# 509_CoilDriver.net
KiCad netlist of a schematic drawn in EAGLE
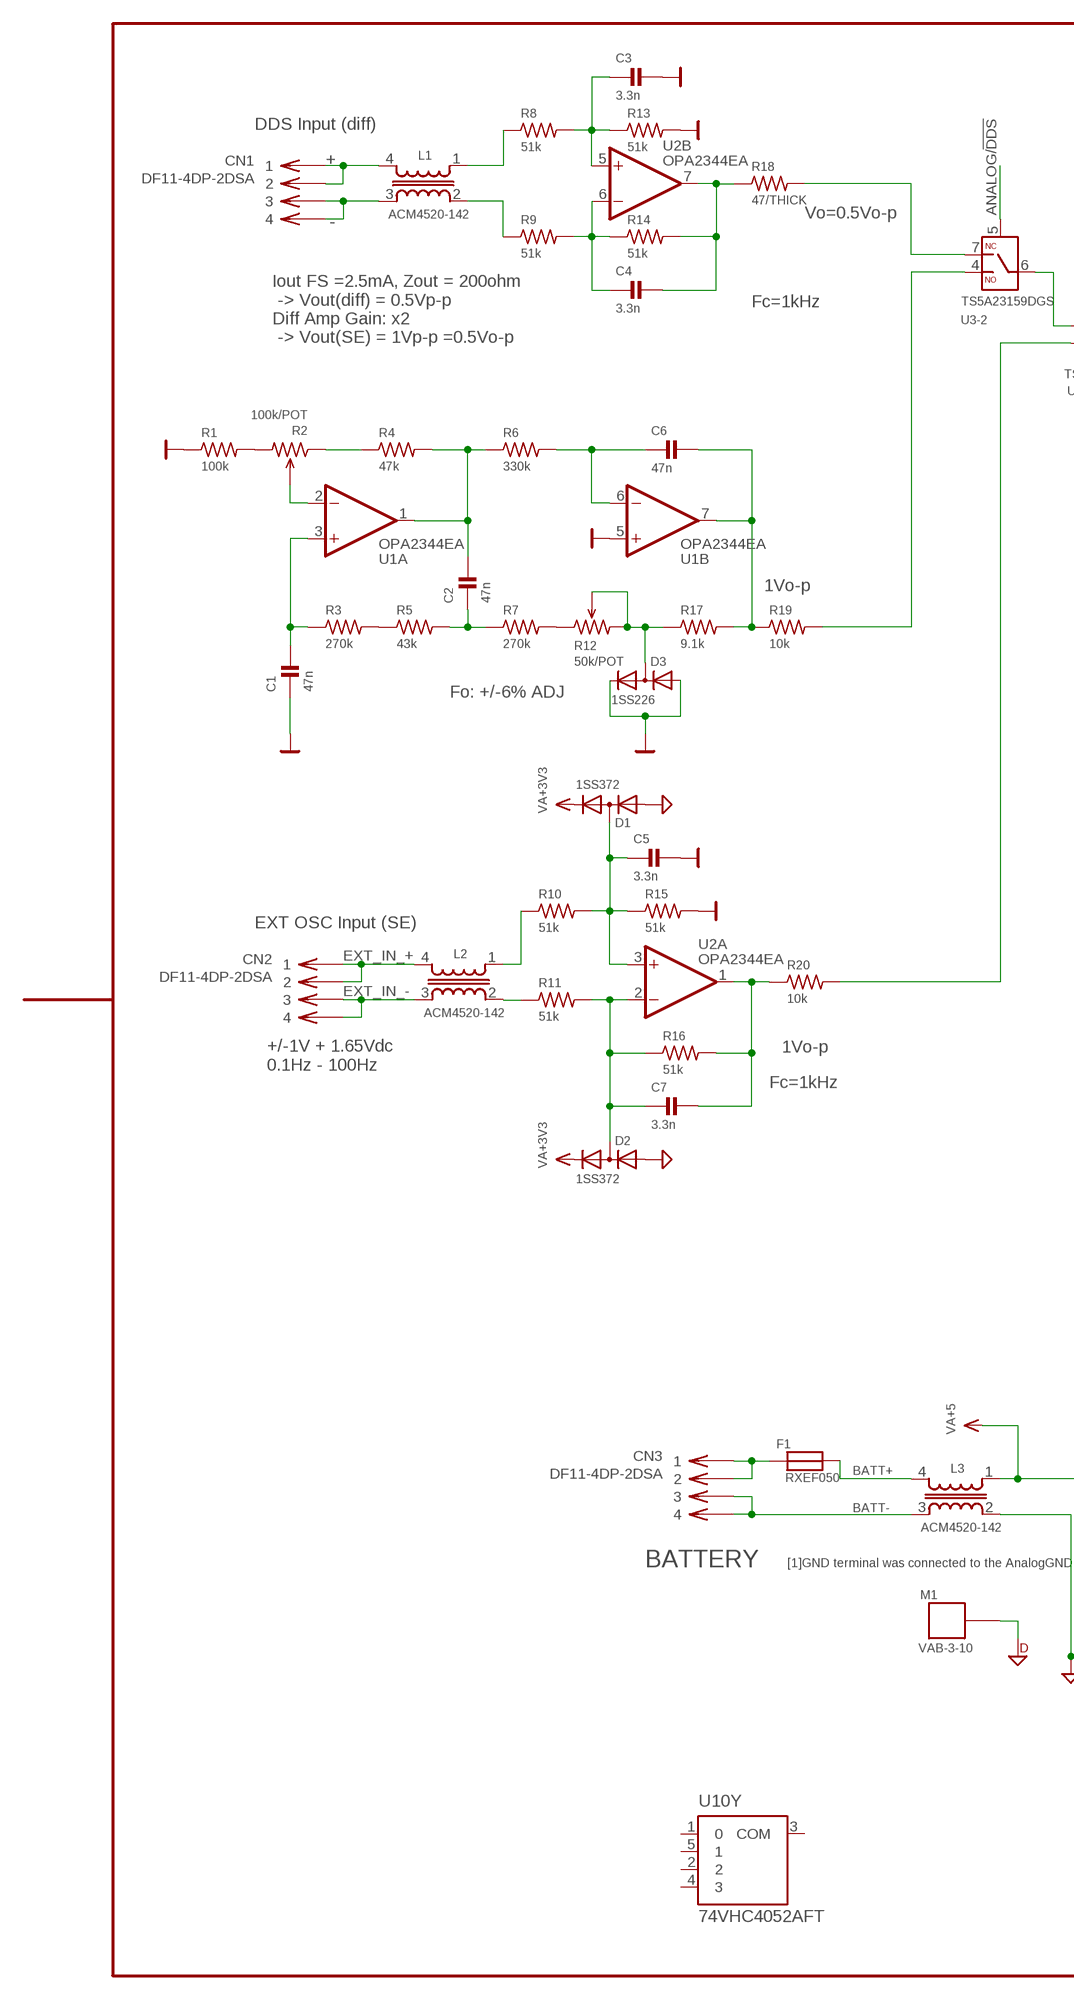
[diagram p0: schematic, sheet 1, part 1 of 2]
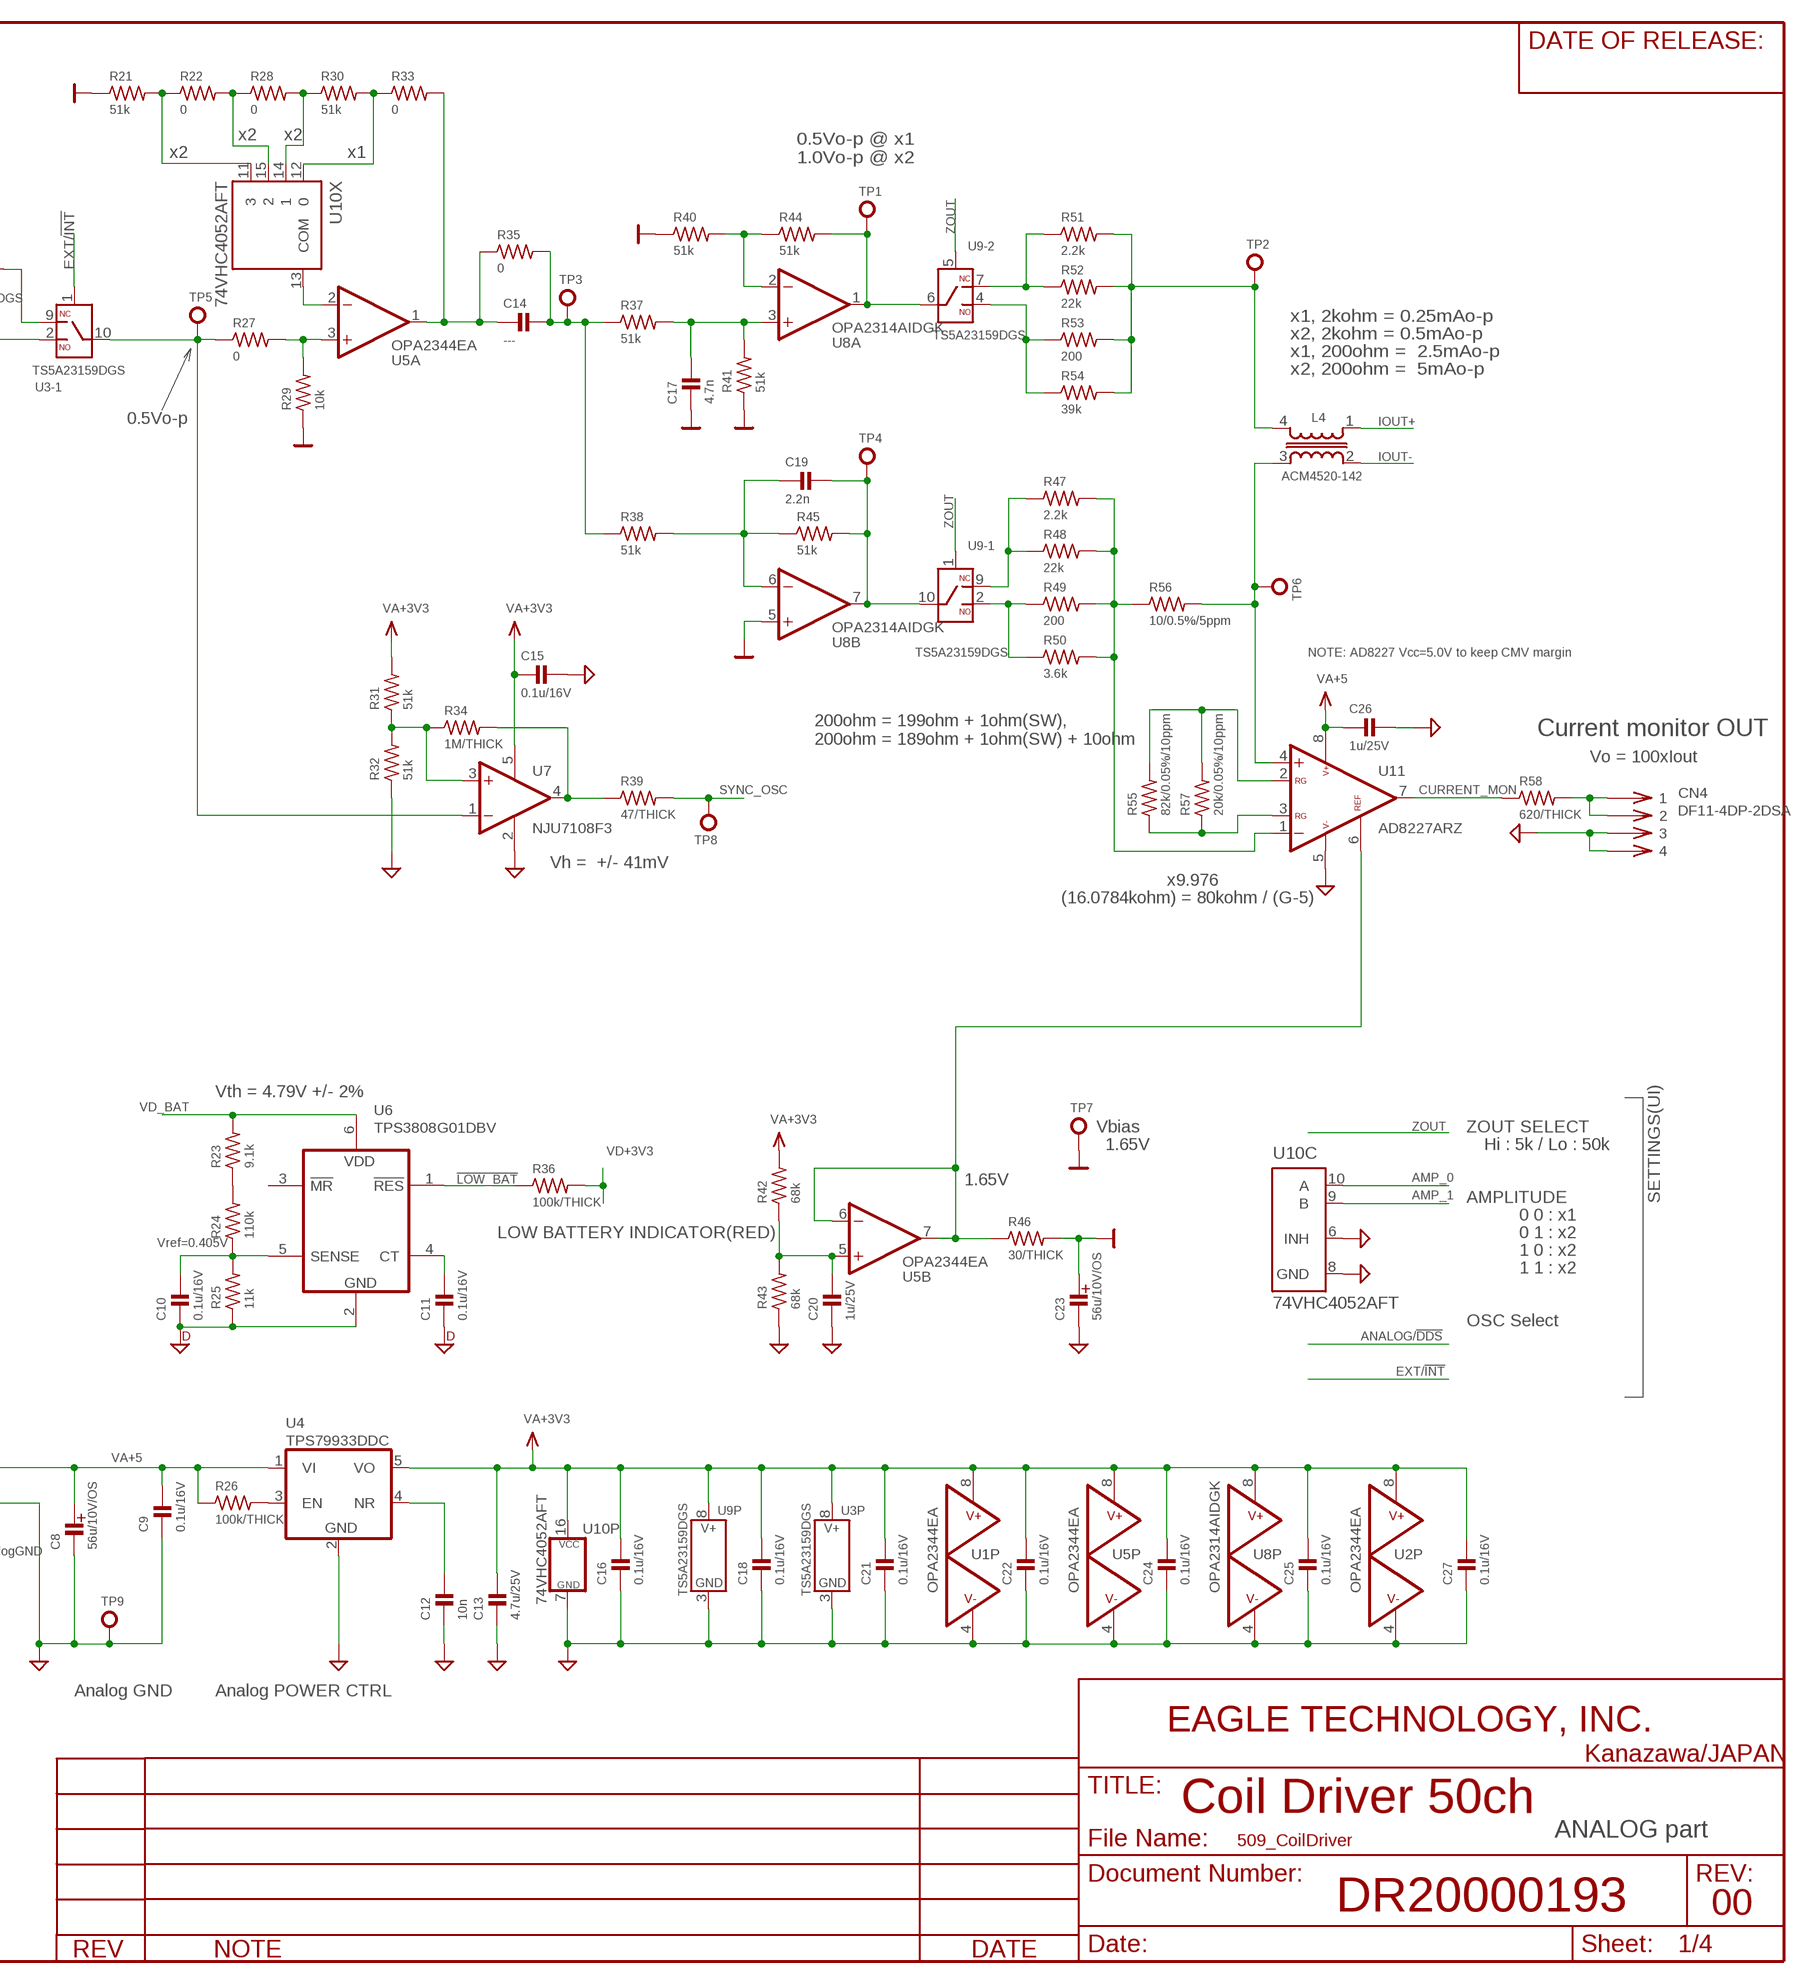
[diagram p1: schematic, sheet 1, part 2 of 2]
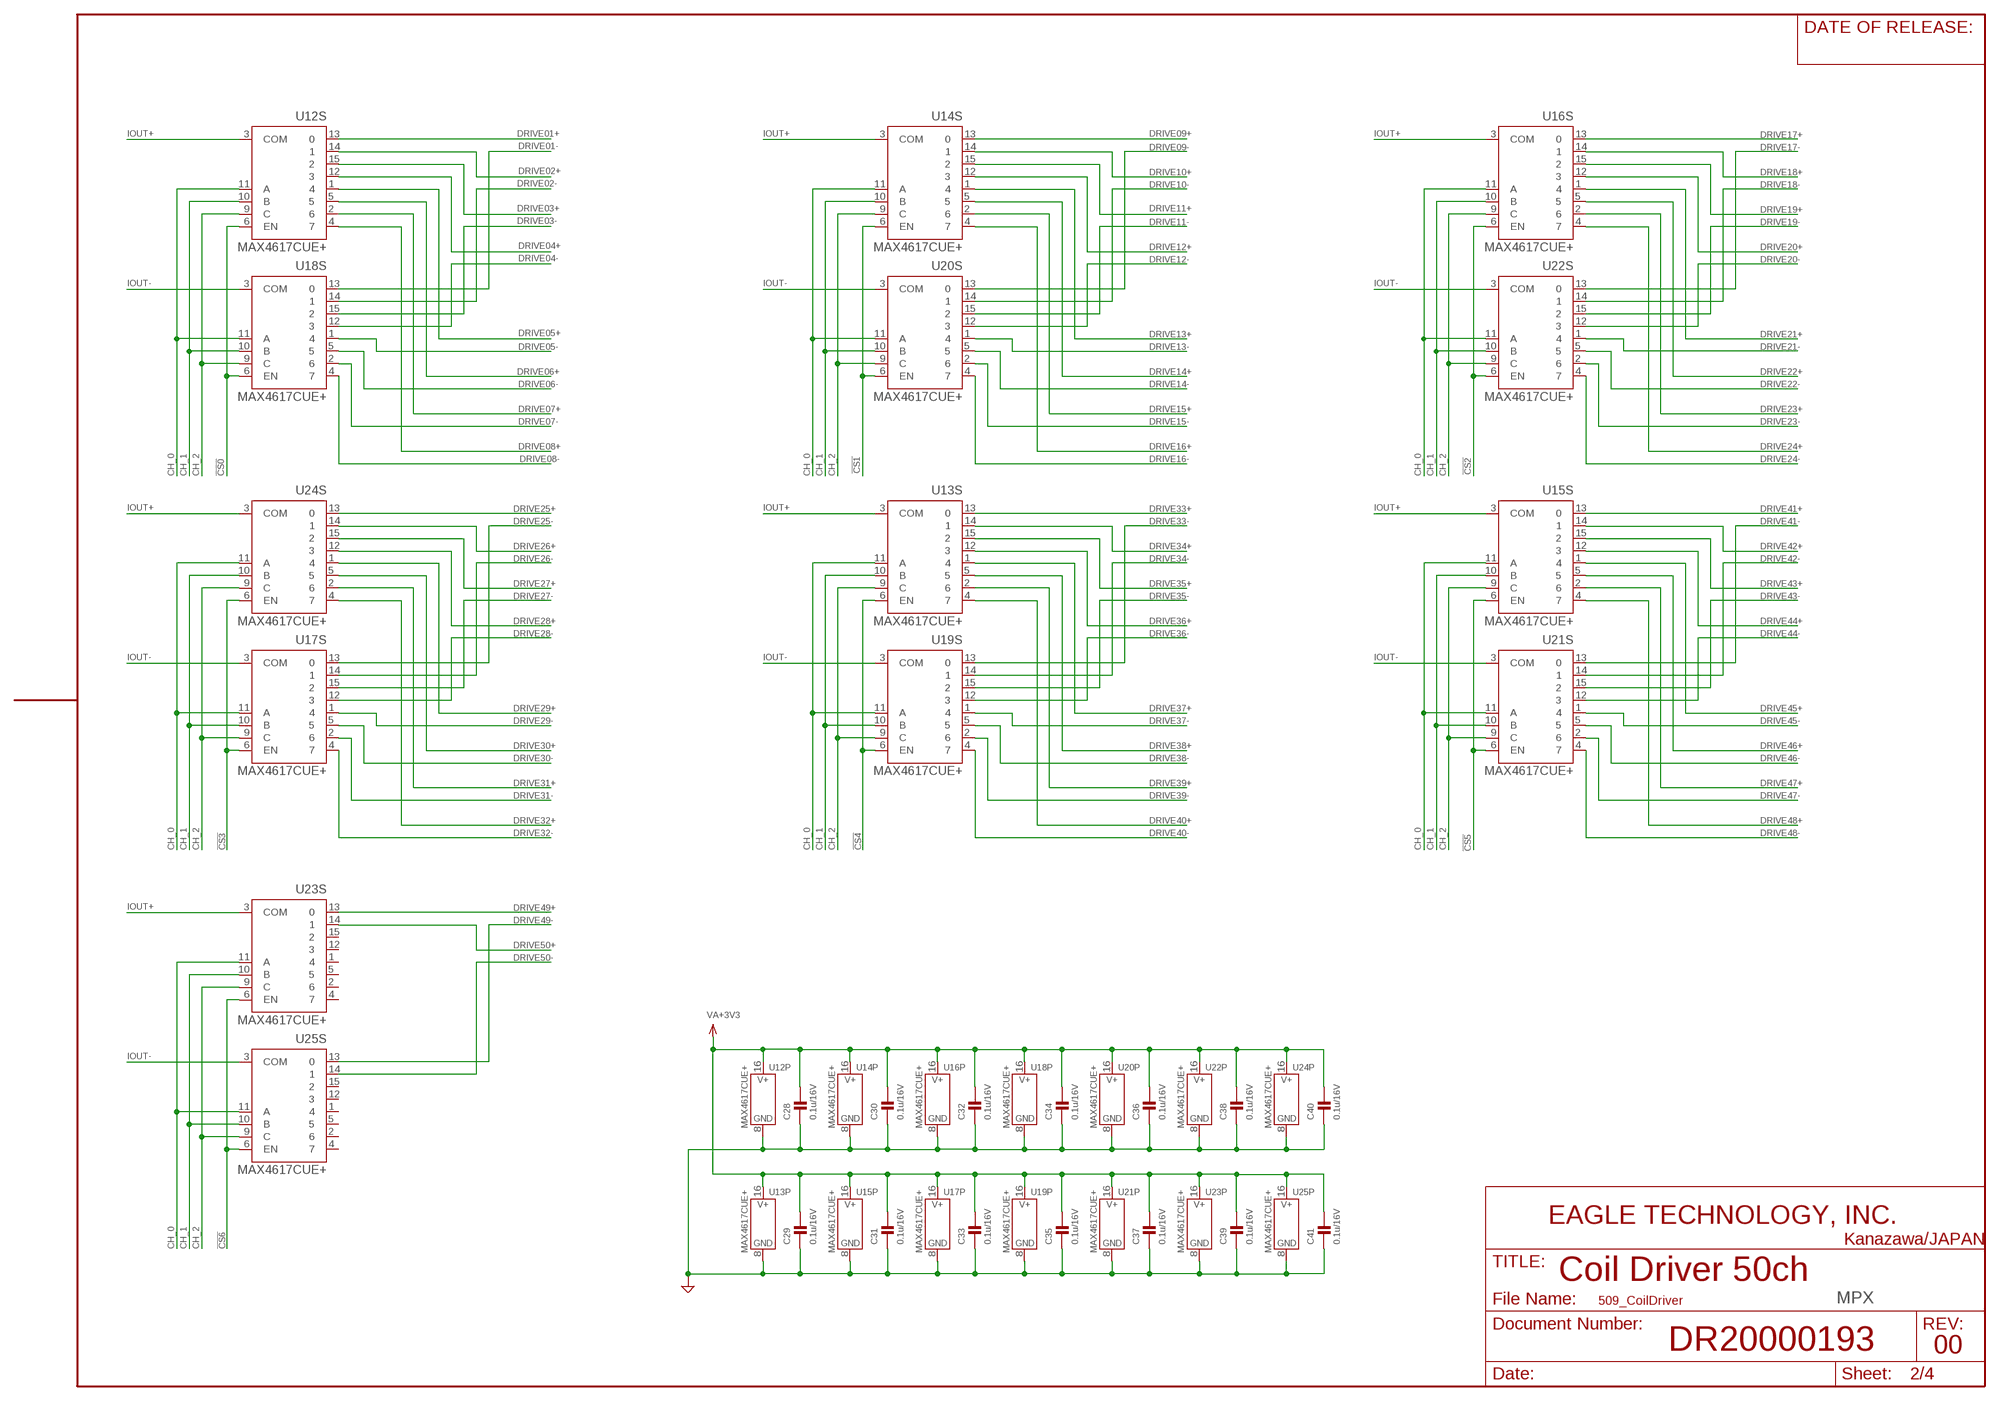
[diagram p2: schematic, sheet 2]
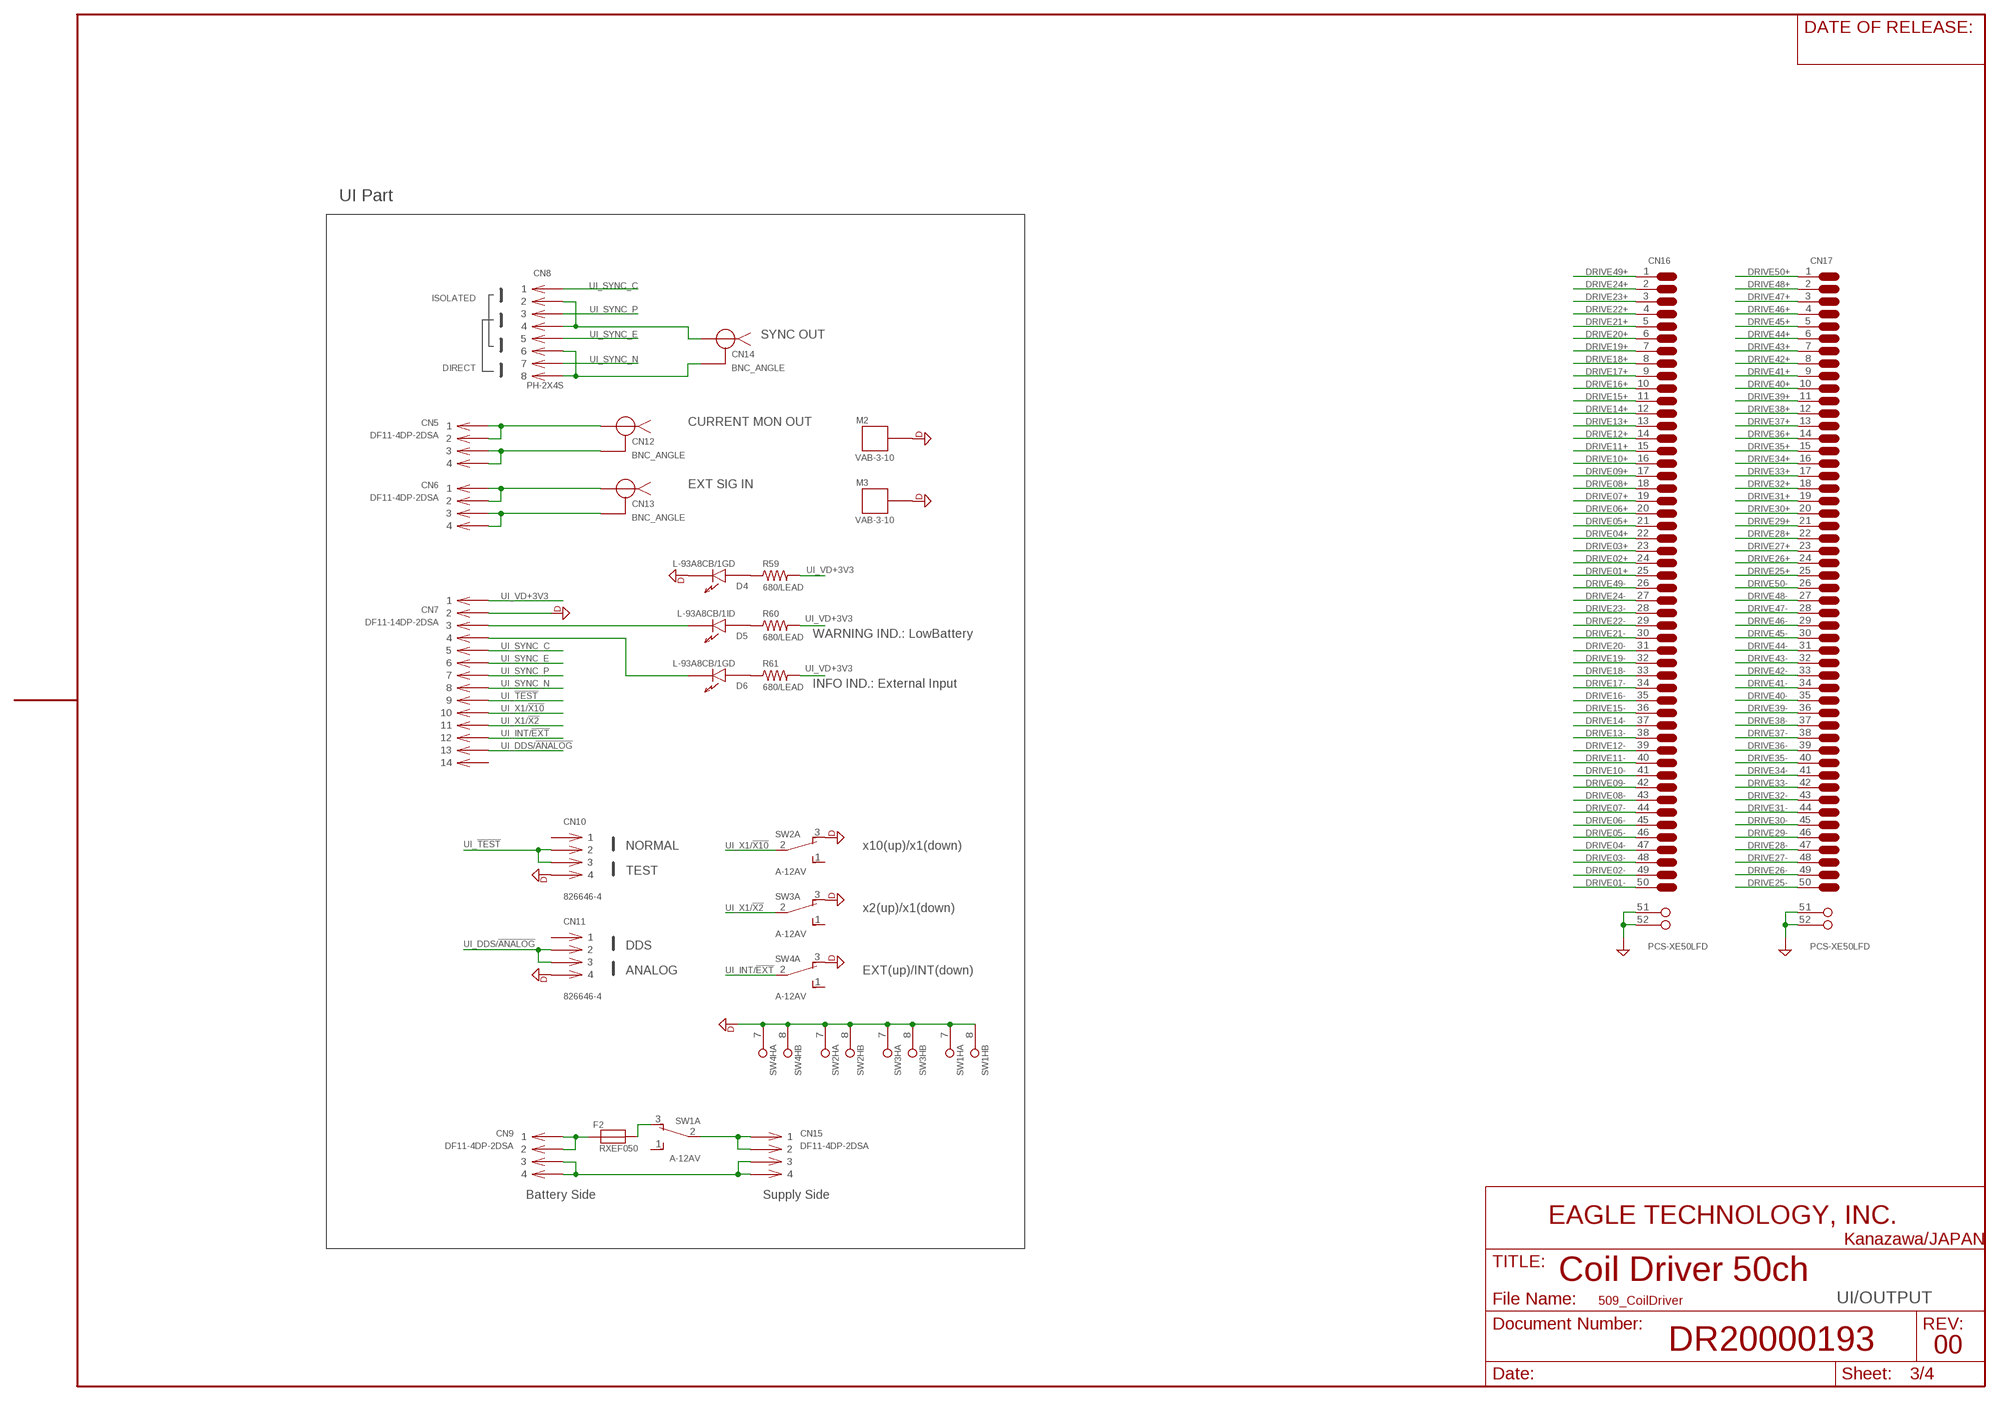
[diagram p3: schematic, sheet 3]
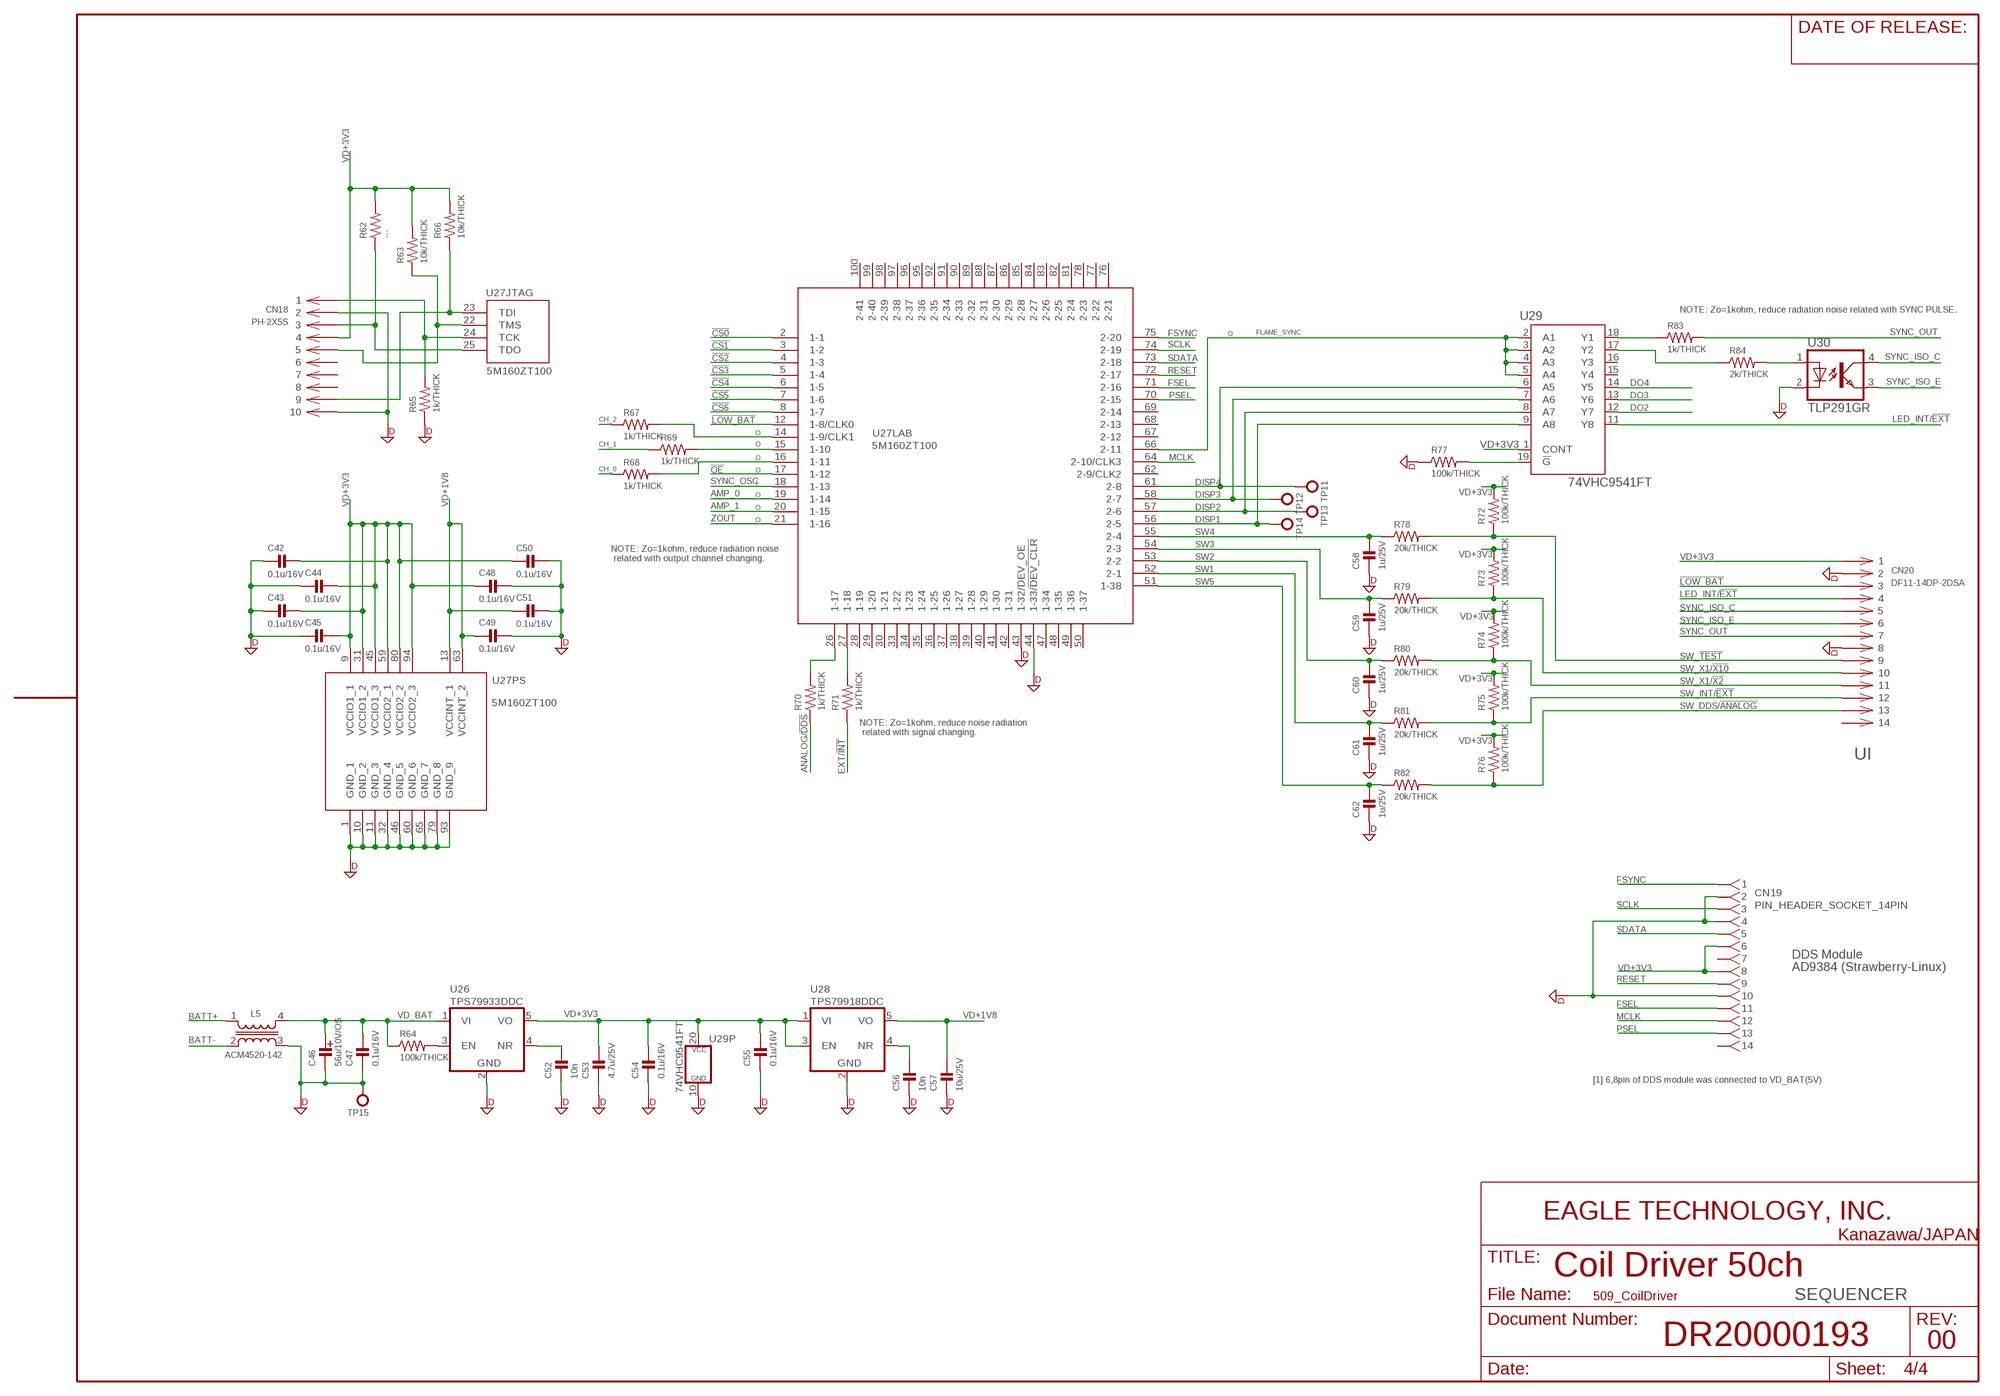
[diagram p4: schematic, sheet 4]

(export (version "E")
  (design (tool "Eeschema 10.0.6"))
  (components
    (comp (ref "C28")
      (value "0.1u/16V")
      (footprint "eagle-import:CM1005")
      (libsource (lib "eagle-import") (part "CSMD1.0X0.5MM"))
    )
    (comp (ref "C29")
      (value "0.1u/16V")
      (footprint "eagle-import:CM1005")
      (libsource (lib "eagle-import") (part "CSMD1.0X0.5MM"))
    )
    (comp (ref "C30")
      (value "0.1u/16V")
      (footprint "eagle-import:CM1005")
      (libsource (lib "eagle-import") (part "CSMD1.0X0.5MM"))
    )
    (comp (ref "C31")
      (value "0.1u/16V")
      (footprint "eagle-import:CM1005")
      (libsource (lib "eagle-import") (part "CSMD1.0X0.5MM"))
    )
    (comp (ref "C32")
      (value "0.1u/16V")
      (footprint "eagle-import:CM1005")
      (libsource (lib "eagle-import") (part "CSMD1.0X0.5MM"))
    )
    (comp (ref "C33")
      (value "0.1u/16V")
      (footprint "eagle-import:CM1005")
      (libsource (lib "eagle-import") (part "CSMD1.0X0.5MM"))
    )
    (comp (ref "C34")
      (value "0.1u/16V")
      (footprint "eagle-import:CM1005")
      (libsource (lib "eagle-import") (part "CSMD1.0X0.5MM"))
    )
    (comp (ref "C35")
      (value "0.1u/16V")
      (footprint "eagle-import:CM1005")
      (libsource (lib "eagle-import") (part "CSMD1.0X0.5MM"))
    )
    (comp (ref "C36")
      (value "0.1u/16V")
      (footprint "eagle-import:CM1005")
      (libsource (lib "eagle-import") (part "CSMD1.0X0.5MM"))
    )
    (comp (ref "C37")
      (value "0.1u/16V")
      (footprint "eagle-import:CM1005")
      (libsource (lib "eagle-import") (part "CSMD1.0X0.5MM"))
    )
    (comp (ref "C38")
      (value "0.1u/16V")
      (footprint "eagle-import:CM1005")
      (libsource (lib "eagle-import") (part "CSMD1.0X0.5MM"))
    )
    (comp (ref "C39")
      (value "0.1u/16V")
      (footprint "eagle-import:CM1005")
      (libsource (lib "eagle-import") (part "CSMD1.0X0.5MM"))
    )
    (comp (ref "C40")
      (value "0.1u/16V")
      (footprint "eagle-import:CM1005")
      (libsource (lib "eagle-import") (part "CSMD1.0X0.5MM"))
    )
    (comp (ref "C41")
      (value "0.1u/16V")
      (footprint "eagle-import:CM1005")
      (libsource (lib "eagle-import") (part "CSMD1.0X0.5MM"))
    )
    (comp (ref "U12")
      (value "MAX4617CUE+")
      (footprint "eagle-import:TSSOP16_AEL")
      (libsource (lib "eagle-import") (part "MAX4617CUE+"))
    )
    (comp (ref "U13")
      (value "MAX4617CUE+")
      (footprint "eagle-import:TSSOP16_AEL")
      (libsource (lib "eagle-import") (part "MAX4617CUE+"))
    )
    (comp (ref "U14")
      (value "MAX4617CUE+")
      (footprint "eagle-import:TSSOP16_AEL")
      (libsource (lib "eagle-import") (part "MAX4617CUE+"))
    )
    (comp (ref "U15")
      (value "MAX4617CUE+")
      (footprint "eagle-import:TSSOP16_AEL")
      (libsource (lib "eagle-import") (part "MAX4617CUE+"))
    )
    (comp (ref "U16")
      (value "MAX4617CUE+")
      (footprint "eagle-import:TSSOP16_AEL")
      (libsource (lib "eagle-import") (part "MAX4617CUE+"))
    )
    (comp (ref "U17")
      (value "MAX4617CUE+")
      (footprint "eagle-import:TSSOP16_AEL")
      (libsource (lib "eagle-import") (part "MAX4617CUE+"))
    )
    (comp (ref "U18")
      (value "MAX4617CUE+")
      (footprint "eagle-import:TSSOP16_AEL")
      (libsource (lib "eagle-import") (part "MAX4617CUE+"))
    )
    (comp (ref "U19")
      (value "MAX4617CUE+")
      (footprint "eagle-import:TSSOP16_AEL")
      (libsource (lib "eagle-import") (part "MAX4617CUE+"))
    )
    (comp (ref "U20")
      (value "MAX4617CUE+")
      (footprint "eagle-import:TSSOP16_AEL")
      (libsource (lib "eagle-import") (part "MAX4617CUE+"))
    )
    (comp (ref "U21")
      (value "MAX4617CUE+")
      (footprint "eagle-import:TSSOP16_AEL")
      (libsource (lib "eagle-import") (part "MAX4617CUE+"))
    )
    (comp (ref "U22")
      (value "MAX4617CUE+")
      (footprint "eagle-import:TSSOP16_AEL")
      (libsource (lib "eagle-import") (part "MAX4617CUE+"))
    )
    (comp (ref "U23")
      (value "MAX4617CUE+")
      (footprint "eagle-import:TSSOP16_AEL")
      (libsource (lib "eagle-import") (part "MAX4617CUE+"))
    )
    (comp (ref "U24")
      (value "MAX4617CUE+")
      (footprint "eagle-import:TSSOP16_AEL")
      (libsource (lib "eagle-import") (part "MAX4617CUE+"))
    )
    (comp (ref "U25")
      (value "MAX4617CUE+")
      (footprint "eagle-import:TSSOP16_AEL")
      (libsource (lib "eagle-import") (part "MAX4617CUE+"))
    )
    (comp (ref "C42")
      (value "0.1u/16V")
      (footprint "eagle-import:CM1005")
      (libsource (lib "eagle-import") (part "CSMD1.0X0.5MM"))
    )
    (comp (ref "C43")
      (value "0.1u/16V")
      (footprint "eagle-import:CM1005")
      (libsource (lib "eagle-import") (part "CSMD1.0X0.5MM"))
    )
    (comp (ref "C44")
      (value "0.1u/16V")
      (footprint "eagle-import:CM1005")
      (libsource (lib "eagle-import") (part "CSMD1.0X0.5MM"))
    )
    (comp (ref "C45")
      (value "0.1u/16V")
      (footprint "eagle-import:CM1005")
      (libsource (lib "eagle-import") (part "CSMD1.0X0.5MM"))
    )
    (comp (ref "C46")
      (value "56u/10V/OS")
      (footprint "eagle-import:PHI_6.3")
      (libsource (lib "eagle-import") (part "C_POL6.3-2.5MM"))
    )
    (comp (ref "C47")
      (value "0.1u/16V")
      (footprint "eagle-import:CM1005")
      (libsource (lib "eagle-import") (part "CSMD1.0X0.5MM"))
    )
    (comp (ref "C48")
      (value "0.1u/16V")
      (footprint "eagle-import:CM1005")
      (libsource (lib "eagle-import") (part "CSMD1.0X0.5MM"))
    )
    (comp (ref "C49")
      (value "0.1u/16V")
      (footprint "eagle-import:CM1005")
      (libsource (lib "eagle-import") (part "CSMD1.0X0.5MM"))
    )
    (comp (ref "C50")
      (value "0.1u/16V")
      (footprint "eagle-import:CM1005")
      (libsource (lib "eagle-import") (part "CSMD1.0X0.5MM"))
    )
    (comp (ref "C51")
      (value "0.1u/16V")
      (footprint "eagle-import:CM1005")
      (libsource (lib "eagle-import") (part "CSMD1.0X0.5MM"))
    )
    (comp (ref "C52")
      (value "10n")
      (footprint "eagle-import:CM2012")
      (libsource (lib "eagle-import") (part "CSMD2.0X1.2MM"))
    )
    (comp (ref "C53")
      (value "4.7u/25V")
      (footprint "eagle-import:CM2012")
      (libsource (lib "eagle-import") (part "CSMD2.0X1.2MM"))
    )
    (comp (ref "C54")
      (value "0.1u/16V")
      (footprint "eagle-import:CM1005")
      (libsource (lib "eagle-import") (part "CSMD1.0X0.5MM"))
    )
    (comp (ref "C55")
      (value "0.1u/16V")
      (footprint "eagle-import:CM1005")
      (libsource (lib "eagle-import") (part "CSMD1.0X0.5MM"))
    )
    (comp (ref "C56")
      (value "10n")
      (footprint "eagle-import:CM2012")
      (libsource (lib "eagle-import") (part "CSMD2.0X1.2MM"))
    )
    (comp (ref "C57")
      (value "10u/25V")
      (footprint "eagle-import:CM3216")
      (libsource (lib "eagle-import") (part "CSMD3.2X1.6MM"))
    )
    (comp (ref "C58")
      (value "1u/25V")
      (footprint "eagle-import:CM1608")
      (libsource (lib "eagle-import") (part "CSMD1.6X0.8MM"))
    )
    (comp (ref "C59")
      (value "1u/25V")
      (footprint "eagle-import:CM1608")
      (libsource (lib "eagle-import") (part "CSMD1.6X0.8MM"))
    )
    (comp (ref "C60")
      (value "1u/25V")
      (footprint "eagle-import:CM1608")
      (libsource (lib "eagle-import") (part "CSMD1.6X0.8MM"))
    )
    (comp (ref "C61")
      (value "1u/25V")
      (footprint "eagle-import:CM1608")
      (libsource (lib "eagle-import") (part "CSMD1.6X0.8MM"))
    )
    (comp (ref "C62")
      (value "1u/25V")
      (footprint "eagle-import:CM1608")
      (libsource (lib "eagle-import") (part "CSMD1.6X0.8MM"))
    )
    (comp (ref "CN18")
      (value "PH-2X5S")
      (footprint "eagle-import:PIN_HEADER_10PIN")
      (libsource (lib "eagle-import") (part "PIN_HEADER_10PIN"))
    )
    (comp (ref "CN19")
      (value "PIN_HEADER_SOCKET_14PIN")
      (footprint "eagle-import:PIN_HEADER_SOCKET_14PIN")
      (libsource (lib "eagle-import") (part "PIN_HEADER_SOCKET_14PIN"))
    )
    (comp (ref "CN20")
      (value "DF11-14DP-2DSA")
      (footprint "eagle-import:DF11-14DP-2DSA")
      (libsource (lib "eagle-import") (part "DF11-14DP-2DSA"))
    )
    (comp (ref "L5")
      (value "ACM4520-142")
      (footprint "eagle-import:ACM4520")
      (libsource (lib "eagle-import") (part "ACM4520-142"))
    )
    (comp (ref "R62")
      (value "---")
      (footprint "eagle-import:RM1608")
      (libsource (lib "eagle-import") (part "RSMD1.6X0.8MM"))
    )
    (comp (ref "R63")
      (value "10k/THICK")
      (footprint "eagle-import:RM1608")
      (libsource (lib "eagle-import") (part "RSMD1.6X0.8MM"))
    )
    (comp (ref "R64")
      (value "100k/THICK")
      (footprint "eagle-import:RM1608")
      (libsource (lib "eagle-import") (part "RSMD1.6X0.8MM"))
    )
    (comp (ref "R65")
      (value "1k/THICK")
      (footprint "eagle-import:RM1608")
      (libsource (lib "eagle-import") (part "RSMD1.6X0.8MM"))
    )
    (comp (ref "R66")
      (value "10k/THICK")
      (footprint "eagle-import:RM1608")
      (libsource (lib "eagle-import") (part "RSMD1.6X0.8MM"))
    )
    (comp (ref "R67")
      (value "1k/THICK")
      (footprint "eagle-import:RM1608")
      (libsource (lib "eagle-import") (part "RSMD1.6X0.8MM"))
    )
    (comp (ref "R68")
      (value "1k/THICK")
      (footprint "eagle-import:RM1608")
      (libsource (lib "eagle-import") (part "RSMD1.6X0.8MM"))
    )
    (comp (ref "R69")
      (value "1k/THICK")
      (footprint "eagle-import:RM1608")
      (libsource (lib "eagle-import") (part "RSMD1.6X0.8MM"))
    )
    (comp (ref "R70")
      (value "1k/THICK")
      (footprint "eagle-import:RM1608")
      (libsource (lib "eagle-import") (part "RSMD1.6X0.8MM"))
    )
    (comp (ref "R71")
      (value "1k/THICK")
      (footprint "eagle-import:RM1608")
      (libsource (lib "eagle-import") (part "RSMD1.6X0.8MM"))
    )
    (comp (ref "R72")
      (value "100k/THICK")
      (footprint "eagle-import:RM1608")
      (libsource (lib "eagle-import") (part "RSMD1.6X0.8MM"))
    )
    (comp (ref "R73")
      (value "100k/THICK")
      (footprint "eagle-import:RM1608")
      (libsource (lib "eagle-import") (part "RSMD1.6X0.8MM"))
    )
    (comp (ref "R74")
      (value "100k/THICK")
      (footprint "eagle-import:RM1608")
      (libsource (lib "eagle-import") (part "RSMD1.6X0.8MM"))
    )
    (comp (ref "R75")
      (value "100k/THICK")
      (footprint "eagle-import:RM1608")
      (libsource (lib "eagle-import") (part "RSMD1.6X0.8MM"))
    )
    (comp (ref "R76")
      (value "100k/THICK")
      (footprint "eagle-import:RM1608")
      (libsource (lib "eagle-import") (part "RSMD1.6X0.8MM"))
    )
    (comp (ref "R77")
      (value "100k/THICK")
      (footprint "eagle-import:RM1608")
      (libsource (lib "eagle-import") (part "RSMD1.6X0.8MM"))
    )
    (comp (ref "R78")
      (value "20k/THICK")
      (footprint "eagle-import:RM1608")
      (libsource (lib "eagle-import") (part "RSMD1.6X0.8MM"))
    )
    (comp (ref "R79")
      (value "20k/THICK")
      (footprint "eagle-import:RM1608")
      (libsource (lib "eagle-import") (part "RSMD1.6X0.8MM"))
    )
    (comp (ref "R80")
      (value "20k/THICK")
      (footprint "eagle-import:RM1608")
      (libsource (lib "eagle-import") (part "RSMD1.6X0.8MM"))
    )
    (comp (ref "R81")
      (value "20k/THICK")
      (footprint "eagle-import:RM1608")
      (libsource (lib "eagle-import") (part "RSMD1.6X0.8MM"))
    )
    (comp (ref "R82")
      (value "20k/THICK")
      (footprint "eagle-import:RM1608")
      (libsource (lib "eagle-import") (part "RSMD1.6X0.8MM"))
    )
    (comp (ref "R83")
      (value "1k/THICK")
      (footprint "eagle-import:RM1608")
      (libsource (lib "eagle-import") (part "RSMD1.6X0.8MM"))
    )
    (comp (ref "R84")
      (value "2k/THICK")
      (footprint "eagle-import:RM1608")
      (libsource (lib "eagle-import") (part "RSMD1.6X0.8MM"))
    )
    (comp (ref "TP11")
      (value "TP-1MMPAD")
      (footprint "eagle-import:TP_PAD_1MM")
      (libsource (lib "eagle-import") (part "TP-1MMPAD"))
    )
    (comp (ref "TP12")
      (value "TP-1MMPAD")
      (footprint "eagle-import:TP_PAD_1MM")
      (libsource (lib "eagle-import") (part "TP-1MMPAD"))
    )
    (comp (ref "TP13")
      (value "TP-1MMPAD")
      (footprint "eagle-import:TP_PAD_1MM")
      (libsource (lib "eagle-import") (part "TP-1MMPAD"))
    )
    (comp (ref "TP14")
      (value "TP-1MMPAD")
      (footprint "eagle-import:TP_PAD_1MM")
      (libsource (lib "eagle-import") (part "TP-1MMPAD"))
    )
    (comp (ref "TP15")
      (value "TP-LC3G")
      (footprint "eagle-import:TP_TH_0R9MM")
      (libsource (lib "eagle-import") (part "TP-LC3G"))
    )
    (comp (ref "U26")
      (value "TPS79933DDC")
      (footprint "eagle-import:SOT-23-5")
      (libsource (lib "eagle-import") (part "TPS799DDC33"))
    )
    (comp (ref "U27")
      (value "5M160ZT100")
      (footprint "eagle-import:QFP100_0.5")
      (libsource (lib "eagle-import") (part "5M160ZT100"))
    )
    (comp (ref "U28")
      (value "TPS79918DDC")
      (footprint "eagle-import:SOT-23-5")
      (libsource (lib "eagle-import") (part "TPS799DDC18"))
    )
    (comp (ref "U29")
      (value "74VHC9541FT")
      (footprint "eagle-import:TSSOP20-P-0044-065A")
      (libsource (lib "eagle-import") (part "749541FTVHC"))
    )
    (comp (ref "U30")
      (value "TLP291GR")
      (footprint "eagle-import:SO4(11-3C1)(TOSHIBA)")
      (libsource (lib "eagle-import") (part "TLP291GR"))
    )
    (comp (ref "CN5")
      (value "DF11-4DP-2DSA")
      (footprint "eagle-import:DF11-4DP-2DSA")
      (libsource (lib "eagle-import") (part "DF11-4DP-2DSA"))
    )
    (comp (ref "CN6")
      (value "DF11-4DP-2DSA")
      (footprint "eagle-import:DF11-4DP-2DSA")
      (libsource (lib "eagle-import") (part "DF11-4DP-2DSA"))
    )
    (comp (ref "CN7")
      (value "DF11-14DP-2DSA")
      (footprint "eagle-import:DF11-14DP-2DSA")
      (libsource (lib "eagle-import") (part "DF11-14DP-2DSA"))
    )
    (comp (ref "CN8")
      (value "PH-2X4S")
      (footprint "eagle-import:PIN_HEADER_8PIN")
      (libsource (lib "eagle-import") (part "PH-2X4S"))
    )
    (comp (ref "CN9")
      (value "DF11-4DP-2DSA")
      (footprint "eagle-import:DF11-4DP-2DSA")
      (libsource (lib "eagle-import") (part "DF11-4DP-2DSA"))
    )
    (comp (ref "CN10")
      (value "826646-4")
      (footprint "eagle-import:PIN_HEADER_4PIN")
      (libsource (lib "eagle-import") (part "PH-1X4"))
    )
    (comp (ref "CN11")
      (value "826646-4")
      (footprint "eagle-import:PIN_HEADER_4PIN")
      (libsource (lib "eagle-import") (part "PH-1X4"))
    )
    (comp (ref "CN12")
      (value "BNC_ANGLE")
      (footprint "eagle-import:BNC_F_ANGLE")
      (libsource (lib "eagle-import") (part "BNC_ANGLE"))
    )
    (comp (ref "CN13")
      (value "BNC_ANGLE")
      (footprint "eagle-import:BNC_F_ANGLE")
      (libsource (lib "eagle-import") (part "BNC_ANGLE"))
    )
    (comp (ref "CN14")
      (value "BNC_ANGLE")
      (footprint "eagle-import:BNC_F_ANGLE")
      (libsource (lib "eagle-import") (part "BNC_ANGLE"))
    )
    (comp (ref "CN15")
      (value "DF11-4DP-2DSA")
      (footprint "eagle-import:DF11-4DP-2DSA")
      (libsource (lib "eagle-import") (part "DF11-4DP-2DSA"))
    )
    (comp (ref "CN16")
      (value "PCS-XE50LFD")
      (footprint "eagle-import:50LFD2")
      (libsource (lib "eagle-import") (part "PCS-XE50LFD"))
    )
    (comp (ref "CN17")
      (value "PCS-XE50LFD")
      (footprint "eagle-import:50LFD2")
      (libsource (lib "eagle-import") (part "PCS-XE50LFD"))
    )
    (comp (ref "D4")
      (value "L-93A8CB/1GD")
      (footprint "eagle-import:L-93A8CB")
      (libsource (lib "eagle-import") (part "L-93A8CB/1GD"))
    )
    (comp (ref "D5")
      (value "L-93A8CB/1ID")
      (footprint "eagle-import:L-93A8CB")
      (libsource (lib "eagle-import") (part "L-93A8CB/1ID"))
    )
    (comp (ref "D6")
      (value "L-93A8CB/1GD")
      (footprint "eagle-import:L-93A8CB")
      (libsource (lib "eagle-import") (part "L-93A8CB/1GD"))
    )
    (comp (ref "F2")
      (value "RXEF050")
      (footprint "eagle-import:8X3_5.08")
      (libsource (lib "eagle-import") (part "RXEF050"))
    )
    (comp (ref "M2")
      (value "VAB-3-10")
      (footprint "eagle-import:VAB_3_10_CONTACT")
      (libsource (lib "eagle-import") (part "VAB-3-10"))
    )
    (comp (ref "M3")
      (value "VAB-3-10")
      (footprint "eagle-import:VAB_3_10_CONTACT")
      (libsource (lib "eagle-import") (part "VAB-3-10"))
    )
    (comp (ref "R59")
      (value "680/LEAD")
      (footprint "eagle-import:0207_2V")
      (libsource (lib "eagle-import") (part "R0207/2V"))
    )
    (comp (ref "R60")
      (value "680/LEAD")
      (footprint "eagle-import:0207_2V")
      (libsource (lib "eagle-import") (part "R0207/2V"))
    )
    (comp (ref "R61")
      (value "680/LEAD")
      (footprint "eagle-import:0207_2V")
      (libsource (lib "eagle-import") (part "R0207/2V"))
    )
    (comp (ref "SW1")
      (value "A-12AV")
      (footprint "eagle-import:A-12_")
      (libsource (lib "eagle-import") (part "A-1V2A"))
    )
    (comp (ref "SW2")
      (value "A-12AV")
      (footprint "eagle-import:A-12_")
      (libsource (lib "eagle-import") (part "A-1V2A"))
    )
    (comp (ref "SW3")
      (value "A-12AV")
      (footprint "eagle-import:A-12_")
      (libsource (lib "eagle-import") (part "A-1V2A"))
    )
    (comp (ref "SW4")
      (value "A-12AV")
      (footprint "eagle-import:A-12_")
      (libsource (lib "eagle-import") (part "A-1V2A"))
    )
    (comp (ref "C1")
      (value "47n")
      (footprint "eagle-import:CM3216")
      (libsource (lib "eagle-import") (part "CSMD3.2X1.6MM"))
    )
    (comp (ref "C2")
      (value "47n")
      (footprint "eagle-import:CM3216")
      (libsource (lib "eagle-import") (part "CSMD3.2X1.6MM"))
    )
    (comp (ref "C3")
      (value "3.3n")
      (footprint "eagle-import:CM2012")
      (libsource (lib "eagle-import") (part "CSMD2.0X1.2MM"))
    )
    (comp (ref "C4")
      (value "3.3n")
      (footprint "eagle-import:CM2012")
      (libsource (lib "eagle-import") (part "CSMD2.0X1.2MM"))
    )
    (comp (ref "C5")
      (value "3.3n")
      (footprint "eagle-import:CM2012")
      (libsource (lib "eagle-import") (part "CSMD2.0X1.2MM"))
    )
    (comp (ref "C6")
      (value "47n")
      (footprint "eagle-import:CM3216")
      (libsource (lib "eagle-import") (part "CSMD3.2X1.6MM"))
    )
    (comp (ref "C7")
      (value "3.3n")
      (footprint "eagle-import:CM2012")
      (libsource (lib "eagle-import") (part "CSMD2.0X1.2MM"))
    )
    (comp (ref "C8")
      (value "56u/10V/OS")
      (footprint "eagle-import:PHI_6.3")
      (libsource (lib "eagle-import") (part "C_POL6.3-2.5MM"))
    )
    (comp (ref "C9")
      (value "0.1u/16V")
      (footprint "eagle-import:CM1005")
      (libsource (lib "eagle-import") (part "CSMD1.0X0.5MM"))
    )
    (comp (ref "C10")
      (value "0.1u/16V")
      (footprint "eagle-import:CM1005")
      (libsource (lib "eagle-import") (part "CSMD1.0X0.5MM"))
    )
    (comp (ref "C11")
      (value "0.1u/16V")
      (footprint "eagle-import:CM1005")
      (libsource (lib "eagle-import") (part "CSMD1.0X0.5MM"))
    )
    (comp (ref "C12")
      (value "10n")
      (footprint "eagle-import:CM2012")
      (libsource (lib "eagle-import") (part "CSMD2.0X1.2MM"))
    )
    (comp (ref "C13")
      (value "4.7u/25V")
      (footprint "eagle-import:CM2012")
      (libsource (lib "eagle-import") (part "CSMD2.0X1.2MM"))
    )
    (comp (ref "C14")
      (value "---")
      (footprint "eagle-import:CM3216")
      (libsource (lib "eagle-import") (part "CSMD3.2X1.6MM"))
    )
    (comp (ref "C15")
      (value "0.1u/16V")
      (footprint "eagle-import:CM1005")
      (libsource (lib "eagle-import") (part "CSMD1.0X0.5MM"))
    )
    (comp (ref "C16")
      (value "0.1u/16V")
      (footprint "eagle-import:CM1005")
      (libsource (lib "eagle-import") (part "CSMD1.0X0.5MM"))
    )
    (comp (ref "C17")
      (value "4.7n")
      (footprint "eagle-import:CM2012")
      (libsource (lib "eagle-import") (part "CSMD2.0X1.2MM"))
    )
    (comp (ref "C18")
      (value "0.1u/16V")
      (footprint "eagle-import:CM1005")
      (libsource (lib "eagle-import") (part "CSMD1.0X0.5MM"))
    )
    (comp (ref "C19")
      (value "2.2n")
      (footprint "eagle-import:CM2012")
      (libsource (lib "eagle-import") (part "CSMD2.0X1.2MM"))
    )
    (comp (ref "C20")
      (value "1u/25V")
      (footprint "eagle-import:CM1608")
      (libsource (lib "eagle-import") (part "CSMD1.6X0.8MM"))
    )
    (comp (ref "C21")
      (value "0.1u/16V")
      (footprint "eagle-import:CM1005")
      (libsource (lib "eagle-import") (part "CSMD1.0X0.5MM"))
    )
    (comp (ref "C22")
      (value "0.1u/16V")
      (footprint "eagle-import:CM1005")
      (libsource (lib "eagle-import") (part "CSMD1.0X0.5MM"))
    )
    (comp (ref "C23")
      (value "56u/10V/OS")
      (footprint "eagle-import:PHI_6.3")
      (libsource (lib "eagle-import") (part "C_POL6.3-2.5MM"))
    )
    (comp (ref "C24")
      (value "0.1u/16V")
      (footprint "eagle-import:CM1005")
      (libsource (lib "eagle-import") (part "CSMD1.0X0.5MM"))
    )
    (comp (ref "C25")
      (value "0.1u/16V")
      (footprint "eagle-import:CM1005")
      (libsource (lib "eagle-import") (part "CSMD1.0X0.5MM"))
    )
    (comp (ref "C26")
      (value "1u/25V")
      (footprint "eagle-import:CM1608")
      (libsource (lib "eagle-import") (part "CSMD1.6X0.8MM"))
    )
    (comp (ref "C27")
      (value "0.1u/16V")
      (footprint "eagle-import:CM1005")
      (libsource (lib "eagle-import") (part "CSMD1.0X0.5MM"))
    )
    (comp (ref "CN1")
      (value "DF11-4DP-2DSA")
      (footprint "eagle-import:DF11-4DP-2DSA")
      (libsource (lib "eagle-import") (part "DF11-4DP-2DSA"))
    )
    (comp (ref "CN2")
      (value "DF11-4DP-2DSA")
      (footprint "eagle-import:DF11-4DP-2DSA")
      (libsource (lib "eagle-import") (part "DF11-4DP-2DSA"))
    )
    (comp (ref "CN3")
      (value "DF11-4DP-2DSA")
      (footprint "eagle-import:DF11-4DP-2DSA")
      (libsource (lib "eagle-import") (part "DF11-4DP-2DSA"))
    )
    (comp (ref "CN4")
      (value "DF11-4DP-2DSA")
      (footprint "eagle-import:DF11-4DP-2DSA")
      (libsource (lib "eagle-import") (part "DF11-4DP-2DSA"))
    )
    (comp (ref "D1")
      (value "1SS372")
      (footprint "eagle-import:SC70-3-R")
      (libsource (lib "eagle-import") (part "1SS372"))
    )
    (comp (ref "D2")
      (value "1SS372")
      (footprint "eagle-import:SC70-3-R")
      (libsource (lib "eagle-import") (part "1SS372"))
    )
    (comp (ref "D3")
      (value "1SS226")
      (footprint "eagle-import:SOT23")
      (libsource (lib "eagle-import") (part "1SS226"))
    )
    (comp (ref "F1")
      (value "RXEF050")
      (footprint "eagle-import:8X3_5.08")
      (libsource (lib "eagle-import") (part "RXEF050"))
    )
    (comp (ref "L1")
      (value "ACM4520-142")
      (footprint "eagle-import:ACM4520")
      (libsource (lib "eagle-import") (part "ACM4520-142"))
    )
    (comp (ref "L2")
      (value "ACM4520-142")
      (footprint "eagle-import:ACM4520")
      (libsource (lib "eagle-import") (part "ACM4520-142"))
    )
    (comp (ref "L3")
      (value "ACM4520-142")
      (footprint "eagle-import:ACM4520")
      (libsource (lib "eagle-import") (part "ACM4520-142"))
    )
    (comp (ref "L4")
      (value "ACM4520-142")
      (footprint "eagle-import:ACM4520")
      (libsource (lib "eagle-import") (part "ACM4520-142"))
    )
    (comp (ref "M1")
      (value "VAB-3-10")
      (footprint "eagle-import:VAB_3_10_CONTACT")
      (libsource (lib "eagle-import") (part "VAB-3-10"))
    )
    (comp (ref "R1")
      (value "100k")
      (footprint "eagle-import:RM1608")
      (libsource (lib "eagle-import") (part "RSMD1.6X0.8MM"))
    )
    (comp (ref "R2")
      (value "100k/POT")
      (footprint "eagle-import:CT-6")
      (libsource (lib "eagle-import") (part "R_POT"))
    )
    (comp (ref "R3")
      (value "270k")
      (footprint "eagle-import:RM1608")
      (libsource (lib "eagle-import") (part "RSMD1.6X0.8MM"))
    )
    (comp (ref "R4")
      (value "47k")
      (footprint "eagle-import:RM1608")
      (libsource (lib "eagle-import") (part "RSMD1.6X0.8MM"))
    )
    (comp (ref "R5")
      (value "43k")
      (footprint "eagle-import:RM1608")
      (libsource (lib "eagle-import") (part "RSMD1.6X0.8MM"))
    )
    (comp (ref "R6")
      (value "330k")
      (footprint "eagle-import:RM1608")
      (libsource (lib "eagle-import") (part "RSMD1.6X0.8MM"))
    )
    (comp (ref "R7")
      (value "270k")
      (footprint "eagle-import:RM1608")
      (libsource (lib "eagle-import") (part "RSMD1.6X0.8MM"))
    )
    (comp (ref "R8")
      (value "51k")
      (footprint "eagle-import:RM1608")
      (libsource (lib "eagle-import") (part "RSMD1.6X0.8MM"))
    )
    (comp (ref "R9")
      (value "51k")
      (footprint "eagle-import:RM1608")
      (libsource (lib "eagle-import") (part "RSMD1.6X0.8MM"))
    )
    (comp (ref "R10")
      (value "51k")
      (footprint "eagle-import:RM1608")
      (libsource (lib "eagle-import") (part "RSMD1.6X0.8MM"))
    )
    (comp (ref "R11")
      (value "51k")
      (footprint "eagle-import:RM1608")
      (libsource (lib "eagle-import") (part "RSMD1.6X0.8MM"))
    )
    (comp (ref "R12")
      (value "50k/POT")
      (footprint "eagle-import:CT-6")
      (libsource (lib "eagle-import") (part "R_POT"))
    )
    (comp (ref "R13")
      (value "51k")
      (footprint "eagle-import:RM1608")
      (libsource (lib "eagle-import") (part "RSMD1.6X0.8MM"))
    )
    (comp (ref "R14")
      (value "51k")
      (footprint "eagle-import:RM1608")
      (libsource (lib "eagle-import") (part "RSMD1.6X0.8MM"))
    )
    (comp (ref "R15")
      (value "51k")
      (footprint "eagle-import:RM1608")
      (libsource (lib "eagle-import") (part "RSMD1.6X0.8MM"))
    )
    (comp (ref "R16")
      (value "51k")
      (footprint "eagle-import:RM1608")
      (libsource (lib "eagle-import") (part "RSMD1.6X0.8MM"))
    )
    (comp (ref "R17")
      (value "9.1k")
      (footprint "eagle-import:RM1608")
      (libsource (lib "eagle-import") (part "RSMD1.6X0.8MM"))
    )
    (comp (ref "R18")
      (value "47/THICK")
      (footprint "eagle-import:RM1608")
      (libsource (lib "eagle-import") (part "RSMD1.6X0.8MM"))
    )
    (comp (ref "R19")
      (value "10k")
      (footprint "eagle-import:RM1608")
      (libsource (lib "eagle-import") (part "RSMD1.6X0.8MM"))
    )
    (comp (ref "R20")
      (value "10k")
      (footprint "eagle-import:RM1608")
      (libsource (lib "eagle-import") (part "RSMD1.6X0.8MM"))
    )
    (comp (ref "R21")
      (value "51k")
      (footprint "eagle-import:RM1608")
      (libsource (lib "eagle-import") (part "RSMD1.6X0.8MM"))
    )
    (comp (ref "R22")
      (value "0")
      (footprint "eagle-import:RM1608")
      (libsource (lib "eagle-import") (part "RSMD1.6X0.8MM"))
    )
    (comp (ref "R23")
      (value "9.1k")
      (footprint "eagle-import:RM1608")
      (libsource (lib "eagle-import") (part "RSMD1.6X0.8MM"))
    )
    (comp (ref "R24")
      (value "110k")
      (footprint "eagle-import:RM1608")
      (libsource (lib "eagle-import") (part "RSMD1.6X0.8MM"))
    )
    (comp (ref "R25")
      (value "11k")
      (footprint "eagle-import:RM1608")
      (libsource (lib "eagle-import") (part "RSMD1.6X0.8MM"))
    )
    (comp (ref "R26")
      (value "100k/THICK")
      (footprint "eagle-import:RM1608")
      (libsource (lib "eagle-import") (part "RSMD1.6X0.8MM"))
    )
    (comp (ref "R27")
      (value "0")
      (footprint "eagle-import:RM1608")
      (libsource (lib "eagle-import") (part "RSMD1.6X0.8MM"))
    )
    (comp (ref "R28")
      (value "0")
      (footprint "eagle-import:RM1608")
      (libsource (lib "eagle-import") (part "RSMD1.6X0.8MM"))
    )
    (comp (ref "R29")
      (value "10k")
      (footprint "eagle-import:RM1608")
      (libsource (lib "eagle-import") (part "RSMD1.6X0.8MM"))
    )
    (comp (ref "R30")
      (value "51k")
      (footprint "eagle-import:RM1608")
      (libsource (lib "eagle-import") (part "RSMD1.6X0.8MM"))
    )
    (comp (ref "R31")
      (value "51k")
      (footprint "eagle-import:RM1608")
      (libsource (lib "eagle-import") (part "RSMD1.6X0.8MM"))
    )
    (comp (ref "R32")
      (value "51k")
      (footprint "eagle-import:RM1608")
      (libsource (lib "eagle-import") (part "RSMD1.6X0.8MM"))
    )
    (comp (ref "R33")
      (value "0")
      (footprint "eagle-import:RM1608")
      (libsource (lib "eagle-import") (part "RSMD1.6X0.8MM"))
    )
    (comp (ref "R34")
      (value "1M/THICK")
      (footprint "eagle-import:RM1608")
      (libsource (lib "eagle-import") (part "RSMD1.6X0.8MM"))
    )
    (comp (ref "R35")
      (value "0")
      (footprint "eagle-import:RM1608")
      (libsource (lib "eagle-import") (part "RSMD1.6X0.8MM"))
    )
    (comp (ref "R36")
      (value "100k/THICK")
      (footprint "eagle-import:RM1608")
      (libsource (lib "eagle-import") (part "RSMD1.6X0.8MM"))
    )
    (comp (ref "R37")
      (value "51k")
      (footprint "eagle-import:RM1608")
      (libsource (lib "eagle-import") (part "RSMD1.6X0.8MM"))
    )
    (comp (ref "R38")
      (value "51k")
      (footprint "eagle-import:RM1608")
      (libsource (lib "eagle-import") (part "RSMD1.6X0.8MM"))
    )
    (comp (ref "R39")
      (value "47/THICK")
      (footprint "eagle-import:RM1608")
      (libsource (lib "eagle-import") (part "RSMD1.6X0.8MM"))
    )
    (comp (ref "R40")
      (value "51k")
      (footprint "eagle-import:RM1608")
      (libsource (lib "eagle-import") (part "RSMD1.6X0.8MM"))
    )
    (comp (ref "R41")
      (value "51k")
      (footprint "eagle-import:RM1608")
      (libsource (lib "eagle-import") (part "RSMD1.6X0.8MM"))
    )
    (comp (ref "R42")
      (value "68k")
      (footprint "eagle-import:RM1608")
      (libsource (lib "eagle-import") (part "RSMD1.6X0.8MM"))
    )
    (comp (ref "R43")
      (value "68k")
      (footprint "eagle-import:RM1608")
      (libsource (lib "eagle-import") (part "RSMD1.6X0.8MM"))
    )
    (comp (ref "R44")
      (value "51k")
      (footprint "eagle-import:RM1608")
      (libsource (lib "eagle-import") (part "RSMD1.6X0.8MM"))
    )
    (comp (ref "R45")
      (value "51k")
      (footprint "eagle-import:RM1608")
      (libsource (lib "eagle-import") (part "RSMD1.6X0.8MM"))
    )
    (comp (ref "R46")
      (value "30/THICK")
      (footprint "eagle-import:RM1608")
      (libsource (lib "eagle-import") (part "RSMD1.6X0.8MM"))
    )
    (comp (ref "R47")
      (value "2.2k")
      (footprint "eagle-import:RM1608")
      (libsource (lib "eagle-import") (part "RSMD1.6X0.8MM"))
    )
    (comp (ref "R48")
      (value "22k")
      (footprint "eagle-import:RM1608")
      (libsource (lib "eagle-import") (part "RSMD1.6X0.8MM"))
    )
    (comp (ref "R49")
      (value "200")
      (footprint "eagle-import:RM1608")
      (libsource (lib "eagle-import") (part "RSMD1.6X0.8MM"))
    )
    (comp (ref "R50")
      (value "3.6k")
      (footprint "eagle-import:RM1608")
      (libsource (lib "eagle-import") (part "RSMD1.6X0.8MM"))
    )
    (comp (ref "R51")
      (value "2.2k")
      (footprint "eagle-import:RM1608")
      (libsource (lib "eagle-import") (part "RSMD1.6X0.8MM"))
    )
    (comp (ref "R52")
      (value "22k")
      (footprint "eagle-import:RM1608")
      (libsource (lib "eagle-import") (part "RSMD1.6X0.8MM"))
    )
    (comp (ref "R53")
      (value "200")
      (footprint "eagle-import:RM1608")
      (libsource (lib "eagle-import") (part "RSMD1.6X0.8MM"))
    )
    (comp (ref "R54")
      (value "39k")
      (footprint "eagle-import:RM1608")
      (libsource (lib "eagle-import") (part "RSMD1.6X0.8MM"))
    )
    (comp (ref "R55")
      (value "82k/0.05%/10ppm")
      (footprint "eagle-import:RM1608")
      (libsource (lib "eagle-import") (part "RSMD1.6X0.8MM"))
    )
    (comp (ref "R56")
      (value "10/0.5%/5ppm")
      (footprint "eagle-import:RM1608")
      (libsource (lib "eagle-import") (part "RSMD1.6X0.8MM"))
    )
    (comp (ref "R57")
      (value "20k/0.05%/10ppm")
      (footprint "eagle-import:RM1608")
      (libsource (lib "eagle-import") (part "RSMD1.6X0.8MM"))
    )
    (comp (ref "R58")
      (value "620/THICK")
      (footprint "eagle-import:RM1608")
      (libsource (lib "eagle-import") (part "RSMD1.6X0.8MM"))
    )
    (comp (ref "TP1")
      (value "TP-LC3G")
      (footprint "eagle-import:TP_TH_0R9MM")
      (libsource (lib "eagle-import") (part "TP-LC3G"))
    )
    (comp (ref "TP2")
      (value "TP-LC3G")
      (footprint "eagle-import:TP_TH_0R9MM")
      (libsource (lib "eagle-import") (part "TP-LC3G"))
    )
    (comp (ref "TP3")
      (value "TP-LC3G")
      (footprint "eagle-import:TP_TH_0R9MM")
      (libsource (lib "eagle-import") (part "TP-LC3G"))
    )
    (comp (ref "TP4")
      (value "TP-LC3G")
      (footprint "eagle-import:TP_TH_0R9MM")
      (libsource (lib "eagle-import") (part "TP-LC3G"))
    )
    (comp (ref "TP5")
      (value "TP-LC3G")
      (footprint "eagle-import:TP_TH_0R9MM")
      (libsource (lib "eagle-import") (part "TP-LC3G"))
    )
    (comp (ref "TP6")
      (value "TP-LC3G")
      (footprint "eagle-import:TP_TH_0R9MM")
      (libsource (lib "eagle-import") (part "TP-LC3G"))
    )
    (comp (ref "TP7")
      (value "TP-LC3G")
      (footprint "eagle-import:TP_TH_0R9MM")
      (libsource (lib "eagle-import") (part "TP-LC3G"))
    )
    (comp (ref "TP8")
      (value "TP-LC3G")
      (footprint "eagle-import:TP_TH_0R9MM")
      (libsource (lib "eagle-import") (part "TP-LC3G"))
    )
    (comp (ref "TP9")
      (value "TP-LC3G")
      (footprint "eagle-import:TP_TH_0R9MM")
      (libsource (lib "eagle-import") (part "TP-LC3G"))
    )
    (comp (ref "U1")
      (value "OPA2344EA")
      (footprint "eagle-import:MSO8_AEL")
      (libsource (lib "eagle-import") (part "OPA2344EA"))
    )
    (comp (ref "U2")
      (value "OPA2344EA")
      (footprint "eagle-import:MSO8_AEL")
      (libsource (lib "eagle-import") (part "OPA2344EA"))
    )
    (comp (ref "U3")
      (value "TS5A23159DGS")
      (footprint "eagle-import:MSOP10")
      (libsource (lib "eagle-import") (part "TS5A23159DGS"))
    )
    (comp (ref "U4")
      (value "TPS79933DDC")
      (footprint "eagle-import:SOT-23-5")
      (libsource (lib "eagle-import") (part "TPS799DDC33"))
    )
    (comp (ref "U5")
      (value "OPA2344EA")
      (footprint "eagle-import:MSO8_AEL")
      (libsource (lib "eagle-import") (part "OPA2344EA"))
    )
    (comp (ref "U6")
      (value "TPS3808G01DBV")
      (footprint "eagle-import:SOT-23")
      (libsource (lib "eagle-import") (part "TPS3808GDBV01"))
    )
    (comp (ref "U7")
      (value "NJU7108F3")
      (footprint "eagle-import:SC88A")
      (libsource (lib "eagle-import") (part "NJU7108F3"))
    )
    (comp (ref "U8")
      (value "OPA2314AIDGK")
      (footprint "eagle-import:MSO8_AEL")
      (libsource (lib "eagle-import") (part "OPA2344EA"))
    )
    (comp (ref "U9")
      (value "TS5A23159DGS")
      (footprint "eagle-import:MSOP10")
      (libsource (lib "eagle-import") (part "TS5A23159DGS"))
    )
    (comp (ref "U10")
      (value "74VHC4052AFT")
      (footprint "eagle-import:TSSOP16-P-044-065A")
      (libsource (lib "eagle-import") (part "744052AFTVHC"))
    )
    (comp (ref "U11")
      (value "AD8227ARZ")
      (footprint "eagle-import:SO8_AEL")
      (libsource (lib "eagle-import") (part "AD8227RZA"))
    )
  )
  (nets
    (net (code "1") (name "0V") (class "Default")
      (node (ref "C1") (pin "2") (pinfunction "2_2") (pintype "passive"))
      (node (ref "C17") (pin "2") (pinfunction "2_2") (pintype "passive"))
      (node (ref "C23") (pin "POS") (pinfunction "POS_POS") (pintype "passive"))
      (node (ref "C3") (pin "1") (pinfunction "1_1") (pintype "passive"))
      (node (ref "C5") (pin "1") (pinfunction "1_1") (pintype "passive"))
      (node (ref "D3") (pin "1") (pinfunction "A_1") (pintype "passive"))
      (node (ref "D3") (pin "2") (pinfunction "C_2") (pintype "passive"))
      (node (ref "R1") (pin "1") (pinfunction "1_1") (pintype "passive"))
      (node (ref "R13") (pin "2") (pinfunction "2_2") (pintype "passive"))
      (node (ref "R15") (pin "2") (pinfunction "2_2") (pintype "passive"))
      (node (ref "R21") (pin "1") (pinfunction "1_1") (pintype "passive"))
      (node (ref "R29") (pin "1") (pinfunction "1_1") (pintype "passive"))
      (node (ref "R40") (pin "1") (pinfunction "1_1") (pintype "passive"))
      (node (ref "R41") (pin "1") (pinfunction "1_1") (pintype "passive"))
      (node (ref "R46") (pin "2") (pinfunction "2_2") (pintype "passive"))
      (node (ref "TP7") (pin "1") (pinfunction "MP_1") (pintype "passive"))
      (node (ref "U1") (pin "5") (pinfunction "+IN_5") (pintype "input"))
      (node (ref "U8") (pin "5") (pinfunction "+IN_5") (pintype "input"))
    )
    (net (code "2") (name "AGND") (class "Default")
      (node (ref "C12") (pin "2") (pinfunction "2_2") (pintype "passive"))
      (node (ref "C13") (pin "2") (pinfunction "2_2") (pintype "passive"))
      (node (ref "C15") (pin "1") (pinfunction "1_1") (pintype "passive"))
      (node (ref "C16") (pin "2") (pinfunction "2_2") (pintype "passive"))
      (node (ref "C18") (pin "2") (pinfunction "2_2") (pintype "passive"))
      (node (ref "C20") (pin "2") (pinfunction "2_2") (pintype "passive"))
      (node (ref "C21") (pin "2") (pinfunction "2_2") (pintype "passive"))
      (node (ref "C22") (pin "2") (pinfunction "2_2") (pintype "passive"))
      (node (ref "C23") (pin "NEG") (pinfunction "NEG_NEG") (pintype "passive"))
      (node (ref "C24") (pin "2") (pinfunction "2_2") (pintype "passive"))
      (node (ref "C25") (pin "2") (pinfunction "2_2") (pintype "passive"))
      (node (ref "C26") (pin "1") (pinfunction "1_1") (pintype "passive"))
      (node (ref "C27") (pin "2") (pinfunction "2_2") (pintype "passive"))
      (node (ref "C28") (pin "2") (pinfunction "2_2") (pintype "passive"))
      (node (ref "C29") (pin "2") (pinfunction "2_2") (pintype "passive"))
      (node (ref "C30") (pin "2") (pinfunction "2_2") (pintype "passive"))
      (node (ref "C31") (pin "2") (pinfunction "2_2") (pintype "passive"))
      (node (ref "C32") (pin "2") (pinfunction "2_2") (pintype "passive"))
      (node (ref "C33") (pin "2") (pinfunction "2_2") (pintype "passive"))
      (node (ref "C34") (pin "2") (pinfunction "2_2") (pintype "passive"))
      (node (ref "C35") (pin "2") (pinfunction "2_2") (pintype "passive"))
      (node (ref "C36") (pin "2") (pinfunction "2_2") (pintype "passive"))
      (node (ref "C37") (pin "2") (pinfunction "2_2") (pintype "passive"))
      (node (ref "C38") (pin "2") (pinfunction "2_2") (pintype "passive"))
      (node (ref "C39") (pin "2") (pinfunction "2_2") (pintype "passive"))
      (node (ref "C40") (pin "2") (pinfunction "2_2") (pintype "passive"))
      (node (ref "C41") (pin "2") (pinfunction "2_2") (pintype "passive"))
      (node (ref "C8") (pin "NEG") (pinfunction "NEG_NEG") (pintype "passive"))
      (node (ref "C9") (pin "2") (pinfunction "2_2") (pintype "passive"))
      (node (ref "CN16") (pin "51") (pinfunction "G1_51") (pintype "bidirectional"))
      (node (ref "CN16") (pin "52") (pinfunction "G2_52") (pintype "bidirectional"))
      (node (ref "CN17") (pin "51") (pinfunction "G1_51") (pintype "bidirectional"))
      (node (ref "CN17") (pin "52") (pinfunction "G2_52") (pintype "bidirectional"))
      (node (ref "CN4") (pin "3") (pinfunction "3_3") (pintype "bidirectional"))
      (node (ref "CN4") (pin "4") (pinfunction "4_4") (pintype "bidirectional"))
      (node (ref "D1") (pin "1") (pinfunction "A_1") (pintype "passive"))
      (node (ref "D2") (pin "1") (pinfunction "A_1") (pintype "passive"))
      (node (ref "L3") (pin "2") (pinfunction "3_2") (pintype "passive"))
      (node (ref "R32") (pin "1") (pinfunction "1_1") (pintype "passive"))
      (node (ref "R43") (pin "1") (pinfunction "1_1") (pintype "passive"))
      (node (ref "TP9") (pin "1") (pinfunction "MP_1") (pintype "passive"))
      (node (ref "U1") (pin "4") (pinfunction "V-_4") (pintype "power_in"))
      (node (ref "U10") (pin "6") (pinfunction "INH_6") (pintype "input"))
      (node (ref "U10") (pin "7") (pinfunction "GND_7") (pintype "power_in"))
      (node (ref "U10") (pin "8") (pinfunction "GND_8") (pintype "input"))
      (node (ref "U11") (pin "5") (pinfunction "V-_5") (pintype "power_in"))
      (node (ref "U12") (pin "8") (pinfunction "V-_8") (pintype "power_in"))
      (node (ref "U13") (pin "8") (pinfunction "V-_8") (pintype "power_in"))
      (node (ref "U14") (pin "8") (pinfunction "V-_8") (pintype "power_in"))
      (node (ref "U15") (pin "8") (pinfunction "V-_8") (pintype "power_in"))
      (node (ref "U16") (pin "8") (pinfunction "V-_8") (pintype "power_in"))
      (node (ref "U17") (pin "8") (pinfunction "V-_8") (pintype "power_in"))
      (node (ref "U18") (pin "8") (pinfunction "V-_8") (pintype "power_in"))
      (node (ref "U19") (pin "8") (pinfunction "V-_8") (pintype "power_in"))
      (node (ref "U2") (pin "4") (pinfunction "V-_4") (pintype "power_in"))
      (node (ref "U20") (pin "8") (pinfunction "V-_8") (pintype "power_in"))
      (node (ref "U21") (pin "8") (pinfunction "V-_8") (pintype "power_in"))
      (node (ref "U22") (pin "8") (pinfunction "V-_8") (pintype "power_in"))
      (node (ref "U23") (pin "8") (pinfunction "V-_8") (pintype "power_in"))
      (node (ref "U24") (pin "8") (pinfunction "V-_8") (pintype "power_in"))
      (node (ref "U25") (pin "8") (pinfunction "V-_8") (pintype "power_in"))
      (node (ref "U3") (pin "3") (pinfunction "V-_3") (pintype "power_in"))
      (node (ref "U4") (pin "2") (pinfunction "GND_2") (pintype "passive"))
      (node (ref "U5") (pin "4") (pinfunction "V-_4") (pintype "power_in"))
      (node (ref "U7") (pin "2") (pinfunction "V-_2") (pintype "power_in"))
      (node (ref "U8") (pin "4") (pinfunction "V-_4") (pintype "power_in"))
      (node (ref "U9") (pin "3") (pinfunction "V-_3") (pintype "power_in"))
    )
    (net (code "3") (name "AMP_0") (class "Default")
      (node (ref "U10") (pin "10") (pinfunction "A_10") (pintype "input"))
      (node (ref "U27") (pin "19") (pinfunction "1-14_19") (pintype "bidirectional"))
    )
    (net (code "4") (name "AMP_1") (class "Default")
      (node (ref "U10") (pin "9") (pinfunction "B_9") (pintype "input"))
      (node (ref "U27") (pin "20") (pinfunction "1-15_20") (pintype "bidirectional"))
    )
    (net (code "5") (name "ANALOG{slash}~{DDS}") (class "Default")
      (node (ref "R70") (pin "1") (pinfunction "1_1") (pintype "passive"))
      (node (ref "U3") (pin "5") (pinfunction "IN_5") (pintype "input"))
    )
    (net (code "6") (name "BATT+") (class "Default")
      (node (ref "F1") (pin "2") (pinfunction "2_2") (pintype "passive"))
      (node (ref "L3") (pin "4") (pinfunction "2_4") (pintype "passive"))
      (node (ref "L5") (pin "1") (pinfunction "1_1") (pintype "passive"))
    )
    (net (code "7") (name "BATT-") (class "Default")
      (node (ref "CN3") (pin "3") (pinfunction "3_3") (pintype "bidirectional"))
      (node (ref "CN3") (pin "4") (pinfunction "4_4") (pintype "bidirectional"))
      (node (ref "L3") (pin "3") (pinfunction "4_3") (pintype "passive"))
      (node (ref "L5") (pin "2") (pinfunction "3_2") (pintype "passive"))
    )
    (net (code "8") (name "CH_0") (class "Default")
      (node (ref "R68") (pin "1") (pinfunction "1_1") (pintype "passive"))
      (node (ref "U12") (pin "11") (pinfunction "A_11") (pintype "input"))
      (node (ref "U13") (pin "11") (pinfunction "A_11") (pintype "input"))
      (node (ref "U14") (pin "11") (pinfunction "A_11") (pintype "input"))
      (node (ref "U15") (pin "11") (pinfunction "A_11") (pintype "input"))
      (node (ref "U16") (pin "11") (pinfunction "A_11") (pintype "input"))
      (node (ref "U17") (pin "11") (pinfunction "A_11") (pintype "input"))
      (node (ref "U18") (pin "11") (pinfunction "A_11") (pintype "input"))
      (node (ref "U19") (pin "11") (pinfunction "A_11") (pintype "input"))
      (node (ref "U20") (pin "11") (pinfunction "A_11") (pintype "input"))
      (node (ref "U21") (pin "11") (pinfunction "A_11") (pintype "input"))
      (node (ref "U22") (pin "11") (pinfunction "A_11") (pintype "input"))
      (node (ref "U23") (pin "11") (pinfunction "A_11") (pintype "input"))
      (node (ref "U24") (pin "11") (pinfunction "A_11") (pintype "input"))
      (node (ref "U25") (pin "11") (pinfunction "A_11") (pintype "input"))
    )
    (net (code "9") (name "CH_1") (class "Default")
      (node (ref "R69") (pin "1") (pinfunction "1_1") (pintype "passive"))
      (node (ref "U12") (pin "10") (pinfunction "B_10") (pintype "input"))
      (node (ref "U13") (pin "10") (pinfunction "B_10") (pintype "input"))
      (node (ref "U14") (pin "10") (pinfunction "B_10") (pintype "input"))
      (node (ref "U15") (pin "10") (pinfunction "B_10") (pintype "input"))
      (node (ref "U16") (pin "10") (pinfunction "B_10") (pintype "input"))
      (node (ref "U17") (pin "10") (pinfunction "B_10") (pintype "input"))
      (node (ref "U18") (pin "10") (pinfunction "B_10") (pintype "input"))
      (node (ref "U19") (pin "10") (pinfunction "B_10") (pintype "input"))
      (node (ref "U20") (pin "10") (pinfunction "B_10") (pintype "input"))
      (node (ref "U21") (pin "10") (pinfunction "B_10") (pintype "input"))
      (node (ref "U22") (pin "10") (pinfunction "B_10") (pintype "input"))
      (node (ref "U23") (pin "10") (pinfunction "B_10") (pintype "input"))
      (node (ref "U24") (pin "10") (pinfunction "B_10") (pintype "input"))
      (node (ref "U25") (pin "10") (pinfunction "B_10") (pintype "input"))
    )
    (net (code "10") (name "CH_2") (class "Default")
      (node (ref "R67") (pin "1") (pinfunction "1_1") (pintype "passive"))
      (node (ref "U12") (pin "9") (pinfunction "C_9") (pintype "input"))
      (node (ref "U13") (pin "9") (pinfunction "C_9") (pintype "input"))
      (node (ref "U14") (pin "9") (pinfunction "C_9") (pintype "input"))
      (node (ref "U15") (pin "9") (pinfunction "C_9") (pintype "input"))
      (node (ref "U16") (pin "9") (pinfunction "C_9") (pintype "input"))
      (node (ref "U17") (pin "9") (pinfunction "C_9") (pintype "input"))
      (node (ref "U18") (pin "9") (pinfunction "C_9") (pintype "input"))
      (node (ref "U19") (pin "9") (pinfunction "C_9") (pintype "input"))
      (node (ref "U20") (pin "9") (pinfunction "C_9") (pintype "input"))
      (node (ref "U21") (pin "9") (pinfunction "C_9") (pintype "input"))
      (node (ref "U22") (pin "9") (pinfunction "C_9") (pintype "input"))
      (node (ref "U23") (pin "9") (pinfunction "C_9") (pintype "input"))
      (node (ref "U24") (pin "9") (pinfunction "C_9") (pintype "input"))
      (node (ref "U25") (pin "9") (pinfunction "C_9") (pintype "input"))
    )
    (net (code "11") (name "CURRENT_MON") (class "Default")
      (node (ref "R58") (pin "1") (pinfunction "1_1") (pintype "passive"))
      (node (ref "U11") (pin "7") (pinfunction "OUT_7") (pintype "output"))
    )
    (net (code "12") (name "DGND") (class "Default")
      (node (ref "C10") (pin "2") (pinfunction "2_2") (pintype "passive"))
      (node (ref "C11") (pin "2") (pinfunction "2_2") (pintype "passive"))
      (node (ref "C42") (pin "2") (pinfunction "2_2") (pintype "passive"))
      (node (ref "C43") (pin "2") (pinfunction "2_2") (pintype "passive"))
      (node (ref "C44") (pin "2") (pinfunction "2_2") (pintype "passive"))
      (node (ref "C45") (pin "2") (pinfunction "2_2") (pintype "passive"))
      (node (ref "C46") (pin "NEG") (pinfunction "NEG_NEG") (pintype "passive"))
      (node (ref "C47") (pin "2") (pinfunction "2_2") (pintype "passive"))
      (node (ref "C48") (pin "1") (pinfunction "1_1") (pintype "passive"))
      (node (ref "C49") (pin "1") (pinfunction "1_1") (pintype "passive"))
      (node (ref "C50") (pin "1") (pinfunction "1_1") (pintype "passive"))
      (node (ref "C51") (pin "1") (pinfunction "1_1") (pintype "passive"))
      (node (ref "C52") (pin "2") (pinfunction "2_2") (pintype "passive"))
      (node (ref "C53") (pin "2") (pinfunction "2_2") (pintype "passive"))
      (node (ref "C54") (pin "2") (pinfunction "2_2") (pintype "passive"))
      (node (ref "C55") (pin "2") (pinfunction "2_2") (pintype "passive"))
      (node (ref "C56") (pin "2") (pinfunction "2_2") (pintype "passive"))
      (node (ref "C57") (pin "2") (pinfunction "2_2") (pintype "passive"))
      (node (ref "C58") (pin "2") (pinfunction "2_2") (pintype "passive"))
      (node (ref "C59") (pin "2") (pinfunction "2_2") (pintype "passive"))
      (node (ref "C60") (pin "2") (pinfunction "2_2") (pintype "passive"))
      (node (ref "C61") (pin "2") (pinfunction "2_2") (pintype "passive"))
      (node (ref "C62") (pin "2") (pinfunction "2_2") (pintype "passive"))
      (node (ref "CN10") (pin "4") (pinfunction "4_4") (pintype "bidirectional"))
      (node (ref "CN11") (pin "4") (pinfunction "4_4") (pintype "bidirectional"))
      (node (ref "CN18") (pin "10") (pinfunction "10_10") (pintype "bidirectional"))
      (node (ref "CN18") (pin "2") (pinfunction "2_2") (pintype "bidirectional"))
      (node (ref "CN19") (pin "10") (pinfunction "10_10") (pintype "bidirectional"))
      (node (ref "CN19") (pin "2") (pinfunction "2_2") (pintype "bidirectional"))
      (node (ref "CN19") (pin "4") (pinfunction "4_4") (pintype "bidirectional"))
      (node (ref "CN20") (pin "2") (pinfunction "2_2") (pintype "bidirectional"))
      (node (ref "CN20") (pin "8") (pinfunction "8_8") (pintype "bidirectional"))
      (node (ref "CN7") (pin "2") (pinfunction "2_2") (pintype "bidirectional"))
      (node (ref "D4") (pin "C") (pinfunction "K1_C") (pintype "passive"))
      (node (ref "L5") (pin "3") (pinfunction "4_3") (pintype "passive"))
      (node (ref "M1") (pin "CASE1") (pinfunction "P$1_CASE1") (pintype "bidirectional"))
      (node (ref "M2") (pin "CASE1") (pinfunction "P$1_CASE1") (pintype "bidirectional"))
      (node (ref "M3") (pin "CASE1") (pinfunction "P$1_CASE1") (pintype "bidirectional"))
      (node (ref "R25") (pin "1") (pinfunction "1_1") (pintype "passive"))
      (node (ref "R65") (pin "1") (pinfunction "1_1") (pintype "passive"))
      (node (ref "R77") (pin "1") (pinfunction "1_1") (pintype "passive"))
      (node (ref "SW1") (pin "7") (pinfunction "BRACKET_7") (pintype "passive"))
      (node (ref "SW1") (pin "8") (pinfunction "BRACKET_8") (pintype "passive"))
      (node (ref "SW2") (pin "3") (pinfunction "NC_3") (pintype "passive"))
      (node (ref "SW2") (pin "7") (pinfunction "BRACKET_7") (pintype "passive"))
      (node (ref "SW2") (pin "8") (pinfunction "BRACKET_8") (pintype "passive"))
      (node (ref "SW3") (pin "3") (pinfunction "NC_3") (pintype "passive"))
      (node (ref "SW3") (pin "7") (pinfunction "BRACKET_7") (pintype "passive"))
      (node (ref "SW3") (pin "8") (pinfunction "BRACKET_8") (pintype "passive"))
      (node (ref "SW4") (pin "3") (pinfunction "NC_3") (pintype "passive"))
      (node (ref "SW4") (pin "7") (pinfunction "BRACKET_7") (pintype "passive"))
      (node (ref "SW4") (pin "8") (pinfunction "BRACKET_8") (pintype "passive"))
      (node (ref "TP15") (pin "1") (pinfunction "MP_1") (pintype "passive"))
      (node (ref "U26") (pin "2") (pinfunction "GND_2") (pintype "passive"))
      (node (ref "U27") (pin "1") (pinfunction "GND_1_1") (pintype "power_in"))
      (node (ref "U27") (pin "10") (pinfunction "GND_2_10") (pintype "power_in"))
      (node (ref "U27") (pin "11") (pinfunction "GND_3_11") (pintype "power_in"))
      (node (ref "U27") (pin "32") (pinfunction "GND_4_32") (pintype "power_in"))
      (node (ref "U27") (pin "43") (pinfunction "1-32/DEV_OE_43") (pintype "bidirectional"))
      (node (ref "U27") (pin "44") (pinfunction "1-33/~{DEV_CLR}_44") (pintype "bidirectional"))
      (node (ref "U27") (pin "46") (pinfunction "GND_5_46") (pintype "power_in"))
      (node (ref "U27") (pin "60") (pinfunction "GND_6_60") (pintype "power_in"))
      (node (ref "U27") (pin "65") (pinfunction "GND_7_65") (pintype "power_in"))
      (node (ref "U27") (pin "79") (pinfunction "GND_8_79") (pintype "power_in"))
      (node (ref "U27") (pin "93") (pinfunction "GND_9_93") (pintype "power_in"))
      (node (ref "U28") (pin "2") (pinfunction "GND_2") (pintype "passive"))
      (node (ref "U29") (pin "10") (pinfunction "GND_10") (pintype "power_in"))
      (node (ref "U30") (pin "2") (pinfunction "C_2") (pintype "passive"))
      (node (ref "U6") (pin "2") (pinfunction "GND_2") (pintype "power_in"))
    )
    (net (code "13") (name "DISP1") (class "Default")
      (node (ref "TP14") (pin "P$1") (pinfunction "MP_P$1") (pintype "passive"))
      (node (ref "U27") (pin "56") (pinfunction "2-5_56") (pintype "bidirectional"))
      (node (ref "U29") (pin "9") (pinfunction "A8_9") (pintype "input"))
    )
    (net (code "14") (name "DISP2") (class "Default")
      (node (ref "TP13") (pin "P$1") (pinfunction "MP_P$1") (pintype "passive"))
      (node (ref "U27") (pin "57") (pinfunction "2-6_57") (pintype "bidirectional"))
      (node (ref "U29") (pin "8") (pinfunction "A7_8") (pintype "input"))
    )
    (net (code "15") (name "DISP3") (class "Default")
      (node (ref "TP12") (pin "P$1") (pinfunction "MP_P$1") (pintype "passive"))
      (node (ref "U27") (pin "58") (pinfunction "2-7_58") (pintype "bidirectional"))
      (node (ref "U29") (pin "7") (pinfunction "A6_7") (pintype "input"))
    )
    (net (code "16") (name "DISP4") (class "Default")
      (node (ref "TP11") (pin "P$1") (pinfunction "MP_P$1") (pintype "passive"))
      (node (ref "U27") (pin "61") (pinfunction "2-8_61") (pintype "bidirectional"))
      (node (ref "U29") (pin "6") (pinfunction "A5_6") (pintype "input"))
    )
    (net (code "17") (name "DO2") (class "Default")
      (node (ref "U29") (pin "12") (pinfunction "Y7_12") (pintype "output"))
    )
    (net (code "18") (name "DO3") (class "Default")
      (node (ref "U29") (pin "13") (pinfunction "Y6_13") (pintype "output"))
    )
    (net (code "19") (name "DO4") (class "Default")
      (node (ref "U29") (pin "14") (pinfunction "Y5_14") (pintype "output"))
    )
    (net (code "20") (name "DRIVE01+") (class "Default")
      (node (ref "CN16") (pin "25") (pinfunction "25_25") (pintype "bidirectional"))
      (node (ref "U12") (pin "13") (pinfunction "0_13") (pintype "bidirectional"))
    )
    (net (code "21") (name "DRIVE01-") (class "Default")
      (node (ref "CN16") (pin "50") (pinfunction "50_50") (pintype "bidirectional"))
      (node (ref "U18") (pin "13") (pinfunction "0_13") (pintype "bidirectional"))
    )
    (net (code "22") (name "DRIVE02+") (class "Default")
      (node (ref "CN16") (pin "24") (pinfunction "24_24") (pintype "bidirectional"))
      (node (ref "U12") (pin "14") (pinfunction "1_14") (pintype "bidirectional"))
    )
    (net (code "23") (name "DRIVE02-") (class "Default")
      (node (ref "CN16") (pin "49") (pinfunction "49_49") (pintype "bidirectional"))
      (node (ref "U18") (pin "14") (pinfunction "1_14") (pintype "bidirectional"))
    )
    (net (code "24") (name "DRIVE03+") (class "Default")
      (node (ref "CN16") (pin "23") (pinfunction "23_23") (pintype "bidirectional"))
      (node (ref "U12") (pin "15") (pinfunction "2_15") (pintype "bidirectional"))
    )
    (net (code "25") (name "DRIVE03-") (class "Default")
      (node (ref "CN16") (pin "48") (pinfunction "48_48") (pintype "bidirectional"))
      (node (ref "U18") (pin "15") (pinfunction "2_15") (pintype "bidirectional"))
    )
    (net (code "26") (name "DRIVE04+") (class "Default")
      (node (ref "CN16") (pin "22") (pinfunction "22_22") (pintype "bidirectional"))
      (node (ref "U12") (pin "12") (pinfunction "3_12") (pintype "bidirectional"))
    )
    (net (code "27") (name "DRIVE04-") (class "Default")
      (node (ref "CN16") (pin "47") (pinfunction "47_47") (pintype "bidirectional"))
      (node (ref "U18") (pin "12") (pinfunction "3_12") (pintype "bidirectional"))
    )
    (net (code "28") (name "DRIVE05+") (class "Default")
      (node (ref "CN16") (pin "21") (pinfunction "21_21") (pintype "bidirectional"))
      (node (ref "U12") (pin "1") (pinfunction "4_1") (pintype "bidirectional"))
    )
    (net (code "29") (name "DRIVE05-") (class "Default")
      (node (ref "CN16") (pin "46") (pinfunction "46_46") (pintype "bidirectional"))
      (node (ref "U18") (pin "1") (pinfunction "4_1") (pintype "bidirectional"))
    )
    (net (code "30") (name "DRIVE06+") (class "Default")
      (node (ref "CN16") (pin "20") (pinfunction "20_20") (pintype "bidirectional"))
      (node (ref "U12") (pin "5") (pinfunction "5_5") (pintype "bidirectional"))
    )
    (net (code "31") (name "DRIVE06-") (class "Default")
      (node (ref "CN16") (pin "45") (pinfunction "45_45") (pintype "bidirectional"))
      (node (ref "U18") (pin "5") (pinfunction "5_5") (pintype "bidirectional"))
    )
    (net (code "32") (name "DRIVE07+") (class "Default")
      (node (ref "CN16") (pin "19") (pinfunction "19_19") (pintype "bidirectional"))
      (node (ref "U12") (pin "2") (pinfunction "6_2") (pintype "bidirectional"))
    )
    (net (code "33") (name "DRIVE07-") (class "Default")
      (node (ref "CN16") (pin "44") (pinfunction "44_44") (pintype "bidirectional"))
      (node (ref "U18") (pin "2") (pinfunction "6_2") (pintype "bidirectional"))
    )
    (net (code "34") (name "DRIVE08+") (class "Default")
      (node (ref "CN16") (pin "18") (pinfunction "18_18") (pintype "bidirectional"))
      (node (ref "U12") (pin "4") (pinfunction "7_4") (pintype "bidirectional"))
    )
    (net (code "35") (name "DRIVE08-") (class "Default")
      (node (ref "CN16") (pin "43") (pinfunction "43_43") (pintype "bidirectional"))
      (node (ref "U18") (pin "4") (pinfunction "7_4") (pintype "bidirectional"))
    )
    (net (code "36") (name "DRIVE09+") (class "Default")
      (node (ref "CN16") (pin "17") (pinfunction "17_17") (pintype "bidirectional"))
      (node (ref "U14") (pin "13") (pinfunction "0_13") (pintype "bidirectional"))
    )
    (net (code "37") (name "DRIVE09-") (class "Default")
      (node (ref "CN16") (pin "42") (pinfunction "42_42") (pintype "bidirectional"))
      (node (ref "U20") (pin "13") (pinfunction "0_13") (pintype "bidirectional"))
    )
    (net (code "38") (name "DRIVE10+") (class "Default")
      (node (ref "CN16") (pin "16") (pinfunction "16_16") (pintype "bidirectional"))
      (node (ref "U14") (pin "14") (pinfunction "1_14") (pintype "bidirectional"))
    )
    (net (code "39") (name "DRIVE10-") (class "Default")
      (node (ref "CN16") (pin "41") (pinfunction "41_41") (pintype "bidirectional"))
      (node (ref "U20") (pin "14") (pinfunction "1_14") (pintype "bidirectional"))
    )
    (net (code "40") (name "DRIVE11+") (class "Default")
      (node (ref "CN16") (pin "15") (pinfunction "15_15") (pintype "bidirectional"))
      (node (ref "U14") (pin "15") (pinfunction "2_15") (pintype "bidirectional"))
    )
    (net (code "41") (name "DRIVE11-") (class "Default")
      (node (ref "CN16") (pin "40") (pinfunction "40_40") (pintype "bidirectional"))
      (node (ref "U20") (pin "15") (pinfunction "2_15") (pintype "bidirectional"))
    )
    (net (code "42") (name "DRIVE12+") (class "Default")
      (node (ref "CN16") (pin "14") (pinfunction "14_14") (pintype "bidirectional"))
      (node (ref "U14") (pin "12") (pinfunction "3_12") (pintype "bidirectional"))
    )
    (net (code "43") (name "DRIVE12-") (class "Default")
      (node (ref "CN16") (pin "39") (pinfunction "39_39") (pintype "bidirectional"))
      (node (ref "U20") (pin "12") (pinfunction "3_12") (pintype "bidirectional"))
    )
    (net (code "44") (name "DRIVE13+") (class "Default")
      (node (ref "CN16") (pin "13") (pinfunction "13_13") (pintype "bidirectional"))
      (node (ref "U14") (pin "1") (pinfunction "4_1") (pintype "bidirectional"))
    )
    (net (code "45") (name "DRIVE13-") (class "Default")
      (node (ref "CN16") (pin "38") (pinfunction "38_38") (pintype "bidirectional"))
      (node (ref "U20") (pin "1") (pinfunction "4_1") (pintype "bidirectional"))
    )
    (net (code "46") (name "DRIVE14+") (class "Default")
      (node (ref "CN16") (pin "12") (pinfunction "12_12") (pintype "bidirectional"))
      (node (ref "U14") (pin "5") (pinfunction "5_5") (pintype "bidirectional"))
    )
    (net (code "47") (name "DRIVE14-") (class "Default")
      (node (ref "CN16") (pin "37") (pinfunction "37_37") (pintype "bidirectional"))
      (node (ref "U20") (pin "5") (pinfunction "5_5") (pintype "bidirectional"))
    )
    (net (code "48") (name "DRIVE15+") (class "Default")
      (node (ref "CN16") (pin "11") (pinfunction "11_11") (pintype "bidirectional"))
      (node (ref "U14") (pin "2") (pinfunction "6_2") (pintype "bidirectional"))
    )
    (net (code "49") (name "DRIVE15-") (class "Default")
      (node (ref "CN16") (pin "36") (pinfunction "36_36") (pintype "bidirectional"))
      (node (ref "U20") (pin "2") (pinfunction "6_2") (pintype "bidirectional"))
    )
    (net (code "50") (name "DRIVE16+") (class "Default")
      (node (ref "CN16") (pin "10") (pinfunction "10_10") (pintype "bidirectional"))
      (node (ref "U14") (pin "4") (pinfunction "7_4") (pintype "bidirectional"))
    )
    (net (code "51") (name "DRIVE16-") (class "Default")
      (node (ref "CN16") (pin "35") (pinfunction "35_35") (pintype "bidirectional"))
      (node (ref "U20") (pin "4") (pinfunction "7_4") (pintype "bidirectional"))
    )
    (net (code "52") (name "DRIVE17+") (class "Default")
      (node (ref "CN16") (pin "9") (pinfunction "9_9") (pintype "bidirectional"))
      (node (ref "U16") (pin "13") (pinfunction "0_13") (pintype "bidirectional"))
    )
    (net (code "53") (name "DRIVE17-") (class "Default")
      (node (ref "CN16") (pin "34") (pinfunction "34_34") (pintype "bidirectional"))
      (node (ref "U22") (pin "13") (pinfunction "0_13") (pintype "bidirectional"))
    )
    (net (code "54") (name "DRIVE18+") (class "Default")
      (node (ref "CN16") (pin "8") (pinfunction "8_8") (pintype "bidirectional"))
      (node (ref "U16") (pin "14") (pinfunction "1_14") (pintype "bidirectional"))
    )
    (net (code "55") (name "DRIVE18-") (class "Default")
      (node (ref "CN16") (pin "33") (pinfunction "33_33") (pintype "bidirectional"))
      (node (ref "U22") (pin "14") (pinfunction "1_14") (pintype "bidirectional"))
    )
    (net (code "56") (name "DRIVE19+") (class "Default")
      (node (ref "CN16") (pin "7") (pinfunction "7_7") (pintype "bidirectional"))
      (node (ref "U16") (pin "15") (pinfunction "2_15") (pintype "bidirectional"))
    )
    (net (code "57") (name "DRIVE19-") (class "Default")
      (node (ref "CN16") (pin "32") (pinfunction "32_32") (pintype "bidirectional"))
      (node (ref "U22") (pin "15") (pinfunction "2_15") (pintype "bidirectional"))
    )
    (net (code "58") (name "DRIVE20+") (class "Default")
      (node (ref "CN16") (pin "6") (pinfunction "6_6") (pintype "bidirectional"))
      (node (ref "U16") (pin "12") (pinfunction "3_12") (pintype "bidirectional"))
    )
    (net (code "59") (name "DRIVE20-") (class "Default")
      (node (ref "CN16") (pin "31") (pinfunction "31_31") (pintype "bidirectional"))
      (node (ref "U22") (pin "12") (pinfunction "3_12") (pintype "bidirectional"))
    )
    (net (code "60") (name "DRIVE21+") (class "Default")
      (node (ref "CN16") (pin "5") (pinfunction "5_5") (pintype "bidirectional"))
      (node (ref "U16") (pin "1") (pinfunction "4_1") (pintype "bidirectional"))
    )
    (net (code "61") (name "DRIVE21-") (class "Default")
      (node (ref "CN16") (pin "30") (pinfunction "30_30") (pintype "bidirectional"))
      (node (ref "U22") (pin "1") (pinfunction "4_1") (pintype "bidirectional"))
    )
    (net (code "62") (name "DRIVE22+") (class "Default")
      (node (ref "CN16") (pin "4") (pinfunction "4_4") (pintype "bidirectional"))
      (node (ref "U16") (pin "5") (pinfunction "5_5") (pintype "bidirectional"))
    )
    (net (code "63") (name "DRIVE22-") (class "Default")
      (node (ref "CN16") (pin "29") (pinfunction "29_29") (pintype "bidirectional"))
      (node (ref "U22") (pin "5") (pinfunction "5_5") (pintype "bidirectional"))
    )
    (net (code "64") (name "DRIVE23+") (class "Default")
      (node (ref "CN16") (pin "3") (pinfunction "3_3") (pintype "bidirectional"))
      (node (ref "U16") (pin "2") (pinfunction "6_2") (pintype "bidirectional"))
    )
    (net (code "65") (name "DRIVE23-") (class "Default")
      (node (ref "CN16") (pin "28") (pinfunction "28_28") (pintype "bidirectional"))
      (node (ref "U22") (pin "2") (pinfunction "6_2") (pintype "bidirectional"))
    )
    (net (code "66") (name "DRIVE24+") (class "Default")
      (node (ref "CN16") (pin "2") (pinfunction "2_2") (pintype "bidirectional"))
      (node (ref "U16") (pin "4") (pinfunction "7_4") (pintype "bidirectional"))
    )
    (net (code "67") (name "DRIVE24-") (class "Default")
      (node (ref "CN16") (pin "27") (pinfunction "27_27") (pintype "bidirectional"))
      (node (ref "U22") (pin "4") (pinfunction "7_4") (pintype "bidirectional"))
    )
    (net (code "68") (name "DRIVE25+") (class "Default")
      (node (ref "CN17") (pin "25") (pinfunction "25_25") (pintype "bidirectional"))
      (node (ref "U24") (pin "13") (pinfunction "0_13") (pintype "bidirectional"))
    )
    (net (code "69") (name "DRIVE25-") (class "Default")
      (node (ref "CN17") (pin "50") (pinfunction "50_50") (pintype "bidirectional"))
      (node (ref "U17") (pin "13") (pinfunction "0_13") (pintype "bidirectional"))
    )
    (net (code "70") (name "DRIVE26+") (class "Default")
      (node (ref "CN17") (pin "24") (pinfunction "24_24") (pintype "bidirectional"))
      (node (ref "U24") (pin "14") (pinfunction "1_14") (pintype "bidirectional"))
    )
    (net (code "71") (name "DRIVE26-") (class "Default")
      (node (ref "CN17") (pin "49") (pinfunction "49_49") (pintype "bidirectional"))
      (node (ref "U17") (pin "14") (pinfunction "1_14") (pintype "bidirectional"))
    )
    (net (code "72") (name "DRIVE27+") (class "Default")
      (node (ref "CN17") (pin "23") (pinfunction "23_23") (pintype "bidirectional"))
      (node (ref "U24") (pin "15") (pinfunction "2_15") (pintype "bidirectional"))
    )
    (net (code "73") (name "DRIVE27-") (class "Default")
      (node (ref "CN17") (pin "48") (pinfunction "48_48") (pintype "bidirectional"))
      (node (ref "U17") (pin "15") (pinfunction "2_15") (pintype "bidirectional"))
    )
    (net (code "74") (name "DRIVE28+") (class "Default")
      (node (ref "CN17") (pin "22") (pinfunction "22_22") (pintype "bidirectional"))
      (node (ref "U24") (pin "12") (pinfunction "3_12") (pintype "bidirectional"))
    )
    (net (code "75") (name "DRIVE28-") (class "Default")
      (node (ref "CN17") (pin "47") (pinfunction "47_47") (pintype "bidirectional"))
      (node (ref "U17") (pin "12") (pinfunction "3_12") (pintype "bidirectional"))
    )
    (net (code "76") (name "DRIVE29+") (class "Default")
      (node (ref "CN17") (pin "21") (pinfunction "21_21") (pintype "bidirectional"))
      (node (ref "U24") (pin "1") (pinfunction "4_1") (pintype "bidirectional"))
    )
    (net (code "77") (name "DRIVE29-") (class "Default")
      (node (ref "CN17") (pin "46") (pinfunction "46_46") (pintype "bidirectional"))
      (node (ref "U17") (pin "1") (pinfunction "4_1") (pintype "bidirectional"))
    )
    (net (code "78") (name "DRIVE30+") (class "Default")
      (node (ref "CN17") (pin "20") (pinfunction "20_20") (pintype "bidirectional"))
      (node (ref "U24") (pin "5") (pinfunction "5_5") (pintype "bidirectional"))
    )
    (net (code "79") (name "DRIVE30-") (class "Default")
      (node (ref "CN17") (pin "45") (pinfunction "45_45") (pintype "bidirectional"))
      (node (ref "U17") (pin "5") (pinfunction "5_5") (pintype "bidirectional"))
    )
    (net (code "80") (name "DRIVE31+") (class "Default")
      (node (ref "CN17") (pin "19") (pinfunction "19_19") (pintype "bidirectional"))
      (node (ref "U24") (pin "2") (pinfunction "6_2") (pintype "bidirectional"))
    )
    (net (code "81") (name "DRIVE31-") (class "Default")
      (node (ref "CN17") (pin "44") (pinfunction "44_44") (pintype "bidirectional"))
      (node (ref "U17") (pin "2") (pinfunction "6_2") (pintype "bidirectional"))
    )
    (net (code "82") (name "DRIVE32+") (class "Default")
      (node (ref "CN17") (pin "18") (pinfunction "18_18") (pintype "bidirectional"))
      (node (ref "U24") (pin "4") (pinfunction "7_4") (pintype "bidirectional"))
    )
    (net (code "83") (name "DRIVE32-") (class "Default")
      (node (ref "CN17") (pin "43") (pinfunction "43_43") (pintype "bidirectional"))
      (node (ref "U17") (pin "4") (pinfunction "7_4") (pintype "bidirectional"))
    )
    (net (code "84") (name "DRIVE33+") (class "Default")
      (node (ref "CN17") (pin "17") (pinfunction "17_17") (pintype "bidirectional"))
      (node (ref "U13") (pin "13") (pinfunction "0_13") (pintype "bidirectional"))
    )
    (net (code "85") (name "DRIVE33-") (class "Default")
      (node (ref "CN17") (pin "42") (pinfunction "42_42") (pintype "bidirectional"))
      (node (ref "U19") (pin "13") (pinfunction "0_13") (pintype "bidirectional"))
    )
    (net (code "86") (name "DRIVE34+") (class "Default")
      (node (ref "CN17") (pin "16") (pinfunction "16_16") (pintype "bidirectional"))
      (node (ref "U13") (pin "14") (pinfunction "1_14") (pintype "bidirectional"))
    )
    (net (code "87") (name "DRIVE34-") (class "Default")
      (node (ref "CN17") (pin "41") (pinfunction "41_41") (pintype "bidirectional"))
      (node (ref "U19") (pin "14") (pinfunction "1_14") (pintype "bidirectional"))
    )
    (net (code "88") (name "DRIVE35+") (class "Default")
      (node (ref "CN17") (pin "15") (pinfunction "15_15") (pintype "bidirectional"))
      (node (ref "U13") (pin "15") (pinfunction "2_15") (pintype "bidirectional"))
    )
    (net (code "89") (name "DRIVE35-") (class "Default")
      (node (ref "CN17") (pin "40") (pinfunction "40_40") (pintype "bidirectional"))
      (node (ref "U19") (pin "15") (pinfunction "2_15") (pintype "bidirectional"))
    )
    (net (code "90") (name "DRIVE36+") (class "Default")
      (node (ref "CN17") (pin "14") (pinfunction "14_14") (pintype "bidirectional"))
      (node (ref "U13") (pin "12") (pinfunction "3_12") (pintype "bidirectional"))
    )
    (net (code "91") (name "DRIVE36-") (class "Default")
      (node (ref "CN17") (pin "39") (pinfunction "39_39") (pintype "bidirectional"))
      (node (ref "U19") (pin "12") (pinfunction "3_12") (pintype "bidirectional"))
    )
    (net (code "92") (name "DRIVE37+") (class "Default")
      (node (ref "CN17") (pin "13") (pinfunction "13_13") (pintype "bidirectional"))
      (node (ref "U13") (pin "1") (pinfunction "4_1") (pintype "bidirectional"))
    )
    (net (code "93") (name "DRIVE37-") (class "Default")
      (node (ref "CN17") (pin "38") (pinfunction "38_38") (pintype "bidirectional"))
      (node (ref "U19") (pin "1") (pinfunction "4_1") (pintype "bidirectional"))
    )
    (net (code "94") (name "DRIVE38+") (class "Default")
      (node (ref "CN17") (pin "12") (pinfunction "12_12") (pintype "bidirectional"))
      (node (ref "U13") (pin "5") (pinfunction "5_5") (pintype "bidirectional"))
    )
    (net (code "95") (name "DRIVE38-") (class "Default")
      (node (ref "CN17") (pin "37") (pinfunction "37_37") (pintype "bidirectional"))
      (node (ref "U19") (pin "5") (pinfunction "5_5") (pintype "bidirectional"))
    )
    (net (code "96") (name "DRIVE39+") (class "Default")
      (node (ref "CN17") (pin "11") (pinfunction "11_11") (pintype "bidirectional"))
      (node (ref "U13") (pin "2") (pinfunction "6_2") (pintype "bidirectional"))
    )
    (net (code "97") (name "DRIVE39-") (class "Default")
      (node (ref "CN17") (pin "36") (pinfunction "36_36") (pintype "bidirectional"))
      (node (ref "U19") (pin "2") (pinfunction "6_2") (pintype "bidirectional"))
    )
    (net (code "98") (name "DRIVE40+") (class "Default")
      (node (ref "CN17") (pin "10") (pinfunction "10_10") (pintype "bidirectional"))
      (node (ref "U13") (pin "4") (pinfunction "7_4") (pintype "bidirectional"))
    )
    (net (code "99") (name "DRIVE40-") (class "Default")
      (node (ref "CN17") (pin "35") (pinfunction "35_35") (pintype "bidirectional"))
      (node (ref "U19") (pin "4") (pinfunction "7_4") (pintype "bidirectional"))
    )
    (net (code "100") (name "DRIVE41+") (class "Default")
      (node (ref "CN17") (pin "9") (pinfunction "9_9") (pintype "bidirectional"))
      (node (ref "U15") (pin "13") (pinfunction "0_13") (pintype "bidirectional"))
    )
    (net (code "101") (name "DRIVE41-") (class "Default")
      (node (ref "CN17") (pin "34") (pinfunction "34_34") (pintype "bidirectional"))
      (node (ref "U21") (pin "13") (pinfunction "0_13") (pintype "bidirectional"))
    )
    (net (code "102") (name "DRIVE42+") (class "Default")
      (node (ref "CN17") (pin "8") (pinfunction "8_8") (pintype "bidirectional"))
      (node (ref "U15") (pin "14") (pinfunction "1_14") (pintype "bidirectional"))
    )
    (net (code "103") (name "DRIVE42-") (class "Default")
      (node (ref "CN17") (pin "33") (pinfunction "33_33") (pintype "bidirectional"))
      (node (ref "U21") (pin "14") (pinfunction "1_14") (pintype "bidirectional"))
    )
    (net (code "104") (name "DRIVE43+") (class "Default")
      (node (ref "CN17") (pin "7") (pinfunction "7_7") (pintype "bidirectional"))
      (node (ref "U15") (pin "15") (pinfunction "2_15") (pintype "bidirectional"))
    )
    (net (code "105") (name "DRIVE43-") (class "Default")
      (node (ref "CN17") (pin "32") (pinfunction "32_32") (pintype "bidirectional"))
      (node (ref "U21") (pin "15") (pinfunction "2_15") (pintype "bidirectional"))
    )
    (net (code "106") (name "DRIVE44+") (class "Default")
      (node (ref "CN17") (pin "6") (pinfunction "6_6") (pintype "bidirectional"))
      (node (ref "U15") (pin "12") (pinfunction "3_12") (pintype "bidirectional"))
    )
    (net (code "107") (name "DRIVE44-") (class "Default")
      (node (ref "CN17") (pin "31") (pinfunction "31_31") (pintype "bidirectional"))
      (node (ref "U21") (pin "12") (pinfunction "3_12") (pintype "bidirectional"))
    )
    (net (code "108") (name "DRIVE45+") (class "Default")
      (node (ref "CN17") (pin "5") (pinfunction "5_5") (pintype "bidirectional"))
      (node (ref "U15") (pin "1") (pinfunction "4_1") (pintype "bidirectional"))
    )
    (net (code "109") (name "DRIVE45-") (class "Default")
      (node (ref "CN17") (pin "30") (pinfunction "30_30") (pintype "bidirectional"))
      (node (ref "U21") (pin "1") (pinfunction "4_1") (pintype "bidirectional"))
    )
    (net (code "110") (name "DRIVE46+") (class "Default")
      (node (ref "CN17") (pin "4") (pinfunction "4_4") (pintype "bidirectional"))
      (node (ref "U15") (pin "5") (pinfunction "5_5") (pintype "bidirectional"))
    )
    (net (code "111") (name "DRIVE46-") (class "Default")
      (node (ref "CN17") (pin "29") (pinfunction "29_29") (pintype "bidirectional"))
      (node (ref "U21") (pin "5") (pinfunction "5_5") (pintype "bidirectional"))
    )
    (net (code "112") (name "DRIVE47+") (class "Default")
      (node (ref "CN17") (pin "3") (pinfunction "3_3") (pintype "bidirectional"))
      (node (ref "U15") (pin "2") (pinfunction "6_2") (pintype "bidirectional"))
    )
    (net (code "113") (name "DRIVE47-") (class "Default")
      (node (ref "CN17") (pin "28") (pinfunction "28_28") (pintype "bidirectional"))
      (node (ref "U21") (pin "2") (pinfunction "6_2") (pintype "bidirectional"))
    )
    (net (code "114") (name "DRIVE48+") (class "Default")
      (node (ref "CN17") (pin "2") (pinfunction "2_2") (pintype "bidirectional"))
      (node (ref "U15") (pin "4") (pinfunction "7_4") (pintype "bidirectional"))
    )
    (net (code "115") (name "DRIVE48-") (class "Default")
      (node (ref "CN17") (pin "27") (pinfunction "27_27") (pintype "bidirectional"))
      (node (ref "U21") (pin "4") (pinfunction "7_4") (pintype "bidirectional"))
    )
    (net (code "116") (name "DRIVE49+") (class "Default")
      (node (ref "CN16") (pin "1") (pinfunction "1_1") (pintype "bidirectional"))
      (node (ref "U23") (pin "13") (pinfunction "0_13") (pintype "bidirectional"))
    )
    (net (code "117") (name "DRIVE49-") (class "Default")
      (node (ref "CN16") (pin "26") (pinfunction "26_26") (pintype "bidirectional"))
      (node (ref "U25") (pin "13") (pinfunction "0_13") (pintype "bidirectional"))
    )
    (net (code "118") (name "DRIVE50+") (class "Default")
      (node (ref "CN17") (pin "1") (pinfunction "1_1") (pintype "bidirectional"))
      (node (ref "U23") (pin "14") (pinfunction "1_14") (pintype "bidirectional"))
    )
    (net (code "119") (name "DRIVE50-") (class "Default")
      (node (ref "CN17") (pin "26") (pinfunction "26_26") (pintype "bidirectional"))
      (node (ref "U25") (pin "14") (pinfunction "1_14") (pintype "bidirectional"))
    )
    (net (code "120") (name "EXT_IN_+") (class "Default")
      (node (ref "CN2") (pin "1") (pinfunction "1_1") (pintype "bidirectional"))
      (node (ref "CN2") (pin "2") (pinfunction "2_2") (pintype "bidirectional"))
      (node (ref "L2") (pin "4") (pinfunction "2_4") (pintype "passive"))
    )
    (net (code "121") (name "EXT_IN_-") (class "Default")
      (node (ref "CN2") (pin "3") (pinfunction "3_3") (pintype "bidirectional"))
      (node (ref "CN2") (pin "4") (pinfunction "4_4") (pintype "bidirectional"))
      (node (ref "L2") (pin "3") (pinfunction "4_3") (pintype "passive"))
    )
    (net (code "122") (name "EXT{slash}~{INT}") (class "Default")
      (node (ref "R71") (pin "1") (pinfunction "1_1") (pintype "passive"))
      (node (ref "U3") (pin "1") (pinfunction "IN_1") (pintype "input"))
    )
    (net (code "123") (name "FLAME_SYNC") (class "Default")
      (node (ref "U27") (pin "66") (pinfunction "2-11_66") (pintype "bidirectional"))
      (node (ref "U29") (pin "2") (pinfunction "A1_2") (pintype "input"))
      (node (ref "U29") (pin "3") (pinfunction "A2_3") (pintype "input"))
      (node (ref "U29") (pin "4") (pinfunction "A3_4") (pintype "input"))
      (node (ref "U29") (pin "5") (pinfunction "A4_5") (pintype "input"))
    )
    (net (code "124") (name "FSEL") (class "Default")
      (node (ref "CN19") (pin "11") (pinfunction "11_11") (pintype "bidirectional"))
      (node (ref "U27") (pin "71") (pinfunction "2-16_71") (pintype "bidirectional"))
    )
    (net (code "125") (name "FSYNC") (class "Default")
      (node (ref "CN19") (pin "1") (pinfunction "1_1") (pintype "bidirectional"))
      (node (ref "U27") (pin "75") (pinfunction "2-20_75") (pintype "bidirectional"))
    )
    (net (code "126") (name "IOUT+") (class "Default")
      (node (ref "L4") (pin "1") (pinfunction "1_1") (pintype "passive"))
      (node (ref "U12") (pin "3") (pinfunction "COM_3") (pintype "bidirectional"))
      (node (ref "U13") (pin "3") (pinfunction "COM_3") (pintype "bidirectional"))
      (node (ref "U14") (pin "3") (pinfunction "COM_3") (pintype "bidirectional"))
      (node (ref "U15") (pin "3") (pinfunction "COM_3") (pintype "bidirectional"))
      (node (ref "U16") (pin "3") (pinfunction "COM_3") (pintype "bidirectional"))
      (node (ref "U23") (pin "3") (pinfunction "COM_3") (pintype "bidirectional"))
      (node (ref "U24") (pin "3") (pinfunction "COM_3") (pintype "bidirectional"))
    )
    (net (code "127") (name "IOUT-") (class "Default")
      (node (ref "L4") (pin "2") (pinfunction "3_2") (pintype "passive"))
      (node (ref "U17") (pin "3") (pinfunction "COM_3") (pintype "bidirectional"))
      (node (ref "U18") (pin "3") (pinfunction "COM_3") (pintype "bidirectional"))
      (node (ref "U19") (pin "3") (pinfunction "COM_3") (pintype "bidirectional"))
      (node (ref "U20") (pin "3") (pinfunction "COM_3") (pintype "bidirectional"))
      (node (ref "U21") (pin "3") (pinfunction "COM_3") (pintype "bidirectional"))
      (node (ref "U22") (pin "3") (pinfunction "COM_3") (pintype "bidirectional"))
      (node (ref "U25") (pin "3") (pinfunction "COM_3") (pintype "bidirectional"))
    )
    (net (code "128") (name "LED_INT{slash}~{EXT}") (class "Default")
      (node (ref "CN20") (pin "4") (pinfunction "4_4") (pintype "bidirectional"))
      (node (ref "U29") (pin "11") (pinfunction "Y8_11") (pintype "output"))
    )
    (net (code "129") (name "MCLK") (class "Default")
      (node (ref "CN19") (pin "12") (pinfunction "12_12") (pintype "bidirectional"))
      (node (ref "U27") (pin "64") (pinfunction "2-10/CLK3_64") (pintype "bidirectional"))
    )
    (net (code "130") (name "Net-(C2-Pad2)") (class "Default")
      (node (ref "C2") (pin "2") (pinfunction "2_2") (pintype "passive"))
      (node (ref "R5") (pin "2") (pinfunction "2_2") (pintype "passive"))
      (node (ref "R7") (pin "1") (pinfunction "1_1") (pintype "passive"))
    )
    (net (code "131") (name "Net-(CN3-Pad1)") (class "Default")
      (node (ref "CN3") (pin "1") (pinfunction "1_1") (pintype "bidirectional"))
      (node (ref "CN3") (pin "2") (pinfunction "2_2") (pintype "bidirectional"))
      (node (ref "F1") (pin "1") (pinfunction "1_1") (pintype "passive"))
    )
    (net (code "132") (name "Net-(CN4-Pad1)") (class "Default")
      (node (ref "CN4") (pin "1") (pinfunction "1_1") (pintype "bidirectional"))
      (node (ref "CN4") (pin "2") (pinfunction "2_2") (pintype "bidirectional"))
      (node (ref "R58") (pin "2") (pinfunction "2_2") (pintype "passive"))
    )
    (net (code "133") (name "Net-(CN9-Pad1)") (class "Default")
      (node (ref "CN9") (pin "1") (pinfunction "1_1") (pintype "bidirectional"))
      (node (ref "CN9") (pin "2") (pinfunction "2_2") (pintype "bidirectional"))
      (node (ref "F2") (pin "1") (pinfunction "1_1") (pintype "passive"))
    )
    (net (code "134") (name "Net-(CN12-PadP$1)") (class "Default")
      (node (ref "CN12") (pin "P$1") (pinfunction "P$1_P$1") (pintype "bidirectional"))
      (node (ref "CN5") (pin "1") (pinfunction "1_1") (pintype "bidirectional"))
      (node (ref "CN5") (pin "2") (pinfunction "2_2") (pintype "bidirectional"))
    )
    (net (code "135") (name "Net-(CN12-PadP$2)") (class "Default")
      (node (ref "CN12") (pin "P$2") (pinfunction "P$2_P$2") (pintype "bidirectional"))
      (node (ref "CN5") (pin "3") (pinfunction "3_3") (pintype "bidirectional"))
      (node (ref "CN5") (pin "4") (pinfunction "4_4") (pintype "bidirectional"))
    )
    (net (code "136") (name "Net-(CN13-PadP$1)") (class "Default")
      (node (ref "CN13") (pin "P$1") (pinfunction "P$1_P$1") (pintype "bidirectional"))
      (node (ref "CN6") (pin "1") (pinfunction "1_1") (pintype "bidirectional"))
      (node (ref "CN6") (pin "2") (pinfunction "2_2") (pintype "bidirectional"))
    )
    (net (code "137") (name "Net-(CN13-PadP$2)") (class "Default")
      (node (ref "CN13") (pin "P$2") (pinfunction "P$2_P$2") (pintype "bidirectional"))
      (node (ref "CN6") (pin "3") (pinfunction "3_3") (pintype "bidirectional"))
      (node (ref "CN6") (pin "4") (pinfunction "4_4") (pintype "bidirectional"))
    )
    (net (code "138") (name "Net-(CN14-PadP$1)") (class "Default")
      (node (ref "CN14") (pin "P$1") (pinfunction "P$1_P$1") (pintype "bidirectional"))
      (node (ref "CN8") (pin "2") (pinfunction "2_2") (pintype "bidirectional"))
      (node (ref "CN8") (pin "4") (pinfunction "4_4") (pintype "bidirectional"))
    )
    (net (code "139") (name "Net-(CN14-PadP$2)") (class "Default")
      (node (ref "CN14") (pin "P$2") (pinfunction "P$2_P$2") (pintype "bidirectional"))
      (node (ref "CN8") (pin "6") (pinfunction "6_6") (pintype "bidirectional"))
      (node (ref "CN8") (pin "8") (pinfunction "8_8") (pintype "bidirectional"))
    )
    (net (code "140") (name "Net-(CN15-Pad3)") (class "Default")
      (node (ref "CN15") (pin "3") (pinfunction "3_3") (pintype "bidirectional"))
      (node (ref "CN15") (pin "4") (pinfunction "4_4") (pintype "bidirectional"))
      (node (ref "CN9") (pin "3") (pinfunction "3_3") (pintype "bidirectional"))
      (node (ref "CN9") (pin "4") (pinfunction "4_4") (pintype "bidirectional"))
    )
    (net (code "141") (name "Net-(D1-AC)") (class "Default")
      (node (ref "C5") (pin "2") (pinfunction "2_2") (pintype "passive"))
      (node (ref "D1") (pin "3") (pinfunction "AC_3") (pintype "passive"))
      (node (ref "R10") (pin "2") (pinfunction "2_2") (pintype "passive"))
      (node (ref "R15") (pin "1") (pinfunction "1_1") (pintype "passive"))
      (node (ref "U2") (pin "3") (pinfunction "+IN_3") (pintype "input"))
    )
    (net (code "142") (name "Net-(D2-AC)") (class "Default")
      (node (ref "C7") (pin "2") (pinfunction "2_2") (pintype "passive"))
      (node (ref "D2") (pin "3") (pinfunction "AC_3") (pintype "passive"))
      (node (ref "R11") (pin "2") (pinfunction "2_2") (pintype "passive"))
      (node (ref "R16") (pin "1") (pinfunction "1_1") (pintype "passive"))
      (node (ref "U2") (pin "2") (pinfunction "-IN_2") (pintype "input"))
    )
    (net (code "143") (name "Net-(D3-AC)") (class "Default")
      (node (ref "D3") (pin "3") (pinfunction "AC_3") (pintype "passive"))
      (node (ref "R12") (pin "2") (pinfunction "2_2") (pintype "passive"))
      (node (ref "R12") (pin "3") (pinfunction "3_3") (pintype "passive"))
      (node (ref "R17") (pin "1") (pinfunction "1_1") (pintype "passive"))
    )
    (net (code "144") (name "Net-(D4-A1)") (class "Default")
      (node (ref "D4") (pin "A") (pinfunction "A1_A") (pintype "passive"))
      (node (ref "R59") (pin "1") (pinfunction "1_1") (pintype "passive"))
    )
    (net (code "145") (name "Net-(D5-A1)") (class "Default")
      (node (ref "D5") (pin "A") (pinfunction "A1_A") (pintype "passive"))
      (node (ref "R60") (pin "1") (pinfunction "1_1") (pintype "passive"))
    )
    (net (code "146") (name "Net-(D5-K1)") (class "Default")
      (node (ref "CN7") (pin "3") (pinfunction "3_3") (pintype "bidirectional"))
      (node (ref "D5") (pin "C") (pinfunction "K1_C") (pintype "passive"))
    )
    (net (code "147") (name "Net-(D6-A1)") (class "Default")
      (node (ref "D6") (pin "A") (pinfunction "A1_A") (pintype "passive"))
      (node (ref "R61") (pin "1") (pinfunction "1_1") (pintype "passive"))
    )
    (net (code "148") (name "Net-(D6-K1)") (class "Default")
      (node (ref "CN7") (pin "4") (pinfunction "4_4") (pintype "bidirectional"))
      (node (ref "D6") (pin "C") (pinfunction "K1_C") (pintype "passive"))
    )
    (net (code "149") (name "Net-(L1-2)") (class "Default")
      (node (ref "CN1") (pin "1") (pinfunction "1_1") (pintype "bidirectional"))
      (node (ref "CN1") (pin "2") (pinfunction "2_2") (pintype "bidirectional"))
      (node (ref "L1") (pin "4") (pinfunction "2_4") (pintype "passive"))
    )
    (net (code "150") (name "Net-(L1-3)") (class "Default")
      (node (ref "L1") (pin "2") (pinfunction "3_2") (pintype "passive"))
      (node (ref "R9") (pin "1") (pinfunction "1_1") (pintype "passive"))
    )
    (net (code "151") (name "Net-(L1-4)") (class "Default")
      (node (ref "CN1") (pin "3") (pinfunction "3_3") (pintype "bidirectional"))
      (node (ref "CN1") (pin "4") (pinfunction "4_4") (pintype "bidirectional"))
      (node (ref "L1") (pin "3") (pinfunction "4_3") (pintype "passive"))
    )
    (net (code "152") (name "Net-(L1-Pad1)") (class "Default")
      (node (ref "L1") (pin "1") (pinfunction "1_1") (pintype "passive"))
      (node (ref "R8") (pin "1") (pinfunction "1_1") (pintype "passive"))
    )
    (net (code "153") (name "Net-(L2-3)") (class "Default")
      (node (ref "L2") (pin "2") (pinfunction "3_2") (pintype "passive"))
      (node (ref "R11") (pin "1") (pinfunction "1_1") (pintype "passive"))
    )
    (net (code "154") (name "Net-(L2-Pad1)") (class "Default")
      (node (ref "L2") (pin "1") (pinfunction "1_1") (pintype "passive"))
      (node (ref "R10") (pin "1") (pinfunction "1_1") (pintype "passive"))
    )
    (net (code "155") (name "Net-(L4-2)") (class "Default")
      (node (ref "L4") (pin "4") (pinfunction "2_4") (pintype "passive"))
      (node (ref "R51") (pin "2") (pinfunction "2_2") (pintype "passive"))
      (node (ref "R52") (pin "2") (pinfunction "2_2") (pintype "passive"))
      (node (ref "R53") (pin "2") (pinfunction "2_2") (pintype "passive"))
      (node (ref "R54") (pin "2") (pinfunction "2_2") (pintype "passive"))
      (node (ref "TP2") (pin "1") (pinfunction "MP_1") (pintype "passive"))
    )
    (net (code "156") (name "Net-(L4-4)") (class "Default")
      (node (ref "L4") (pin "3") (pinfunction "4_3") (pintype "passive"))
      (node (ref "R56") (pin "2") (pinfunction "2_2") (pintype "passive"))
      (node (ref "TP6") (pin "1") (pinfunction "MP_1") (pintype "passive"))
      (node (ref "U11") (pin "4") (pinfunction "+IN_4") (pintype "input"))
    )
    (net (code "157") (name "Net-(R1-Pad2)") (class "Default")
      (node (ref "R1") (pin "2") (pinfunction "2_2") (pintype "passive"))
      (node (ref "R2") (pin "3") (pinfunction "3_3") (pintype "passive"))
    )
    (net (code "158") (name "Net-(R2-Pad1)") (class "Default")
      (node (ref "R2") (pin "1") (pinfunction "1_1") (pintype "passive"))
      (node (ref "R4") (pin "1") (pinfunction "1_1") (pintype "passive"))
    )
    (net (code "159") (name "Net-(R3-Pad2)") (class "Default")
      (node (ref "R3") (pin "2") (pinfunction "2_2") (pintype "passive"))
      (node (ref "R5") (pin "1") (pinfunction "1_1") (pintype "passive"))
    )
    (net (code "160") (name "Net-(R12-Pad1)") (class "Default")
      (node (ref "R12") (pin "1") (pinfunction "1_1") (pintype "passive"))
      (node (ref "R7") (pin "2") (pinfunction "2_2") (pintype "passive"))
    )
    (net (code "161") (name "Net-(R23-Pad1)") (class "Default")
      (node (ref "R23") (pin "1") (pinfunction "1_1") (pintype "passive"))
      (node (ref "R24") (pin "2") (pinfunction "2_2") (pintype "passive"))
    )
    (net (code "162") (name "Net-(SW1A-C)") (class "Default")
      (node (ref "CN15") (pin "1") (pinfunction "1_1") (pintype "bidirectional"))
      (node (ref "CN15") (pin "2") (pinfunction "2_2") (pintype "bidirectional"))
      (node (ref "SW1") (pin "2") (pinfunction "C_2") (pintype "passive"))
    )
    (net (code "163") (name "Net-(SW1A-NC)") (class "Default")
      (node (ref "F2") (pin "2") (pinfunction "2_2") (pintype "passive"))
      (node (ref "SW1") (pin "3") (pinfunction "NC_3") (pintype "passive"))
    )
    (net (code "164") (name "Net-(TP1-MP)") (class "Default")
      (node (ref "R44") (pin "2") (pinfunction "2_2") (pintype "passive"))
      (node (ref "TP1") (pin "1") (pinfunction "MP_1") (pintype "passive"))
      (node (ref "U8") (pin "1") (pinfunction "OUT_1") (pintype "output"))
      (node (ref "U9") (pin "6") (pinfunction "COM_6") (pintype "bidirectional"))
    )
    (net (code "165") (name "Net-(TP3-MP)") (class "Default")
      (node (ref "C14") (pin "1") (pinfunction "1_1") (pintype "passive"))
      (node (ref "R35") (pin "2") (pinfunction "2_2") (pintype "passive"))
      (node (ref "R37") (pin "1") (pinfunction "1_1") (pintype "passive"))
      (node (ref "R38") (pin "1") (pinfunction "1_1") (pintype "passive"))
      (node (ref "TP3") (pin "1") (pinfunction "MP_1") (pintype "passive"))
    )
    (net (code "166") (name "Net-(TP4-MP)") (class "Default")
      (node (ref "C19") (pin "1") (pinfunction "1_1") (pintype "passive"))
      (node (ref "R45") (pin "2") (pinfunction "2_2") (pintype "passive"))
      (node (ref "TP4") (pin "1") (pinfunction "MP_1") (pintype "passive"))
      (node (ref "U8") (pin "7") (pinfunction "OUT_7") (pintype "output"))
      (node (ref "U9") (pin "10") (pinfunction "COM_10") (pintype "bidirectional"))
    )
    (net (code "167") (name "Net-(TP5-MP)") (class "Default")
      (node (ref "R27") (pin "1") (pinfunction "1_1") (pintype "passive"))
      (node (ref "TP5") (pin "1") (pinfunction "MP_1") (pintype "passive"))
      (node (ref "U3") (pin "10") (pinfunction "COM_10") (pintype "bidirectional"))
      (node (ref "U7") (pin "1") (pinfunction "-IN_1") (pintype "input"))
    )
    (net (code "168") (name "Net-(U1A-+IN)") (class "Default")
      (node (ref "C1") (pin "1") (pinfunction "1_1") (pintype "passive"))
      (node (ref "R3") (pin "1") (pinfunction "1_1") (pintype "passive"))
      (node (ref "U1") (pin "3") (pinfunction "+IN_3") (pintype "input"))
    )
    (net (code "169") (name "Net-(U1A--IN)") (class "Default")
      (node (ref "R2") (pin "2") (pinfunction "2_2") (pintype "passive"))
      (node (ref "U1") (pin "2") (pinfunction "-IN_2") (pintype "input"))
    )
    (net (code "170") (name "Net-(U1A-OUT)") (class "Default")
      (node (ref "C2") (pin "1") (pinfunction "1_1") (pintype "passive"))
      (node (ref "R4") (pin "2") (pinfunction "2_2") (pintype "passive"))
      (node (ref "R6") (pin "1") (pinfunction "1_1") (pintype "passive"))
      (node (ref "U1") (pin "1") (pinfunction "OUT_1") (pintype "output"))
    )
    (net (code "171") (name "Net-(U1B--IN)") (class "Default")
      (node (ref "C6") (pin "2") (pinfunction "2_2") (pintype "passive"))
      (node (ref "R6") (pin "2") (pinfunction "2_2") (pintype "passive"))
      (node (ref "U1") (pin "6") (pinfunction "-IN_6") (pintype "input"))
    )
    (net (code "172") (name "Net-(U1B-OUT)") (class "Default")
      (node (ref "C6") (pin "1") (pinfunction "1_1") (pintype "passive"))
      (node (ref "R17") (pin "2") (pinfunction "2_2") (pintype "passive"))
      (node (ref "R19") (pin "1") (pinfunction "1_1") (pintype "passive"))
      (node (ref "U1") (pin "7") (pinfunction "OUT_7") (pintype "output"))
    )
    (net (code "173") (name "Net-(U2A-OUT)") (class "Default")
      (node (ref "C7") (pin "1") (pinfunction "1_1") (pintype "passive"))
      (node (ref "R16") (pin "2") (pinfunction "2_2") (pintype "passive"))
      (node (ref "R20") (pin "1") (pinfunction "1_1") (pintype "passive"))
      (node (ref "U2") (pin "1") (pinfunction "OUT_1") (pintype "output"))
    )
    (net (code "174") (name "Net-(U2B-+IN)") (class "Default")
      (node (ref "C3") (pin "2") (pinfunction "2_2") (pintype "passive"))
      (node (ref "R13") (pin "1") (pinfunction "1_1") (pintype "passive"))
      (node (ref "R8") (pin "2") (pinfunction "2_2") (pintype "passive"))
      (node (ref "U2") (pin "5") (pinfunction "+IN_5") (pintype "input"))
    )
    (net (code "175") (name "Net-(U2B--IN)") (class "Default")
      (node (ref "C4") (pin "2") (pinfunction "2_2") (pintype "passive"))
      (node (ref "R14") (pin "1") (pinfunction "1_1") (pintype "passive"))
      (node (ref "R9") (pin "2") (pinfunction "2_2") (pintype "passive"))
      (node (ref "U2") (pin "6") (pinfunction "-IN_6") (pintype "input"))
    )
    (net (code "176") (name "Net-(U2B-OUT)") (class "Default")
      (node (ref "C4") (pin "1") (pinfunction "1_1") (pintype "passive"))
      (node (ref "R14") (pin "2") (pinfunction "2_2") (pintype "passive"))
      (node (ref "R18") (pin "1") (pinfunction "1_1") (pintype "passive"))
      (node (ref "U2") (pin "7") (pinfunction "OUT_7") (pintype "output"))
    )
    (net (code "177") (name "Net-(U3A-NC)") (class "Default")
      (node (ref "U3") (pin "6") (pinfunction "COM_6") (pintype "bidirectional"))
      (node (ref "U3") (pin "9") (pinfunction "NC_9") (pintype "bidirectional"))
    )
    (net (code "178") (name "Net-(U3A-NO)") (class "Default")
      (node (ref "R20") (pin "2") (pinfunction "2_2") (pintype "passive"))
      (node (ref "U3") (pin "2") (pinfunction "NO_2") (pintype "bidirectional"))
    )
    (net (code "179") (name "Net-(U3B-NC)") (class "Default")
      (node (ref "R18") (pin "2") (pinfunction "2_2") (pintype "passive"))
      (node (ref "U3") (pin "7") (pinfunction "NC_7") (pintype "bidirectional"))
    )
    (net (code "180") (name "Net-(U3B-NO)") (class "Default")
      (node (ref "R19") (pin "2") (pinfunction "2_2") (pintype "passive"))
      (node (ref "U3") (pin "4") (pinfunction "NO_4") (pintype "bidirectional"))
    )
    (net (code "181") (name "Net-(U4-EN)") (class "Default")
      (node (ref "R26") (pin "2") (pinfunction "2_2") (pintype "passive"))
      (node (ref "U4") (pin "3") (pinfunction "EN_3") (pintype "input"))
    )
    (net (code "182") (name "Net-(U4-NR)") (class "Default")
      (node (ref "C12") (pin "1") (pinfunction "1_1") (pintype "passive"))
      (node (ref "U4") (pin "4") (pinfunction "NR_4") (pintype "passive"))
    )
    (net (code "183") (name "Net-(U5A-+IN)") (class "Default")
      (node (ref "R27") (pin "2") (pinfunction "2_2") (pintype "passive"))
      (node (ref "R29") (pin "2") (pinfunction "2_2") (pintype "passive"))
      (node (ref "U5") (pin "3") (pinfunction "+IN_3") (pintype "input"))
    )
    (net (code "184") (name "Net-(U5A-OUT)") (class "Default")
      (node (ref "C14") (pin "2") (pinfunction "2_2") (pintype "passive"))
      (node (ref "R33") (pin "2") (pinfunction "2_2") (pintype "passive"))
      (node (ref "R35") (pin "1") (pinfunction "1_1") (pintype "passive"))
      (node (ref "U5") (pin "1") (pinfunction "OUT_1") (pintype "output"))
    )
    (net (code "185") (name "Net-(U5B-+IN)") (class "Default")
      (node (ref "C20") (pin "1") (pinfunction "1_1") (pintype "passive"))
      (node (ref "R42") (pin "1") (pinfunction "1_1") (pintype "passive"))
      (node (ref "R43") (pin "2") (pinfunction "2_2") (pintype "passive"))
      (node (ref "U5") (pin "5") (pinfunction "+IN_5") (pintype "input"))
    )
    (net (code "186") (name "Net-(U6-CT)") (class "Default")
      (node (ref "C11") (pin "1") (pinfunction "1_1") (pintype "passive"))
      (node (ref "U6") (pin "4") (pinfunction "CT_4") (pintype "passive"))
    )
    (net (code "187") (name "Net-(U6-SENSE)") (class "Default")
      (node (ref "C10") (pin "1") (pinfunction "1_1") (pintype "passive"))
      (node (ref "R24") (pin "1") (pinfunction "1_1") (pintype "passive"))
      (node (ref "R25") (pin "2") (pinfunction "2_2") (pintype "passive"))
      (node (ref "U6") (pin "5") (pinfunction "SENSE_5") (pintype "bidirectional"))
    )
    (net (code "188") (name "Net-(U7-+IN)") (class "Default")
      (node (ref "R31") (pin "1") (pinfunction "1_1") (pintype "passive"))
      (node (ref "R32") (pin "2") (pinfunction "2_2") (pintype "passive"))
      (node (ref "R34") (pin "1") (pinfunction "1_1") (pintype "passive"))
      (node (ref "U7") (pin "3") (pinfunction "+IN_3") (pintype "input"))
    )
    (net (code "189") (name "Net-(U7-OUT)") (class "Default")
      (node (ref "R34") (pin "2") (pinfunction "2_2") (pintype "passive"))
      (node (ref "R39") (pin "1") (pinfunction "1_1") (pintype "passive"))
      (node (ref "U7") (pin "4") (pinfunction "OUT_4") (pintype "output"))
    )
    (net (code "190") (name "Net-(U8A-+IN)") (class "Default")
      (node (ref "C17") (pin "1") (pinfunction "1_1") (pintype "passive"))
      (node (ref "R37") (pin "2") (pinfunction "2_2") (pintype "passive"))
      (node (ref "R41") (pin "2") (pinfunction "2_2") (pintype "passive"))
      (node (ref "U8") (pin "3") (pinfunction "+IN_3") (pintype "input"))
    )
    (net (code "191") (name "Net-(U8A--IN)") (class "Default")
      (node (ref "R40") (pin "2") (pinfunction "2_2") (pintype "passive"))
      (node (ref "R44") (pin "1") (pinfunction "1_1") (pintype "passive"))
      (node (ref "U8") (pin "2") (pinfunction "-IN_2") (pintype "input"))
    )
    (net (code "192") (name "Net-(U8B--IN)") (class "Default")
      (node (ref "C19") (pin "2") (pinfunction "2_2") (pintype "passive"))
      (node (ref "R38") (pin "2") (pinfunction "2_2") (pintype "passive"))
      (node (ref "R45") (pin "1") (pinfunction "1_1") (pintype "passive"))
      (node (ref "U8") (pin "6") (pinfunction "-IN_6") (pintype "input"))
    )
    (net (code "193") (name "Net-(U9A-NC)") (class "Default")
      (node (ref "R47") (pin "1") (pinfunction "1_1") (pintype "passive"))
      (node (ref "R48") (pin "1") (pinfunction "1_1") (pintype "passive"))
      (node (ref "U9") (pin "9") (pinfunction "NC_9") (pintype "bidirectional"))
    )
    (net (code "194") (name "Net-(U9A-NO)") (class "Default")
      (node (ref "R49") (pin "1") (pinfunction "1_1") (pintype "passive"))
      (node (ref "R50") (pin "1") (pinfunction "1_1") (pintype "passive"))
      (node (ref "U9") (pin "2") (pinfunction "NO_2") (pintype "bidirectional"))
    )
    (net (code "195") (name "Net-(U9B-NC)") (class "Default")
      (node (ref "R51") (pin "1") (pinfunction "1_1") (pintype "passive"))
      (node (ref "R52") (pin "1") (pinfunction "1_1") (pintype "passive"))
      (node (ref "U9") (pin "7") (pinfunction "NC_7") (pintype "bidirectional"))
    )
    (net (code "196") (name "Net-(U9B-NO)") (class "Default")
      (node (ref "R53") (pin "1") (pinfunction "1_1") (pintype "passive"))
      (node (ref "R54") (pin "1") (pinfunction "1_1") (pintype "passive"))
      (node (ref "U9") (pin "4") (pinfunction "NO_4") (pintype "bidirectional"))
    )
    (net (code "197") (name "Net-(U10C-0)") (class "Default")
      (node (ref "R30") (pin "2") (pinfunction "2_2") (pintype "passive"))
      (node (ref "R33") (pin "1") (pinfunction "1_1") (pintype "passive"))
      (node (ref "U10") (pin "12") (pinfunction "0_12") (pintype "bidirectional"))
    )
    (net (code "198") (name "Net-(U10C-1)") (class "Default")
      (node (ref "R28") (pin "2") (pinfunction "2_2") (pintype "passive"))
      (node (ref "R30") (pin "1") (pinfunction "1_1") (pintype "passive"))
      (node (ref "U10") (pin "14") (pinfunction "1_14") (pintype "bidirectional"))
    )
    (net (code "199") (name "Net-(U10C-2)") (class "Default")
      (node (ref "R22") (pin "2") (pinfunction "2_2") (pintype "passive"))
      (node (ref "R28") (pin "1") (pinfunction "1_1") (pintype "passive"))
      (node (ref "U10") (pin "15") (pinfunction "2_15") (pintype "bidirectional"))
    )
    (net (code "200") (name "Net-(U10C-3)") (class "Default")
      (node (ref "R21") (pin "2") (pinfunction "2_2") (pintype "passive"))
      (node (ref "R22") (pin "1") (pinfunction "1_1") (pintype "passive"))
      (node (ref "U10") (pin "11") (pinfunction "3_11") (pintype "bidirectional"))
    )
    (net (code "201") (name "Net-(U10C-COM)") (class "Default")
      (node (ref "U10") (pin "13") (pinfunction "COM_13") (pintype "bidirectional"))
      (node (ref "U5") (pin "2") (pinfunction "-IN_2") (pintype "input"))
    )
    (net (code "202") (name "Net-(U11--IN)") (class "Default")
      (node (ref "R47") (pin "2") (pinfunction "2_2") (pintype "passive"))
      (node (ref "R48") (pin "2") (pinfunction "2_2") (pintype "passive"))
      (node (ref "R49") (pin "2") (pinfunction "2_2") (pintype "passive"))
      (node (ref "R50") (pin "2") (pinfunction "2_2") (pintype "passive"))
      (node (ref "R56") (pin "1") (pinfunction "1_1") (pintype "passive"))
      (node (ref "U11") (pin "1") (pinfunction "-IN_1") (pintype "input"))
    )
    (net (code "203") (name "Net-(U11-REF)") (class "Default")
      (node (ref "R46") (pin "1") (pinfunction "1_1") (pintype "passive"))
      (node (ref "U11") (pin "6") (pinfunction "REF_6") (pintype "passive"))
      (node (ref "U5") (pin "6") (pinfunction "-IN_6") (pintype "input"))
      (node (ref "U5") (pin "7") (pinfunction "OUT_7") (pintype "output"))
    )
    (net (code "204") (name "Net-(U11-RG1)") (class "Default")
      (node (ref "R55") (pin "2") (pinfunction "2_2") (pintype "passive"))
      (node (ref "R57") (pin "2") (pinfunction "2_2") (pintype "passive"))
      (node (ref "U11") (pin "2") (pinfunction "RG1_2") (pintype "passive"))
    )
    (net (code "205") (name "Net-(U11-RG2)") (class "Default")
      (node (ref "R55") (pin "1") (pinfunction "1_1") (pintype "passive"))
      (node (ref "R57") (pin "1") (pinfunction "1_1") (pintype "passive"))
      (node (ref "U11") (pin "3") (pinfunction "RG2_3") (pintype "passive"))
    )
    (net (code "206") (name "Net-(U26-EN)") (class "Default")
      (node (ref "R64") (pin "2") (pinfunction "2_2") (pintype "passive"))
      (node (ref "U26") (pin "3") (pinfunction "EN_3") (pintype "input"))
    )
    (net (code "207") (name "Net-(U26-NR)") (class "Default")
      (node (ref "C52") (pin "1") (pinfunction "1_1") (pintype "passive"))
      (node (ref "U26") (pin "4") (pinfunction "NR_4") (pintype "passive"))
    )
    (net (code "208") (name "Net-(U27A-TCK)") (class "Default")
      (node (ref "CN18") (pin "1") (pinfunction "1_1") (pintype "bidirectional"))
      (node (ref "R65") (pin "2") (pinfunction "2_2") (pintype "passive"))
      (node (ref "U27") (pin "24") (pinfunction "TCK_24") (pintype "bidirectional"))
    )
    (net (code "209") (name "Net-(U27A-TDI)") (class "Default")
      (node (ref "CN18") (pin "9") (pinfunction "9_9") (pintype "bidirectional"))
      (node (ref "R66") (pin "1") (pinfunction "1_1") (pintype "passive"))
      (node (ref "U27") (pin "23") (pinfunction "TDI_23") (pintype "bidirectional"))
    )
    (net (code "210") (name "Net-(U27A-TDO)") (class "Default")
      (node (ref "CN18") (pin "3") (pinfunction "3_3") (pintype "bidirectional"))
      (node (ref "R62") (pin "1") (pinfunction "1_1") (pintype "passive"))
      (node (ref "U27") (pin "25") (pinfunction "TDO_25") (pintype "bidirectional"))
    )
    (net (code "211") (name "Net-(U27A-TMS)") (class "Default")
      (node (ref "CN18") (pin "5") (pinfunction "5_5") (pintype "bidirectional"))
      (node (ref "R63") (pin "1") (pinfunction "1_1") (pintype "passive"))
      (node (ref "U27") (pin "22") (pinfunction "TMS_22") (pintype "bidirectional"))
    )
    (net (code "212") (name "Net-(U27B-1-9{slash}CLK1)") (class "Default")
      (node (ref "R67") (pin "2") (pinfunction "2_2") (pintype "passive"))
      (node (ref "U27") (pin "14") (pinfunction "1-9/CLK1_14") (pintype "bidirectional"))
    )
    (net (code "213") (name "Net-(U27B-1-10)") (class "Default")
      (node (ref "R69") (pin "2") (pinfunction "2_2") (pintype "passive"))
      (node (ref "U27") (pin "15") (pinfunction "1-10_15") (pintype "bidirectional"))
    )
    (net (code "214") (name "Net-(U27B-1-11)") (class "Default")
      (node (ref "R68") (pin "2") (pinfunction "2_2") (pintype "passive"))
      (node (ref "U27") (pin "16") (pinfunction "1-11_16") (pintype "bidirectional"))
    )
    (net (code "215") (name "Net-(U27B-1-17)") (class "Default")
      (node (ref "R70") (pin "2") (pinfunction "2_2") (pintype "passive"))
      (node (ref "U27") (pin "26") (pinfunction "1-17_26") (pintype "bidirectional"))
    )
    (net (code "216") (name "Net-(U27B-1-18)") (class "Default")
      (node (ref "R71") (pin "2") (pinfunction "2_2") (pintype "passive"))
      (node (ref "U27") (pin "27") (pinfunction "1-18_27") (pintype "bidirectional"))
    )
    (net (code "217") (name "Net-(U28-NR)") (class "Default")
      (node (ref "C56") (pin "1") (pinfunction "1_1") (pintype "passive"))
      (node (ref "U28") (pin "4") (pinfunction "NR_4") (pintype "passive"))
    )
    (net (code "218") (name "Net-(U29A-Y1)") (class "Default")
      (node (ref "R83") (pin "1") (pinfunction "1_1") (pintype "passive"))
      (node (ref "U29") (pin "18") (pinfunction "Y1_18") (pintype "output"))
    )
    (net (code "219") (name "Net-(U29A-Y2)") (class "Default")
      (node (ref "R84") (pin "1") (pinfunction "1_1") (pintype "passive"))
      (node (ref "U29") (pin "17") (pinfunction "Y2_17") (pintype "output"))
    )
    (net (code "220") (name "Net-(U29A-~{G})") (class "Default")
      (node (ref "R77") (pin "2") (pinfunction "2_2") (pintype "passive"))
      (node (ref "U29") (pin "19") (pinfunction "~{G}_19") (pintype "input"))
    )
    (net (code "221") (name "Net-(U30-A)") (class "Default")
      (node (ref "R84") (pin "2") (pinfunction "2_2") (pintype "passive"))
      (node (ref "U30") (pin "1") (pinfunction "A_1") (pintype "passive"))
    )
    (net (code "222") (name "PSEL") (class "Default")
      (node (ref "CN19") (pin "13") (pinfunction "13_13") (pintype "bidirectional"))
      (node (ref "U27") (pin "70") (pinfunction "2-15_70") (pintype "bidirectional"))
    )
    (net (code "223") (name "RESET") (class "Default")
      (node (ref "CN19") (pin "9") (pinfunction "9_9") (pintype "bidirectional"))
      (node (ref "U27") (pin "72") (pinfunction "2-17_72") (pintype "bidirectional"))
    )
    (net (code "224") (name "SCLK") (class "Default")
      (node (ref "CN19") (pin "3") (pinfunction "3_3") (pintype "bidirectional"))
      (node (ref "U27") (pin "74") (pinfunction "2-19_74") (pintype "bidirectional"))
    )
    (net (code "225") (name "SDATA") (class "Default")
      (node (ref "CN19") (pin "5") (pinfunction "5_5") (pintype "bidirectional"))
      (node (ref "U27") (pin "73") (pinfunction "2-18_73") (pintype "bidirectional"))
    )
    (net (code "226") (name "SW1") (class "Default")
      (node (ref "C61") (pin "1") (pinfunction "1_1") (pintype "passive"))
      (node (ref "R81") (pin "1") (pinfunction "1_1") (pintype "passive"))
      (node (ref "U27") (pin "52") (pinfunction "2-1_52") (pintype "bidirectional"))
    )
    (net (code "227") (name "SW2") (class "Default")
      (node (ref "C60") (pin "1") (pinfunction "1_1") (pintype "passive"))
      (node (ref "R80") (pin "1") (pinfunction "1_1") (pintype "passive"))
      (node (ref "U27") (pin "53") (pinfunction "2-2_53") (pintype "bidirectional"))
    )
    (net (code "228") (name "SW3") (class "Default")
      (node (ref "C59") (pin "1") (pinfunction "1_1") (pintype "passive"))
      (node (ref "R79") (pin "1") (pinfunction "1_1") (pintype "passive"))
      (node (ref "U27") (pin "54") (pinfunction "2-3_54") (pintype "bidirectional"))
    )
    (net (code "229") (name "SW4") (class "Default")
      (node (ref "C58") (pin "1") (pinfunction "1_1") (pintype "passive"))
      (node (ref "R78") (pin "1") (pinfunction "1_1") (pintype "passive"))
      (node (ref "U27") (pin "55") (pinfunction "2-4_55") (pintype "bidirectional"))
    )
    (net (code "230") (name "SW5") (class "Default")
      (node (ref "C62") (pin "1") (pinfunction "1_1") (pintype "passive"))
      (node (ref "R82") (pin "1") (pinfunction "1_1") (pintype "passive"))
      (node (ref "U27") (pin "51") (pinfunction "1-38_51") (pintype "bidirectional"))
    )
    (net (code "231") (name "SW_DDS{slash}~{ANALOG}") (class "Default")
      (node (ref "CN20") (pin "13") (pinfunction "13_13") (pintype "bidirectional"))
      (node (ref "R76") (pin "1") (pinfunction "1_1") (pintype "passive"))
      (node (ref "R82") (pin "2") (pinfunction "2_2") (pintype "passive"))
    )
    (net (code "232") (name "SW_INT{slash}~{EXT}") (class "Default")
      (node (ref "CN20") (pin "12") (pinfunction "12_12") (pintype "bidirectional"))
      (node (ref "R75") (pin "1") (pinfunction "1_1") (pintype "passive"))
      (node (ref "R81") (pin "2") (pinfunction "2_2") (pintype "passive"))
    )
    (net (code "233") (name "SW_X1{slash}~{X2}") (class "Default")
      (node (ref "CN20") (pin "11") (pinfunction "11_11") (pintype "bidirectional"))
      (node (ref "R74") (pin "1") (pinfunction "1_1") (pintype "passive"))
      (node (ref "R80") (pin "2") (pinfunction "2_2") (pintype "passive"))
    )
    (net (code "234") (name "SW_X1{slash}~{X10}") (class "Default")
      (node (ref "CN20") (pin "10") (pinfunction "10_10") (pintype "bidirectional"))
      (node (ref "R73") (pin "1") (pinfunction "1_1") (pintype "passive"))
      (node (ref "R79") (pin "2") (pinfunction "2_2") (pintype "passive"))
    )
    (net (code "235") (name "SW_~{TEST}") (class "Default")
      (node (ref "CN20") (pin "9") (pinfunction "9_9") (pintype "bidirectional"))
      (node (ref "R72") (pin "1") (pinfunction "1_1") (pintype "passive"))
      (node (ref "R78") (pin "2") (pinfunction "2_2") (pintype "passive"))
    )
    (net (code "236") (name "SYNC_ISO_C") (class "Default")
      (node (ref "CN20") (pin "5") (pinfunction "5_5") (pintype "bidirectional"))
      (node (ref "U30") (pin "4") (pinfunction "COL_4") (pintype "passive"))
    )
    (net (code "237") (name "SYNC_ISO_E") (class "Default")
      (node (ref "CN20") (pin "6") (pinfunction "6_6") (pintype "bidirectional"))
      (node (ref "U30") (pin "3") (pinfunction "EMI_3") (pintype "passive"))
    )
    (net (code "238") (name "SYNC_OSC") (class "Default")
      (node (ref "R39") (pin "2") (pinfunction "2_2") (pintype "passive"))
      (node (ref "TP8") (pin "1") (pinfunction "MP_1") (pintype "passive"))
      (node (ref "U27") (pin "18") (pinfunction "1-13_18") (pintype "bidirectional"))
    )
    (net (code "239") (name "SYNC_OUT") (class "Default")
      (node (ref "CN20") (pin "7") (pinfunction "7_7") (pintype "bidirectional"))
      (node (ref "R83") (pin "2") (pinfunction "2_2") (pintype "passive"))
    )
    (net (code "240") (name "UI_DDS{slash}~{ANALOG}") (class "Default")
      (node (ref "CN11") (pin "2") (pinfunction "2_2") (pintype "bidirectional"))
      (node (ref "CN11") (pin "3") (pinfunction "3_3") (pintype "bidirectional"))
      (node (ref "CN7") (pin "13") (pinfunction "13_13") (pintype "bidirectional"))
    )
    (net (code "241") (name "UI_INT{slash}~{EXT}") (class "Default")
      (node (ref "CN7") (pin "12") (pinfunction "12_12") (pintype "bidirectional"))
      (node (ref "SW4") (pin "2") (pinfunction "C_2") (pintype "passive"))
    )
    (net (code "242") (name "UI_SYNC_C") (class "Default")
      (node (ref "CN7") (pin "5") (pinfunction "5_5") (pintype "bidirectional"))
      (node (ref "CN8") (pin "1") (pinfunction "1_1") (pintype "bidirectional"))
    )
    (net (code "243") (name "UI_SYNC_E") (class "Default")
      (node (ref "CN7") (pin "6") (pinfunction "6_6") (pintype "bidirectional"))
      (node (ref "CN8") (pin "5") (pinfunction "5_5") (pintype "bidirectional"))
    )
    (net (code "244") (name "UI_SYNC_N") (class "Default")
      (node (ref "CN7") (pin "8") (pinfunction "8_8") (pintype "bidirectional"))
      (node (ref "CN8") (pin "7") (pinfunction "7_7") (pintype "bidirectional"))
    )
    (net (code "245") (name "UI_SYNC_P") (class "Default")
      (node (ref "CN7") (pin "7") (pinfunction "7_7") (pintype "bidirectional"))
      (node (ref "CN8") (pin "3") (pinfunction "3_3") (pintype "bidirectional"))
    )
    (net (code "246") (name "UI_VD+3V3") (class "Default")
      (node (ref "CN7") (pin "1") (pinfunction "1_1") (pintype "bidirectional"))
      (node (ref "R59") (pin "2") (pinfunction "2_2") (pintype "passive"))
      (node (ref "R60") (pin "2") (pinfunction "2_2") (pintype "passive"))
      (node (ref "R61") (pin "2") (pinfunction "2_2") (pintype "passive"))
    )
    (net (code "247") (name "UI_X1{slash}~{X2}") (class "Default")
      (node (ref "CN7") (pin "11") (pinfunction "11_11") (pintype "bidirectional"))
      (node (ref "SW3") (pin "2") (pinfunction "C_2") (pintype "passive"))
    )
    (net (code "248") (name "UI_X1{slash}~{X10}") (class "Default")
      (node (ref "CN7") (pin "10") (pinfunction "10_10") (pintype "bidirectional"))
      (node (ref "SW2") (pin "2") (pinfunction "C_2") (pintype "passive"))
    )
    (net (code "249") (name "UI_~{TEST}") (class "Default")
      (node (ref "CN10") (pin "2") (pinfunction "2_2") (pintype "bidirectional"))
      (node (ref "CN10") (pin "3") (pinfunction "3_3") (pintype "bidirectional"))
      (node (ref "CN7") (pin "9") (pinfunction "9_9") (pintype "bidirectional"))
    )
    (net (code "250") (name "VA+3V3") (class "Default")
      (node (ref "C13") (pin "1") (pinfunction "1_1") (pintype "passive"))
      (node (ref "C15") (pin "2") (pinfunction "2_2") (pintype "passive"))
      (node (ref "C16") (pin "1") (pinfunction "1_1") (pintype "passive"))
      (node (ref "C18") (pin "1") (pinfunction "1_1") (pintype "passive"))
      (node (ref "C21") (pin "1") (pinfunction "1_1") (pintype "passive"))
      (node (ref "C22") (pin "1") (pinfunction "1_1") (pintype "passive"))
      (node (ref "C24") (pin "1") (pinfunction "1_1") (pintype "passive"))
      (node (ref "C25") (pin "1") (pinfunction "1_1") (pintype "passive"))
      (node (ref "C27") (pin "1") (pinfunction "1_1") (pintype "passive"))
      (node (ref "C28") (pin "1") (pinfunction "1_1") (pintype "passive"))
      (node (ref "C29") (pin "1") (pinfunction "1_1") (pintype "passive"))
      (node (ref "C30") (pin "1") (pinfunction "1_1") (pintype "passive"))
      (node (ref "C31") (pin "1") (pinfunction "1_1") (pintype "passive"))
      (node (ref "C32") (pin "1") (pinfunction "1_1") (pintype "passive"))
      (node (ref "C33") (pin "1") (pinfunction "1_1") (pintype "passive"))
      (node (ref "C34") (pin "1") (pinfunction "1_1") (pintype "passive"))
      (node (ref "C35") (pin "1") (pinfunction "1_1") (pintype "passive"))
      (node (ref "C36") (pin "1") (pinfunction "1_1") (pintype "passive"))
      (node (ref "C37") (pin "1") (pinfunction "1_1") (pintype "passive"))
      (node (ref "C38") (pin "1") (pinfunction "1_1") (pintype "passive"))
      (node (ref "C39") (pin "1") (pinfunction "1_1") (pintype "passive"))
      (node (ref "C40") (pin "1") (pinfunction "1_1") (pintype "passive"))
      (node (ref "C41") (pin "1") (pinfunction "1_1") (pintype "passive"))
      (node (ref "D1") (pin "2") (pinfunction "C_2") (pintype "passive"))
      (node (ref "D2") (pin "2") (pinfunction "C_2") (pintype "passive"))
      (node (ref "R31") (pin "2") (pinfunction "2_2") (pintype "passive"))
      (node (ref "R42") (pin "2") (pinfunction "2_2") (pintype "passive"))
      (node (ref "U1") (pin "8") (pinfunction "V+_8") (pintype "power_in"))
      (node (ref "U10") (pin "16") (pinfunction "VCC_16") (pintype "power_in"))
      (node (ref "U12") (pin "16") (pinfunction "V+_16") (pintype "power_in"))
      (node (ref "U13") (pin "16") (pinfunction "V+_16") (pintype "power_in"))
      (node (ref "U14") (pin "16") (pinfunction "V+_16") (pintype "power_in"))
      (node (ref "U15") (pin "16") (pinfunction "V+_16") (pintype "power_in"))
      (node (ref "U16") (pin "16") (pinfunction "V+_16") (pintype "power_in"))
      (node (ref "U17") (pin "16") (pinfunction "V+_16") (pintype "power_in"))
      (node (ref "U18") (pin "16") (pinfunction "V+_16") (pintype "power_in"))
      (node (ref "U19") (pin "16") (pinfunction "V+_16") (pintype "power_in"))
      (node (ref "U2") (pin "8") (pinfunction "V+_8") (pintype "power_in"))
      (node (ref "U20") (pin "16") (pinfunction "V+_16") (pintype "power_in"))
      (node (ref "U21") (pin "16") (pinfunction "V+_16") (pintype "power_in"))
      (node (ref "U22") (pin "16") (pinfunction "V+_16") (pintype "power_in"))
      (node (ref "U23") (pin "16") (pinfunction "V+_16") (pintype "power_in"))
      (node (ref "U24") (pin "16") (pinfunction "V+_16") (pintype "power_in"))
      (node (ref "U25") (pin "16") (pinfunction "V+_16") (pintype "power_in"))
      (node (ref "U3") (pin "8") (pinfunction "V+_8") (pintype "power_in"))
      (node (ref "U4") (pin "5") (pinfunction "VO_5") (pintype "passive"))
      (node (ref "U5") (pin "8") (pinfunction "V+_8") (pintype "power_in"))
      (node (ref "U7") (pin "5") (pinfunction "V+_5") (pintype "power_in"))
      (node (ref "U8") (pin "8") (pinfunction "V+_8") (pintype "power_in"))
      (node (ref "U9") (pin "8") (pinfunction "V+_8") (pintype "power_in"))
    )
    (net (code "251") (name "VA+5") (class "Default")
      (node (ref "C26") (pin "2") (pinfunction "2_2") (pintype "passive"))
      (node (ref "C8") (pin "POS") (pinfunction "POS_POS") (pintype "passive"))
      (node (ref "C9") (pin "1") (pinfunction "1_1") (pintype "passive"))
      (node (ref "L3") (pin "1") (pinfunction "1_1") (pintype "passive"))
      (node (ref "R26") (pin "1") (pinfunction "1_1") (pintype "passive"))
      (node (ref "U11") (pin "8") (pinfunction "V+_8") (pintype "power_in"))
      (node (ref "U4") (pin "1") (pinfunction "VI_1") (pintype "input"))
    )
    (net (code "252") (name "VD+1V8") (class "Default")
      (node (ref "C49") (pin "2") (pinfunction "2_2") (pintype "passive"))
      (node (ref "C51") (pin "2") (pinfunction "2_2") (pintype "passive"))
      (node (ref "C57") (pin "1") (pinfunction "1_1") (pintype "passive"))
      (node (ref "U27") (pin "13") (pinfunction "VCCINT_1_13") (pintype "power_in"))
      (node (ref "U27") (pin "63") (pinfunction "VCCINT_2_63") (pintype "power_in"))
      (node (ref "U28") (pin "5") (pinfunction "VO_5") (pintype "passive"))
    )
    (net (code "253") (name "VD+3V3") (class "Default")
      (node (ref "C42") (pin "1") (pinfunction "1_1") (pintype "passive"))
      (node (ref "C43") (pin "1") (pinfunction "1_1") (pintype "passive"))
      (node (ref "C44") (pin "1") (pinfunction "1_1") (pintype "passive"))
      (node (ref "C45") (pin "1") (pinfunction "1_1") (pintype "passive"))
      (node (ref "C48") (pin "2") (pinfunction "2_2") (pintype "passive"))
      (node (ref "C50") (pin "2") (pinfunction "2_2") (pintype "passive"))
      (node (ref "C53") (pin "1") (pinfunction "1_1") (pintype "passive"))
      (node (ref "C54") (pin "1") (pinfunction "1_1") (pintype "passive"))
      (node (ref "C55") (pin "1") (pinfunction "1_1") (pintype "passive"))
      (node (ref "CN18") (pin "4") (pinfunction "4_4") (pintype "bidirectional"))
      (node (ref "CN19") (pin "6") (pinfunction "6_6") (pintype "bidirectional"))
      (node (ref "CN19") (pin "8") (pinfunction "8_8") (pintype "bidirectional"))
      (node (ref "CN20") (pin "1") (pinfunction "1_1") (pintype "bidirectional"))
      (node (ref "R36") (pin "2") (pinfunction "2_2") (pintype "passive"))
      (node (ref "R62") (pin "2") (pinfunction "2_2") (pintype "passive"))
      (node (ref "R63") (pin "2") (pinfunction "2_2") (pintype "passive"))
      (node (ref "R66") (pin "2") (pinfunction "2_2") (pintype "passive"))
      (node (ref "R72") (pin "2") (pinfunction "2_2") (pintype "passive"))
      (node (ref "R73") (pin "2") (pinfunction "2_2") (pintype "passive"))
      (node (ref "R74") (pin "2") (pinfunction "2_2") (pintype "passive"))
      (node (ref "R75") (pin "2") (pinfunction "2_2") (pintype "passive"))
      (node (ref "R76") (pin "2") (pinfunction "2_2") (pintype "passive"))
      (node (ref "U26") (pin "5") (pinfunction "VO_5") (pintype "passive"))
      (node (ref "U27") (pin "31") (pinfunction "VCCIO1_2_31") (pintype "power_in"))
      (node (ref "U27") (pin "45") (pinfunction "VCCIO1_3_45") (pintype "power_in"))
      (node (ref "U27") (pin "59") (pinfunction "VCCIO2_1_59") (pintype "power_in"))
      (node (ref "U27") (pin "80") (pinfunction "VCCIO2_2_80") (pintype "power_in"))
      (node (ref "U27") (pin "9") (pinfunction "VCCIO1_1_9") (pintype "power_in"))
      (node (ref "U27") (pin "94") (pinfunction "VCCIO2_3_94") (pintype "power_in"))
      (node (ref "U28") (pin "1") (pinfunction "VI_1") (pintype "input"))
      (node (ref "U28") (pin "3") (pinfunction "EN_3") (pintype "input"))
      (node (ref "U29") (pin "1") (pinfunction "CONT_1") (pintype "input"))
      (node (ref "U29") (pin "20") (pinfunction "VCC_20") (pintype "power_in"))
    )
    (net (code "254") (name "VD_BAT") (class "Default")
      (node (ref "C46") (pin "POS") (pinfunction "POS_POS") (pintype "passive"))
      (node (ref "C47") (pin "1") (pinfunction "1_1") (pintype "passive"))
      (node (ref "L5") (pin "4") (pinfunction "2_4") (pintype "passive"))
      (node (ref "R23") (pin "2") (pinfunction "2_2") (pintype "passive"))
      (node (ref "R64") (pin "1") (pinfunction "1_1") (pintype "passive"))
      (node (ref "U26") (pin "1") (pinfunction "VI_1") (pintype "input"))
      (node (ref "U6") (pin "6") (pinfunction "VDD_6") (pintype "power_in"))
    )
    (net (code "255") (name "ZOUT") (class "Default")
      (node (ref "U27") (pin "21") (pinfunction "1-16_21") (pintype "bidirectional"))
      (node (ref "U9") (pin "1") (pinfunction "IN_1") (pintype "input"))
      (node (ref "U9") (pin "5") (pinfunction "IN_5") (pintype "input"))
    )
    (net (code "256") (name "unconnected-(CN7-Pad14)") (class "Default")
      (node (ref "CN7") (pin "14") (pinfunction "14_14") (pintype "bidirectional"))
    )
    (net (code "257") (name "unconnected-(CN10-Pad1)") (class "Default")
      (node (ref "CN10") (pin "1") (pinfunction "1_1") (pintype "bidirectional"))
    )
    (net (code "258") (name "unconnected-(CN11-Pad1)") (class "Default")
      (node (ref "CN11") (pin "1") (pinfunction "1_1") (pintype "bidirectional"))
    )
    (net (code "259") (name "unconnected-(CN18-Pad6)") (class "Default")
      (node (ref "CN18") (pin "6") (pinfunction "6_6") (pintype "bidirectional"))
    )
    (net (code "260") (name "unconnected-(CN18-Pad7)") (class "Default")
      (node (ref "CN18") (pin "7") (pinfunction "7_7") (pintype "bidirectional"))
    )
    (net (code "261") (name "unconnected-(CN18-Pad8)") (class "Default")
      (node (ref "CN18") (pin "8") (pinfunction "8_8") (pintype "bidirectional"))
    )
    (net (code "262") (name "unconnected-(CN19-Pad7)") (class "Default")
      (node (ref "CN19") (pin "7") (pinfunction "7_7") (pintype "bidirectional"))
    )
    (net (code "263") (name "unconnected-(CN19-Pad14)") (class "Default")
      (node (ref "CN19") (pin "14") (pinfunction "14_14") (pintype "bidirectional"))
    )
    (net (code "264") (name "unconnected-(CN20-Pad14)") (class "Default")
      (node (ref "CN20") (pin "14") (pinfunction "14_14") (pintype "bidirectional"))
    )
    (net (code "265") (name "unconnected-(SW1A-NO-Pad1)") (class "Default")
      (node (ref "SW1") (pin "1") (pinfunction "NO_1") (pintype "passive"))
    )
    (net (code "266") (name "unconnected-(SW2A-NO-Pad1)") (class "Default")
      (node (ref "SW2") (pin "1") (pinfunction "NO_1") (pintype "passive"))
    )
    (net (code "267") (name "unconnected-(SW3A-NO-Pad1)") (class "Default")
      (node (ref "SW3") (pin "1") (pinfunction "NO_1") (pintype "passive"))
    )
    (net (code "268") (name "unconnected-(SW4A-NO-Pad1)") (class "Default")
      (node (ref "SW4") (pin "1") (pinfunction "NO_1") (pintype "passive"))
    )
    (net (code "269") (name "unconnected-(U6-~{MR}-Pad3)") (class "Default")
      (node (ref "U6") (pin "3") (pinfunction "~{MR}_3") (pintype "bidirectional"))
    )
    (net (code "270") (name "unconnected-(U10-Pad2)") (class "Default")
      (node (ref "U10") (pin "2") (pinfunction "2_2") (pintype "bidirectional"))
    )
    (net (code "271") (name "unconnected-(U10D-0-Pad1)") (class "Default")
      (node (ref "U10") (pin "1") (pinfunction "0_1") (pintype "bidirectional"))
    )
    (net (code "272") (name "unconnected-(U10D-1-Pad5)") (class "Default")
      (node (ref "U10") (pin "5") (pinfunction "1_5") (pintype "bidirectional"))
    )
    (net (code "273") (name "unconnected-(U10D-3-Pad4)") (class "Default")
      (node (ref "U10") (pin "4") (pinfunction "3_4") (pintype "bidirectional"))
    )
    (net (code "274") (name "unconnected-(U10D-COM-Pad3)") (class "Default")
      (node (ref "U10") (pin "3") (pinfunction "COM_3") (pintype "bidirectional"))
    )
    (net (code "275") (name "unconnected-(U23-Pad5)") (class "Default")
      (node (ref "U23") (pin "5") (pinfunction "5_5") (pintype "bidirectional"))
    )
    (net (code "276") (name "unconnected-(U23B-2-Pad15)") (class "Default")
      (node (ref "U23") (pin "15") (pinfunction "2_15") (pintype "bidirectional"))
    )
    (net (code "277") (name "unconnected-(U23B-3-Pad12)") (class "Default")
      (node (ref "U23") (pin "12") (pinfunction "3_12") (pintype "bidirectional"))
    )
    (net (code "278") (name "unconnected-(U23B-4-Pad1)") (class "Default")
      (node (ref "U23") (pin "1") (pinfunction "4_1") (pintype "bidirectional"))
    )
    (net (code "279") (name "unconnected-(U23B-6-Pad2)") (class "Default")
      (node (ref "U23") (pin "2") (pinfunction "6_2") (pintype "bidirectional"))
    )
    (net (code "280") (name "unconnected-(U23B-7-Pad4)") (class "Default")
      (node (ref "U23") (pin "4") (pinfunction "7_4") (pintype "bidirectional"))
    )
    (net (code "281") (name "unconnected-(U25-Pad5)") (class "Default")
      (node (ref "U25") (pin "5") (pinfunction "5_5") (pintype "bidirectional"))
    )
    (net (code "282") (name "unconnected-(U25B-2-Pad15)") (class "Default")
      (node (ref "U25") (pin "15") (pinfunction "2_15") (pintype "bidirectional"))
    )
    (net (code "283") (name "unconnected-(U25B-3-Pad12)") (class "Default")
      (node (ref "U25") (pin "12") (pinfunction "3_12") (pintype "bidirectional"))
    )
    (net (code "284") (name "unconnected-(U25B-4-Pad1)") (class "Default")
      (node (ref "U25") (pin "1") (pinfunction "4_1") (pintype "bidirectional"))
    )
    (net (code "285") (name "unconnected-(U25B-6-Pad2)") (class "Default")
      (node (ref "U25") (pin "2") (pinfunction "6_2") (pintype "bidirectional"))
    )
    (net (code "286") (name "unconnected-(U25B-7-Pad4)") (class "Default")
      (node (ref "U25") (pin "4") (pinfunction "7_4") (pintype "bidirectional"))
    )
    (net (code "287") (name "unconnected-(U27B-1-19-Pad28)") (class "Default")
      (node (ref "U27") (pin "28") (pinfunction "1-19_28") (pintype "bidirectional"))
    )
    (net (code "288") (name "unconnected-(U27B-1-20-Pad29)") (class "Default")
      (node (ref "U27") (pin "29") (pinfunction "1-20_29") (pintype "bidirectional"))
    )
    (net (code "289") (name "unconnected-(U27B-1-21-Pad30)") (class "Default")
      (node (ref "U27") (pin "30") (pinfunction "1-21_30") (pintype "bidirectional"))
    )
    (net (code "290") (name "unconnected-(U27B-1-22-Pad33)") (class "Default")
      (node (ref "U27") (pin "33") (pinfunction "1-22_33") (pintype "bidirectional"))
    )
    (net (code "291") (name "unconnected-(U27B-1-23-Pad34)") (class "Default")
      (node (ref "U27") (pin "34") (pinfunction "1-23_34") (pintype "bidirectional"))
    )
    (net (code "292") (name "unconnected-(U27B-1-24-Pad35)") (class "Default")
      (node (ref "U27") (pin "35") (pinfunction "1-24_35") (pintype "bidirectional"))
    )
    (net (code "293") (name "unconnected-(U27B-1-25-Pad36)") (class "Default")
      (node (ref "U27") (pin "36") (pinfunction "1-25_36") (pintype "bidirectional"))
    )
    (net (code "294") (name "unconnected-(U27B-1-26-Pad37)") (class "Default")
      (node (ref "U27") (pin "37") (pinfunction "1-26_37") (pintype "bidirectional"))
    )
    (net (code "295") (name "unconnected-(U27B-1-27-Pad38)") (class "Default")
      (node (ref "U27") (pin "38") (pinfunction "1-27_38") (pintype "bidirectional"))
    )
    (net (code "296") (name "unconnected-(U27B-1-28-Pad39)") (class "Default")
      (node (ref "U27") (pin "39") (pinfunction "1-28_39") (pintype "bidirectional"))
    )
    (net (code "297") (name "unconnected-(U27B-1-29-Pad40)") (class "Default")
      (node (ref "U27") (pin "40") (pinfunction "1-29_40") (pintype "bidirectional"))
    )
    (net (code "298") (name "unconnected-(U27B-1-30-Pad41)") (class "Default")
      (node (ref "U27") (pin "41") (pinfunction "1-30_41") (pintype "bidirectional"))
    )
    (net (code "299") (name "unconnected-(U27B-1-31-Pad42)") (class "Default")
      (node (ref "U27") (pin "42") (pinfunction "1-31_42") (pintype "bidirectional"))
    )
    (net (code "300") (name "unconnected-(U27B-1-34-Pad47)") (class "Default")
      (node (ref "U27") (pin "47") (pinfunction "1-34_47") (pintype "bidirectional"))
    )
    (net (code "301") (name "unconnected-(U27B-1-35-Pad48)") (class "Default")
      (node (ref "U27") (pin "48") (pinfunction "1-35_48") (pintype "bidirectional"))
    )
    (net (code "302") (name "unconnected-(U27B-1-36-Pad49)") (class "Default")
      (node (ref "U27") (pin "49") (pinfunction "1-36_49") (pintype "bidirectional"))
    )
    (net (code "303") (name "unconnected-(U27B-1-37-Pad50)") (class "Default")
      (node (ref "U27") (pin "50") (pinfunction "1-37_50") (pintype "bidirectional"))
    )
    (net (code "304") (name "unconnected-(U27B-2-9{slash}CLK2-Pad62)") (class "Default")
      (node (ref "U27") (pin "62") (pinfunction "2-9/CLK2_62") (pintype "bidirectional"))
    )
    (net (code "305") (name "unconnected-(U27B-2-12-Pad67)") (class "Default")
      (node (ref "U27") (pin "67") (pinfunction "2-12_67") (pintype "bidirectional"))
    )
    (net (code "306") (name "unconnected-(U27B-2-13-Pad68)") (class "Default")
      (node (ref "U27") (pin "68") (pinfunction "2-13_68") (pintype "bidirectional"))
    )
    (net (code "307") (name "unconnected-(U27B-2-14-Pad69)") (class "Default")
      (node (ref "U27") (pin "69") (pinfunction "2-14_69") (pintype "bidirectional"))
    )
    (net (code "308") (name "unconnected-(U27B-2-21-Pad76)") (class "Default")
      (node (ref "U27") (pin "76") (pinfunction "2-21_76") (pintype "bidirectional"))
    )
    (net (code "309") (name "unconnected-(U27B-2-22-Pad77)") (class "Default")
      (node (ref "U27") (pin "77") (pinfunction "2-22_77") (pintype "bidirectional"))
    )
    (net (code "310") (name "unconnected-(U27B-2-23-Pad78)") (class "Default")
      (node (ref "U27") (pin "78") (pinfunction "2-23_78") (pintype "bidirectional"))
    )
    (net (code "311") (name "unconnected-(U27B-2-24-Pad81)") (class "Default")
      (node (ref "U27") (pin "81") (pinfunction "2-24_81") (pintype "bidirectional"))
    )
    (net (code "312") (name "unconnected-(U27B-2-25-Pad82)") (class "Default")
      (node (ref "U27") (pin "82") (pinfunction "2-25_82") (pintype "bidirectional"))
    )
    (net (code "313") (name "unconnected-(U27B-2-26-Pad83)") (class "Default")
      (node (ref "U27") (pin "83") (pinfunction "2-26_83") (pintype "bidirectional"))
    )
    (net (code "314") (name "unconnected-(U27B-2-27-Pad84)") (class "Default")
      (node (ref "U27") (pin "84") (pinfunction "2-27_84") (pintype "bidirectional"))
    )
    (net (code "315") (name "unconnected-(U27B-2-28-Pad85)") (class "Default")
      (node (ref "U27") (pin "85") (pinfunction "2-28_85") (pintype "bidirectional"))
    )
    (net (code "316") (name "unconnected-(U27B-2-29-Pad86)") (class "Default")
      (node (ref "U27") (pin "86") (pinfunction "2-29_86") (pintype "bidirectional"))
    )
    (net (code "317") (name "unconnected-(U27B-2-30-Pad87)") (class "Default")
      (node (ref "U27") (pin "87") (pinfunction "2-30_87") (pintype "bidirectional"))
    )
    (net (code "318") (name "unconnected-(U27B-2-31-Pad88)") (class "Default")
      (node (ref "U27") (pin "88") (pinfunction "2-31_88") (pintype "bidirectional"))
    )
    (net (code "319") (name "unconnected-(U27B-2-32-Pad89)") (class "Default")
      (node (ref "U27") (pin "89") (pinfunction "2-32_89") (pintype "bidirectional"))
    )
    (net (code "320") (name "unconnected-(U27B-2-33-Pad90)") (class "Default")
      (node (ref "U27") (pin "90") (pinfunction "2-33_90") (pintype "bidirectional"))
    )
    (net (code "321") (name "unconnected-(U27B-2-34-Pad91)") (class "Default")
      (node (ref "U27") (pin "91") (pinfunction "2-34_91") (pintype "bidirectional"))
    )
    (net (code "322") (name "unconnected-(U27B-2-35-Pad92)") (class "Default")
      (node (ref "U27") (pin "92") (pinfunction "2-35_92") (pintype "bidirectional"))
    )
    (net (code "323") (name "unconnected-(U27B-2-36-Pad95)") (class "Default")
      (node (ref "U27") (pin "95") (pinfunction "2-36_95") (pintype "bidirectional"))
    )
    (net (code "324") (name "unconnected-(U27B-2-37-Pad96)") (class "Default")
      (node (ref "U27") (pin "96") (pinfunction "2-37_96") (pintype "bidirectional"))
    )
    (net (code "325") (name "unconnected-(U27B-2-38-Pad97)") (class "Default")
      (node (ref "U27") (pin "97") (pinfunction "2-38_97") (pintype "bidirectional"))
    )
    (net (code "326") (name "unconnected-(U27B-2-39-Pad98)") (class "Default")
      (node (ref "U27") (pin "98") (pinfunction "2-39_98") (pintype "bidirectional"))
    )
    (net (code "327") (name "unconnected-(U27B-2-40-Pad99)") (class "Default")
      (node (ref "U27") (pin "99") (pinfunction "2-40_99") (pintype "bidirectional"))
    )
    (net (code "328") (name "unconnected-(U27B-2-41-Pad100)") (class "Default")
      (node (ref "U27") (pin "100") (pinfunction "2-41_100") (pintype "bidirectional"))
    )
    (net (code "329") (name "unconnected-(U29A-Y3-Pad16)") (class "Default")
      (node (ref "U29") (pin "16") (pinfunction "Y3_16") (pintype "output"))
    )
    (net (code "330") (name "unconnected-(U29A-Y4-Pad15)") (class "Default")
      (node (ref "U29") (pin "15") (pinfunction "Y4_15") (pintype "output"))
    )
    (net (code "331") (name "~{CS0}") (class "Default")
      (node (ref "U12") (pin "6") (pinfunction "EN_6") (pintype "input"))
      (node (ref "U18") (pin "6") (pinfunction "EN_6") (pintype "input"))
      (node (ref "U27") (pin "2") (pinfunction "1-1_2") (pintype "bidirectional"))
    )
    (net (code "332") (name "~{CS1}") (class "Default")
      (node (ref "U14") (pin "6") (pinfunction "EN_6") (pintype "input"))
      (node (ref "U20") (pin "6") (pinfunction "EN_6") (pintype "input"))
      (node (ref "U27") (pin "3") (pinfunction "1-2_3") (pintype "bidirectional"))
    )
    (net (code "333") (name "~{CS2}") (class "Default")
      (node (ref "U16") (pin "6") (pinfunction "EN_6") (pintype "input"))
      (node (ref "U22") (pin "6") (pinfunction "EN_6") (pintype "input"))
      (node (ref "U27") (pin "4") (pinfunction "1-3_4") (pintype "bidirectional"))
    )
    (net (code "334") (name "~{CS3}") (class "Default")
      (node (ref "U17") (pin "6") (pinfunction "EN_6") (pintype "input"))
      (node (ref "U24") (pin "6") (pinfunction "EN_6") (pintype "input"))
      (node (ref "U27") (pin "5") (pinfunction "1-4_5") (pintype "bidirectional"))
    )
    (net (code "335") (name "~{CS4}") (class "Default")
      (node (ref "U13") (pin "6") (pinfunction "EN_6") (pintype "input"))
      (node (ref "U19") (pin "6") (pinfunction "EN_6") (pintype "input"))
      (node (ref "U27") (pin "6") (pinfunction "1-5_6") (pintype "bidirectional"))
    )
    (net (code "336") (name "~{CS5}") (class "Default")
      (node (ref "U15") (pin "6") (pinfunction "EN_6") (pintype "input"))
      (node (ref "U21") (pin "6") (pinfunction "EN_6") (pintype "input"))
      (node (ref "U27") (pin "7") (pinfunction "1-6_7") (pintype "bidirectional"))
    )
    (net (code "337") (name "~{CS6}") (class "Default")
      (node (ref "U23") (pin "6") (pinfunction "EN_6") (pintype "input"))
      (node (ref "U25") (pin "6") (pinfunction "EN_6") (pintype "input"))
      (node (ref "U27") (pin "8") (pinfunction "1-7_8") (pintype "bidirectional"))
    )
    (net (code "338") (name "~{LOW_BAT}") (class "Default")
      (node (ref "CN20") (pin "3") (pinfunction "3_3") (pintype "bidirectional"))
      (node (ref "R36") (pin "1") (pinfunction "1_1") (pintype "passive"))
      (node (ref "U27") (pin "12") (pinfunction "1-8/CLK0_12") (pintype "bidirectional"))
      (node (ref "U6") (pin "1") (pinfunction "~{RESET}_1") (pintype "output"))
    )
    (net (code "339") (name "~{OE}") (class "Default")
      (node (ref "U27") (pin "17") (pinfunction "1-12_17") (pintype "bidirectional"))
    )
  )
)
